# M8416C.net
KiCad netlist of a schematic drawn in EAGLE
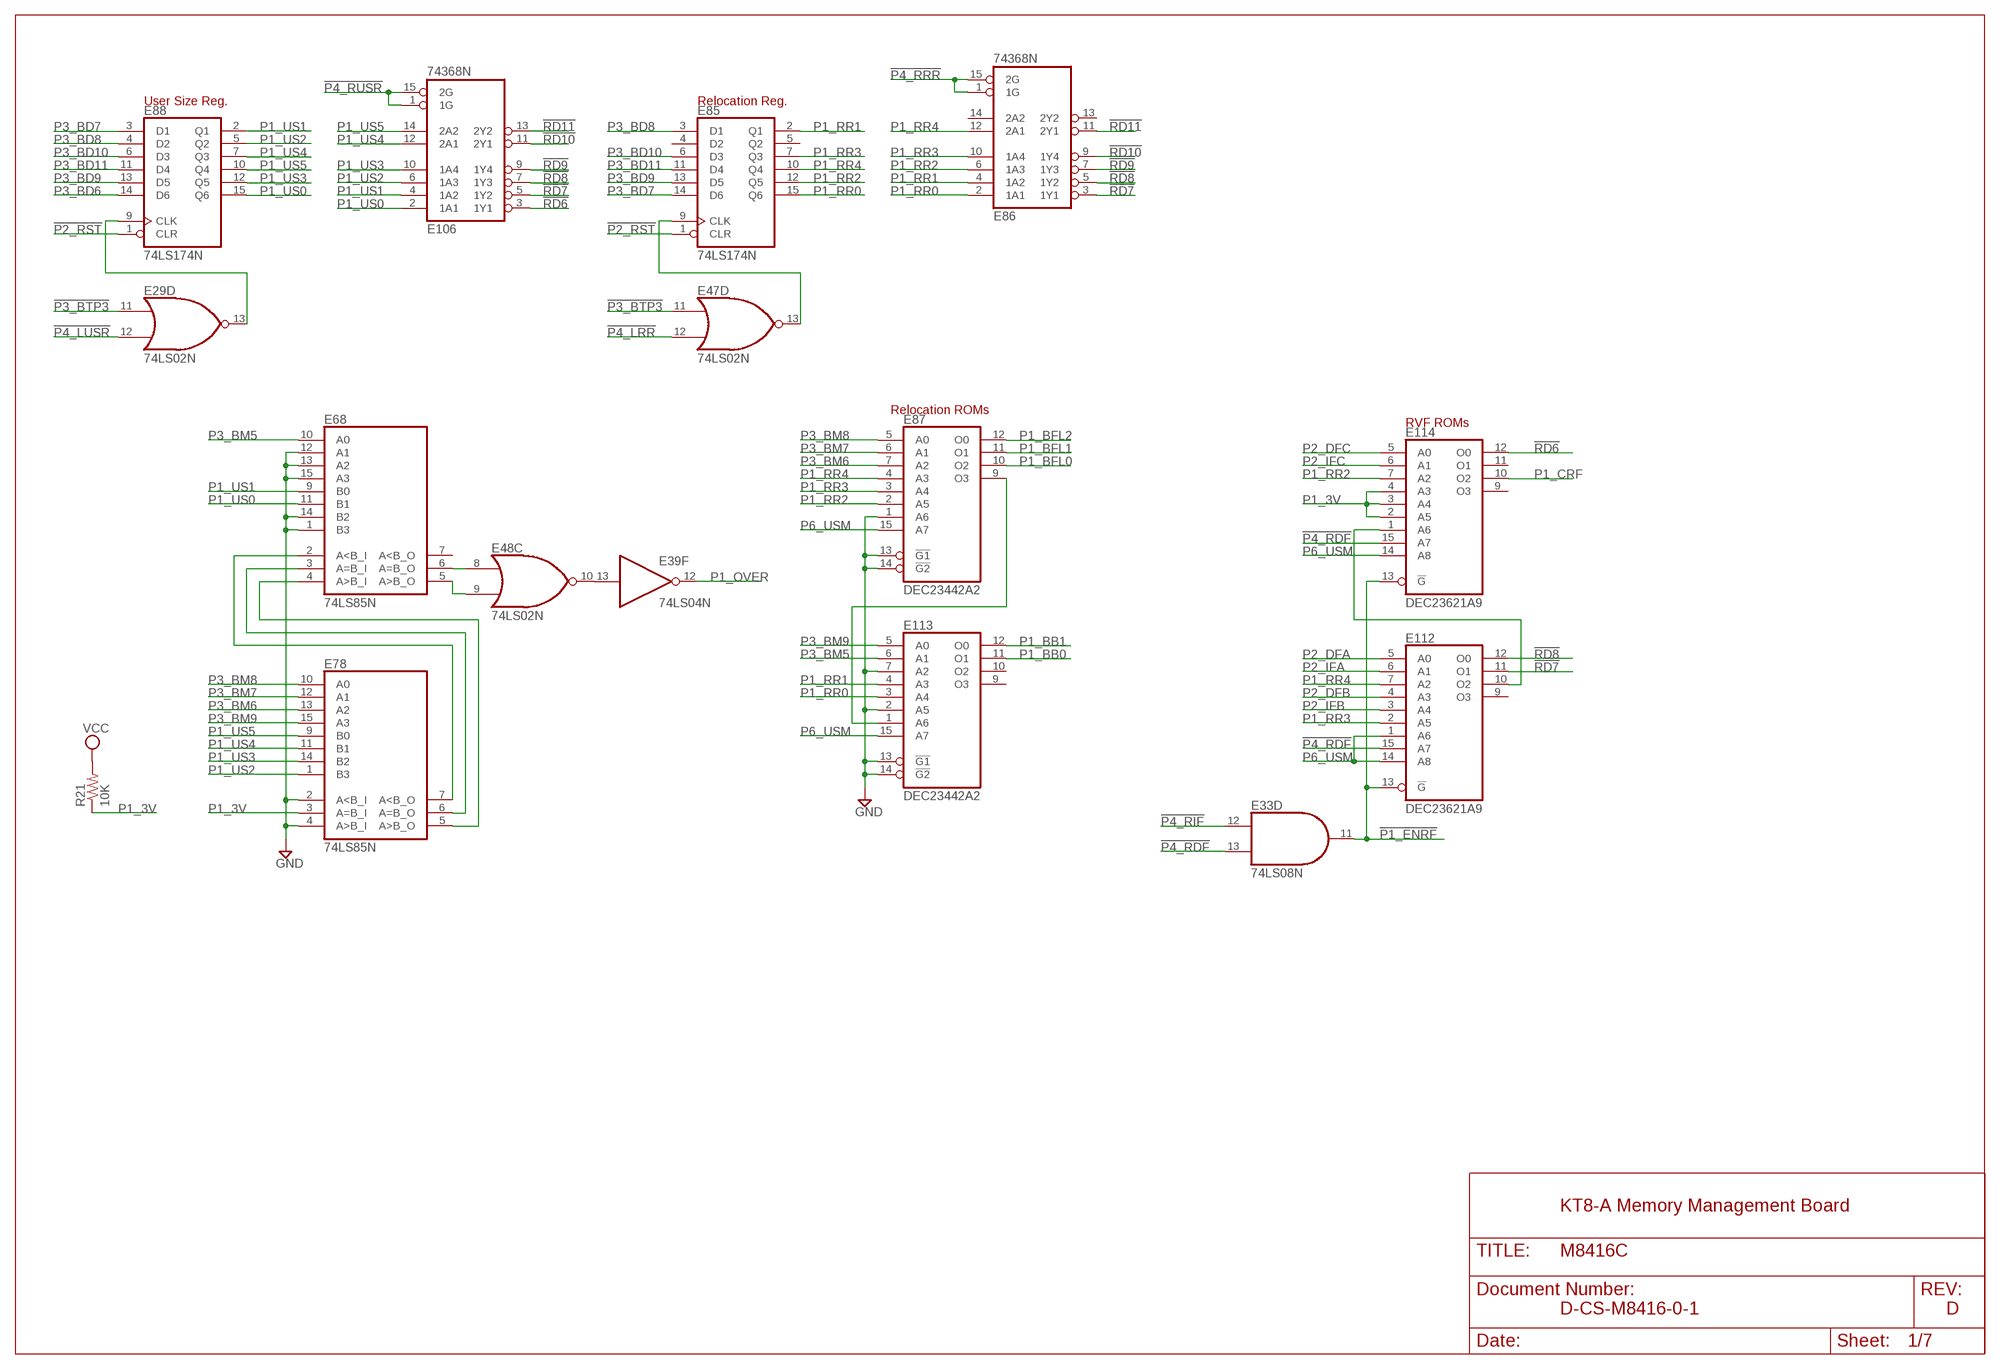
[diagram p0: schematic, sheet 1]
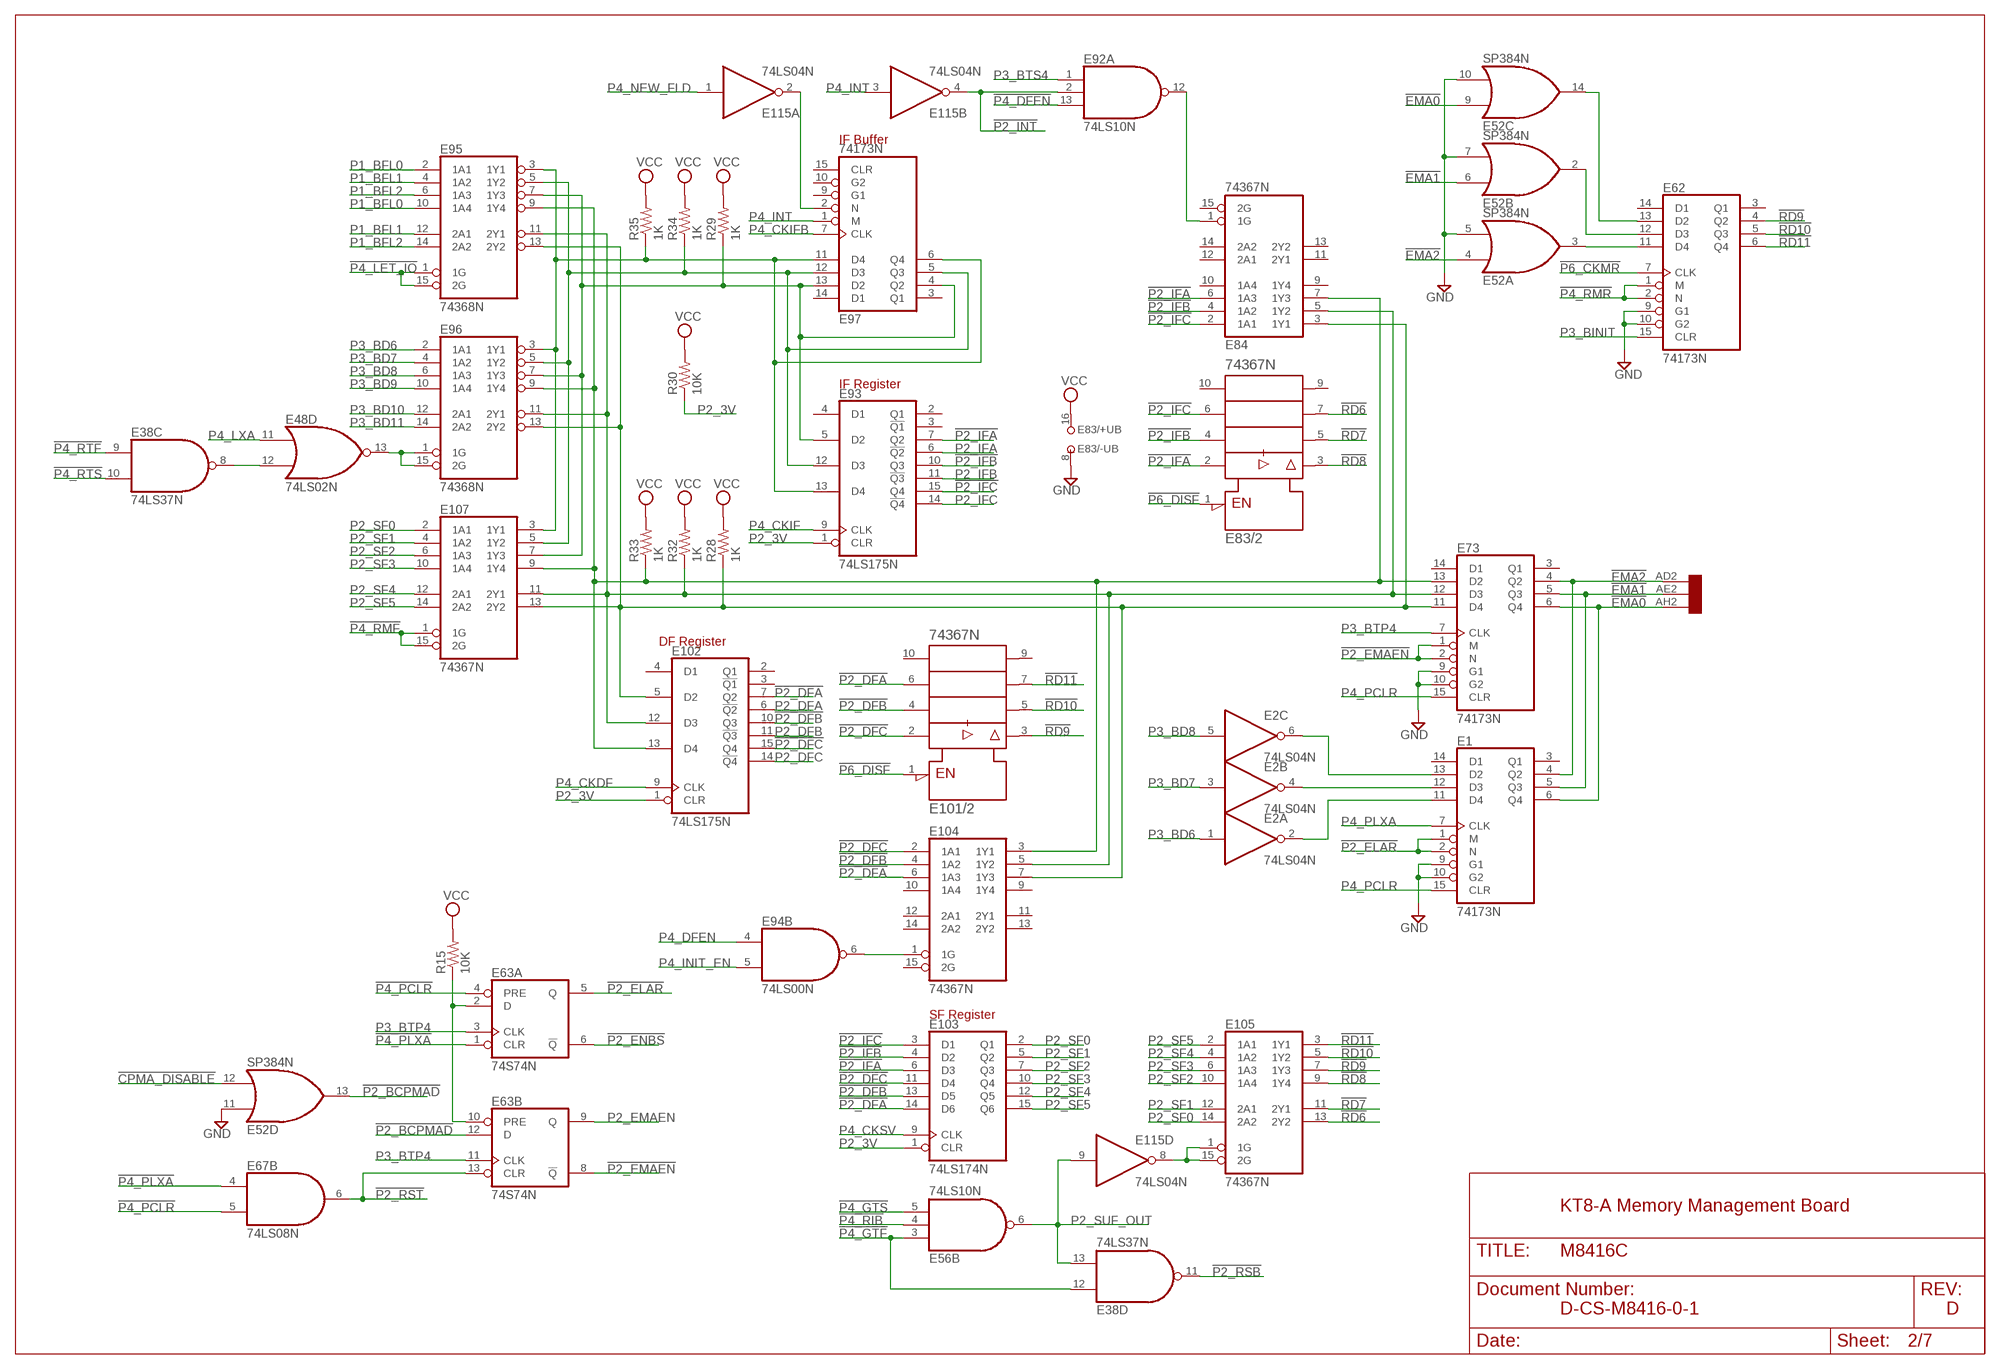
[diagram p1: schematic, sheet 2]
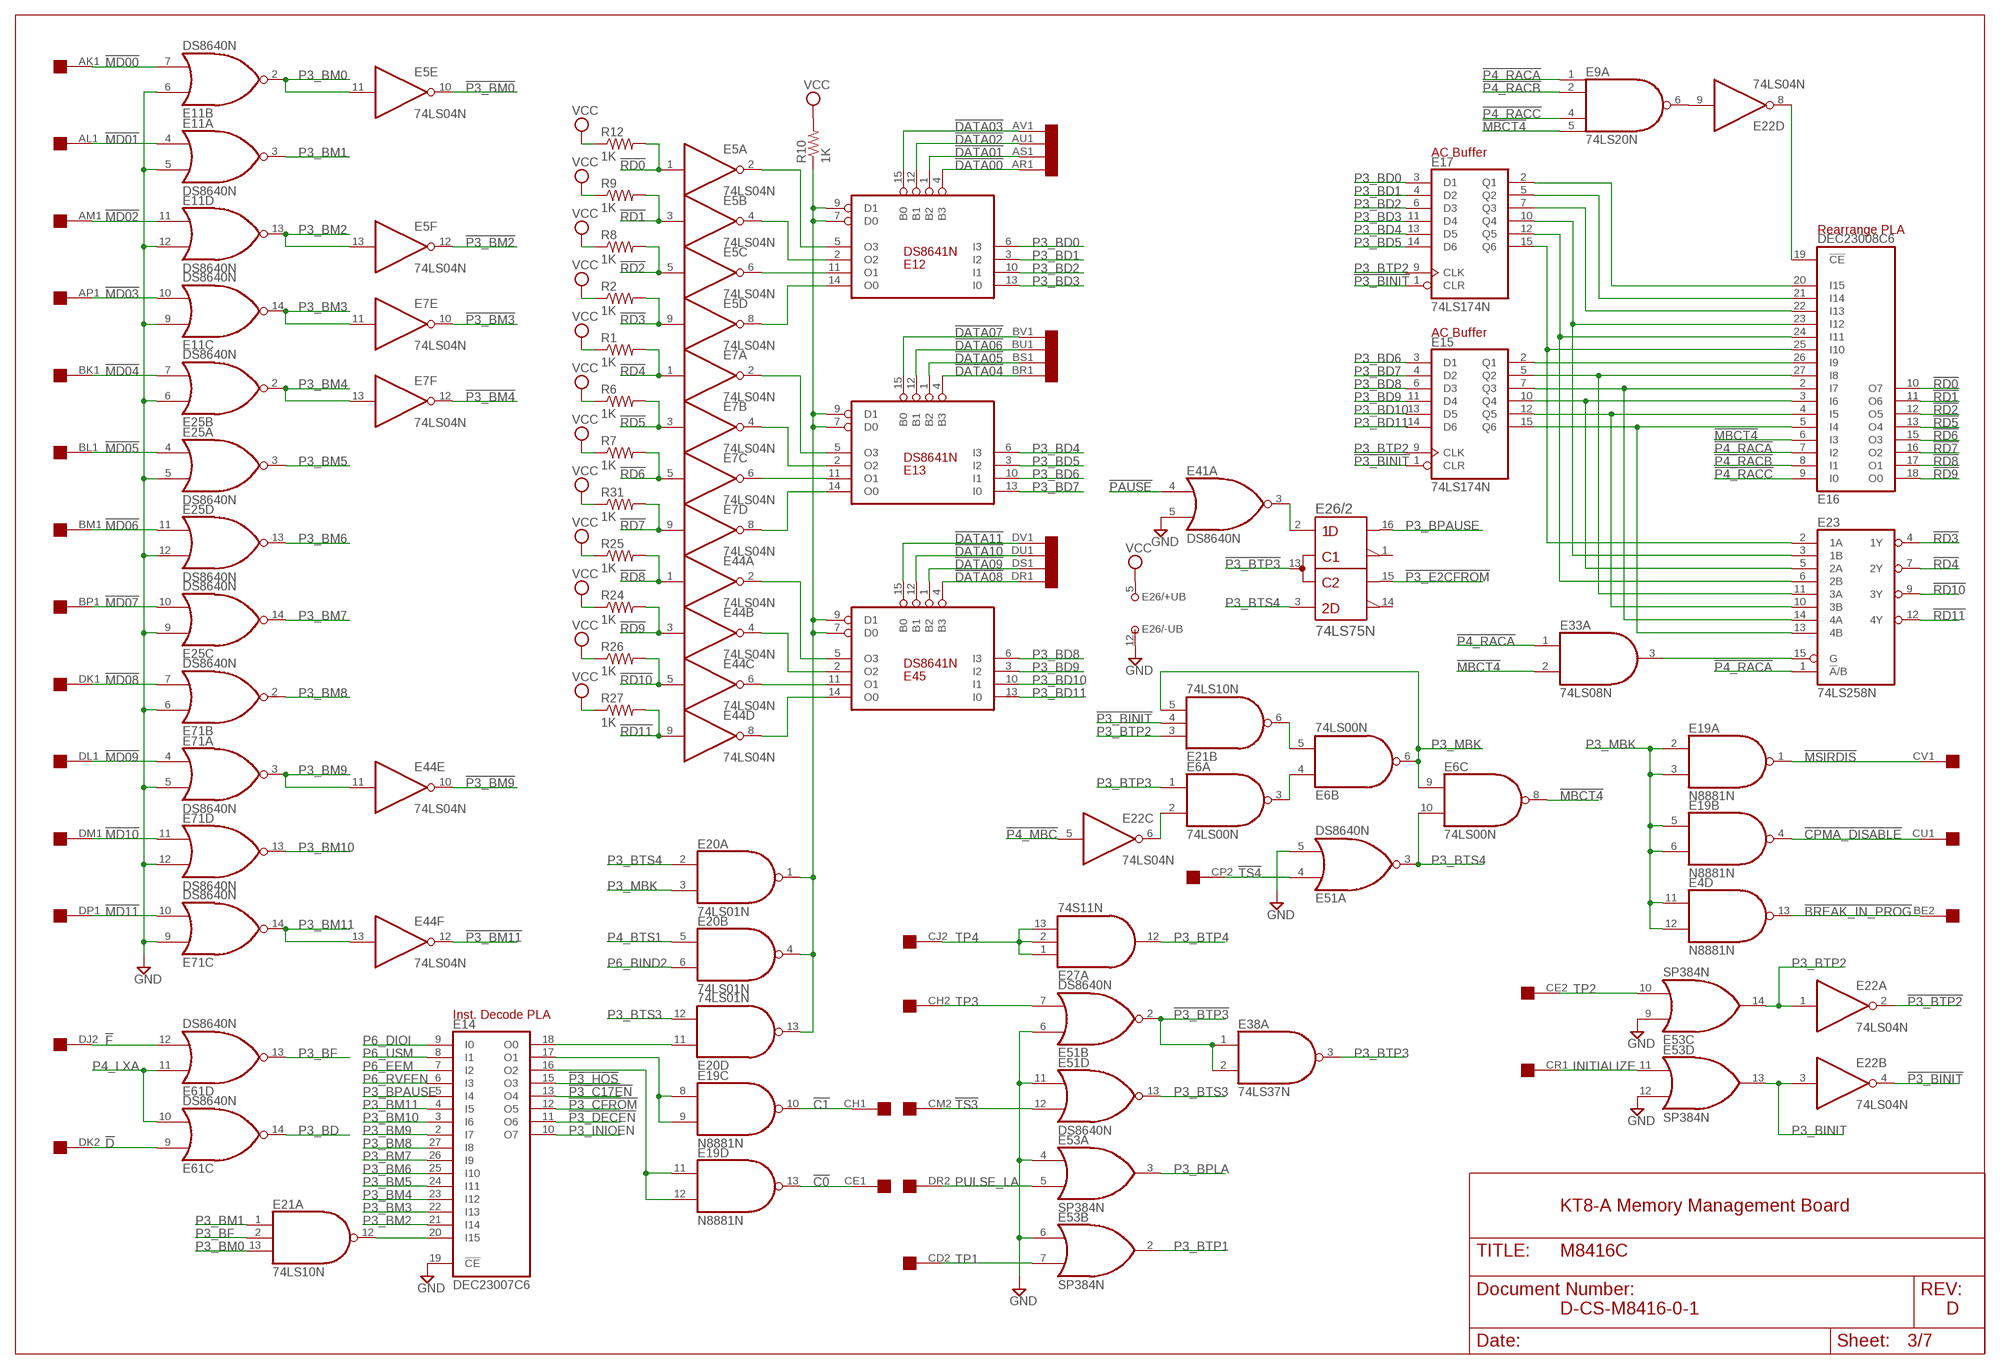
[diagram p2: schematic, sheet 3]
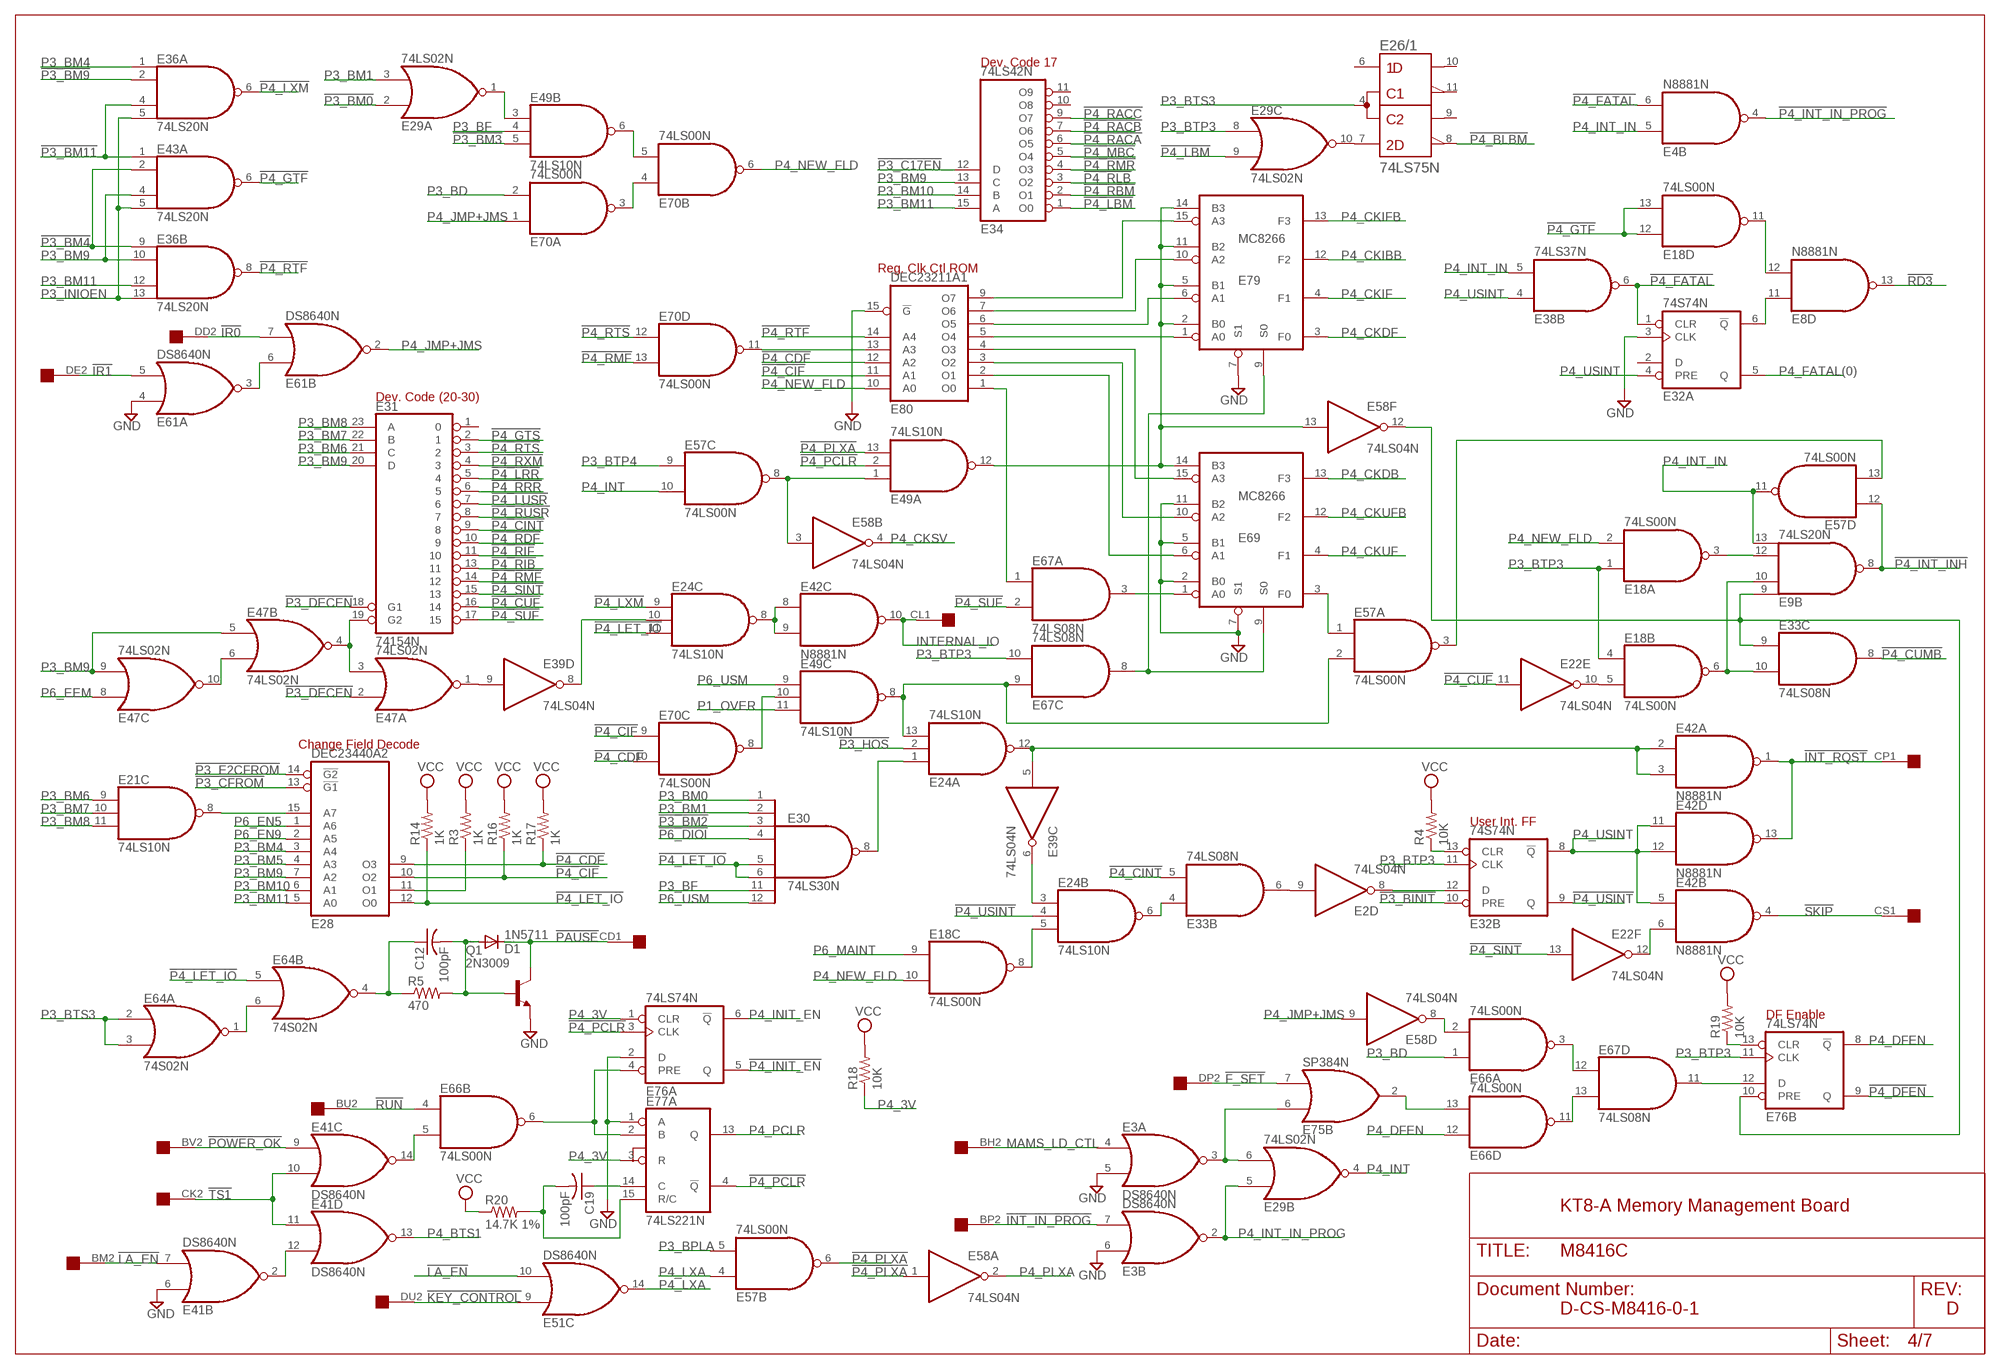
[diagram p3: schematic, sheet 4]
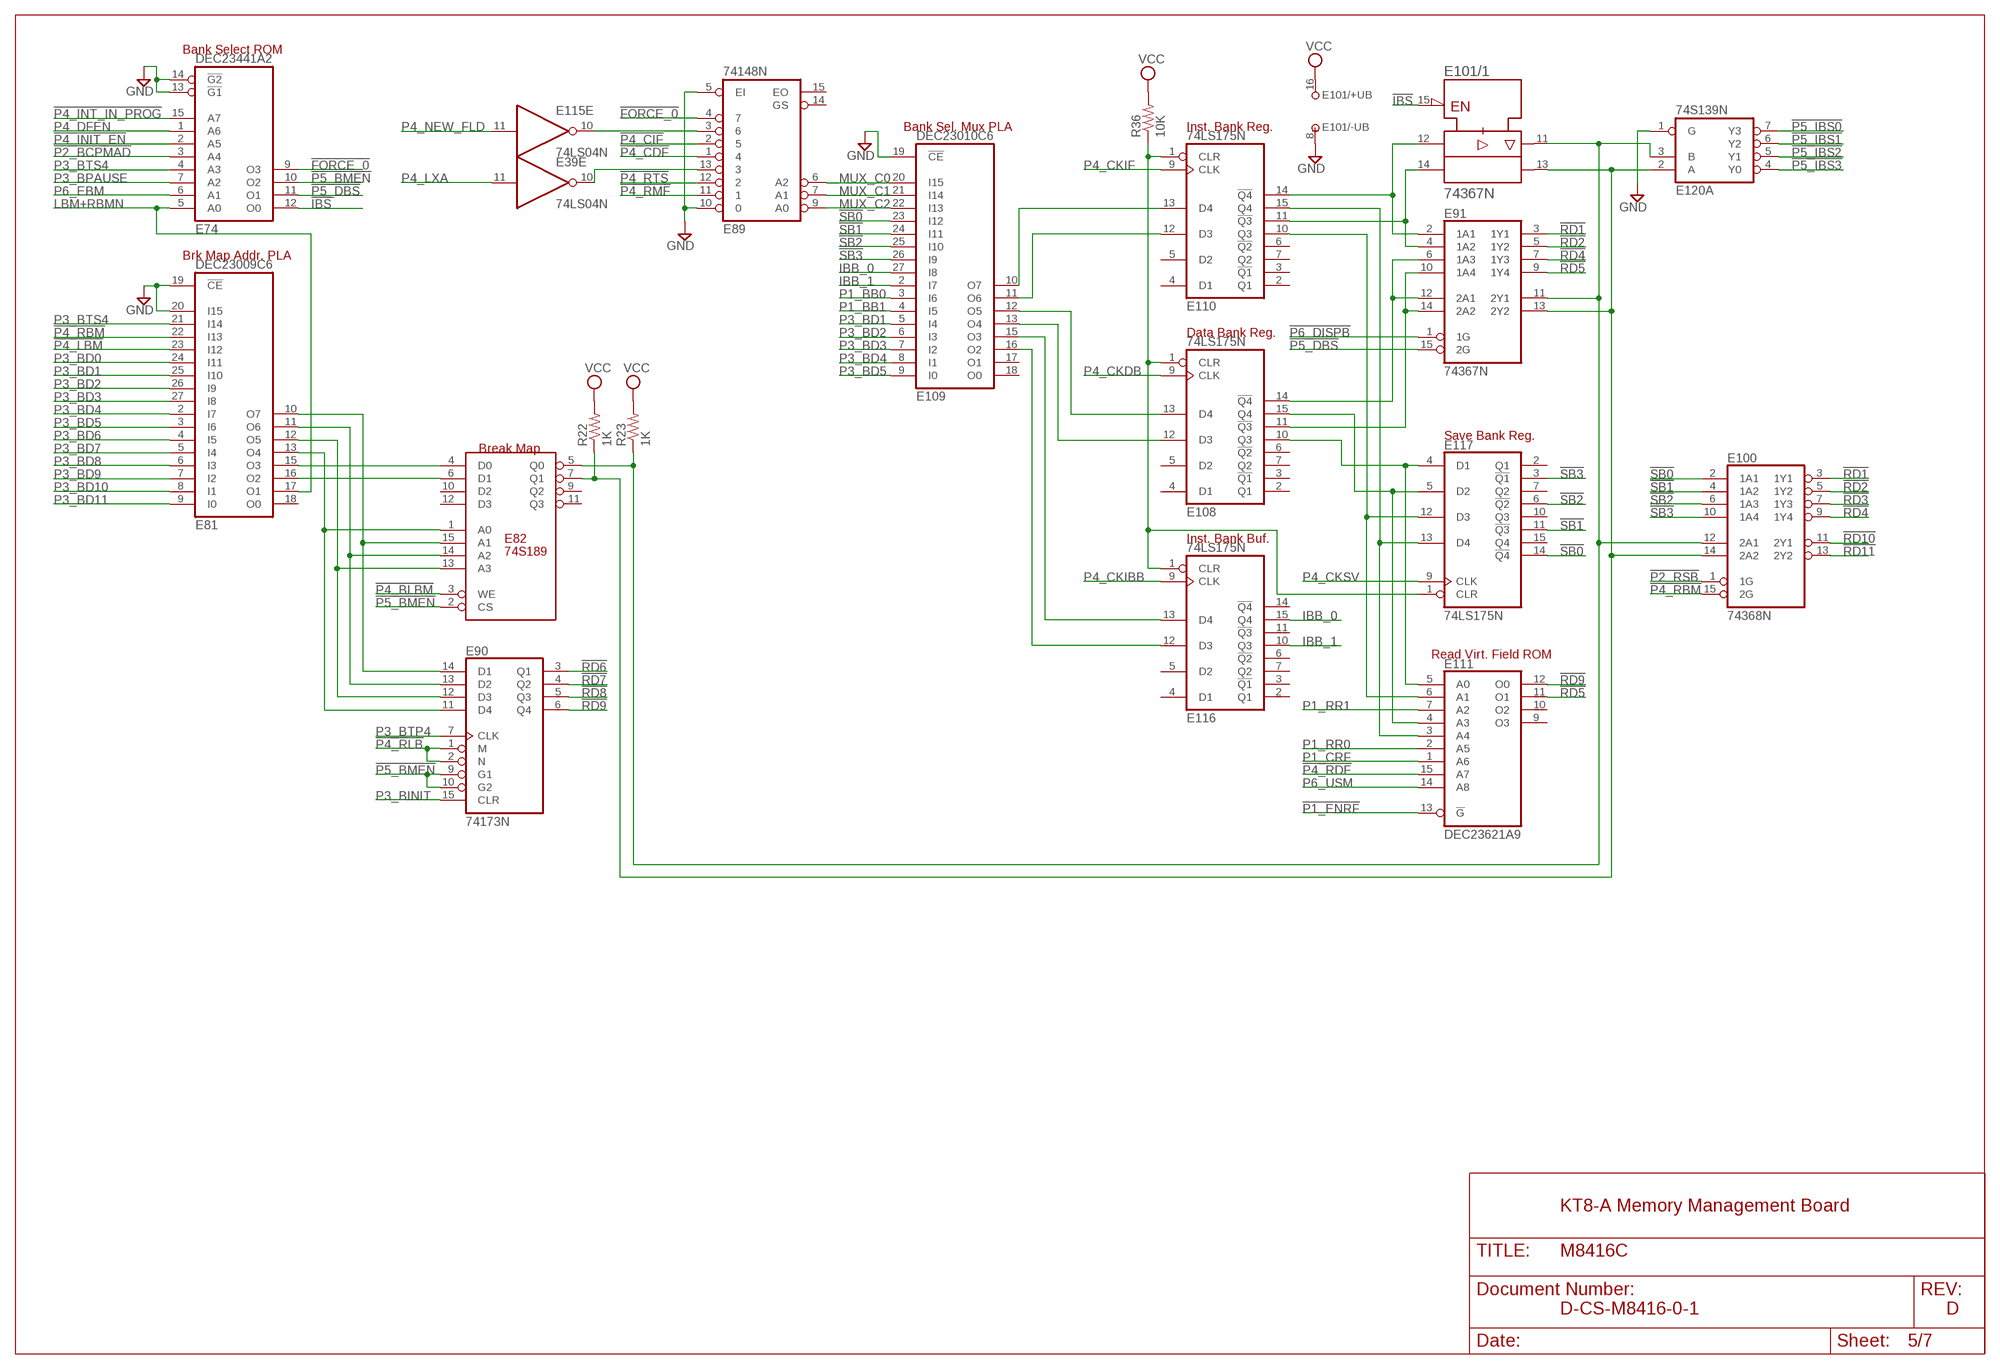
[diagram p4: schematic, sheet 5]
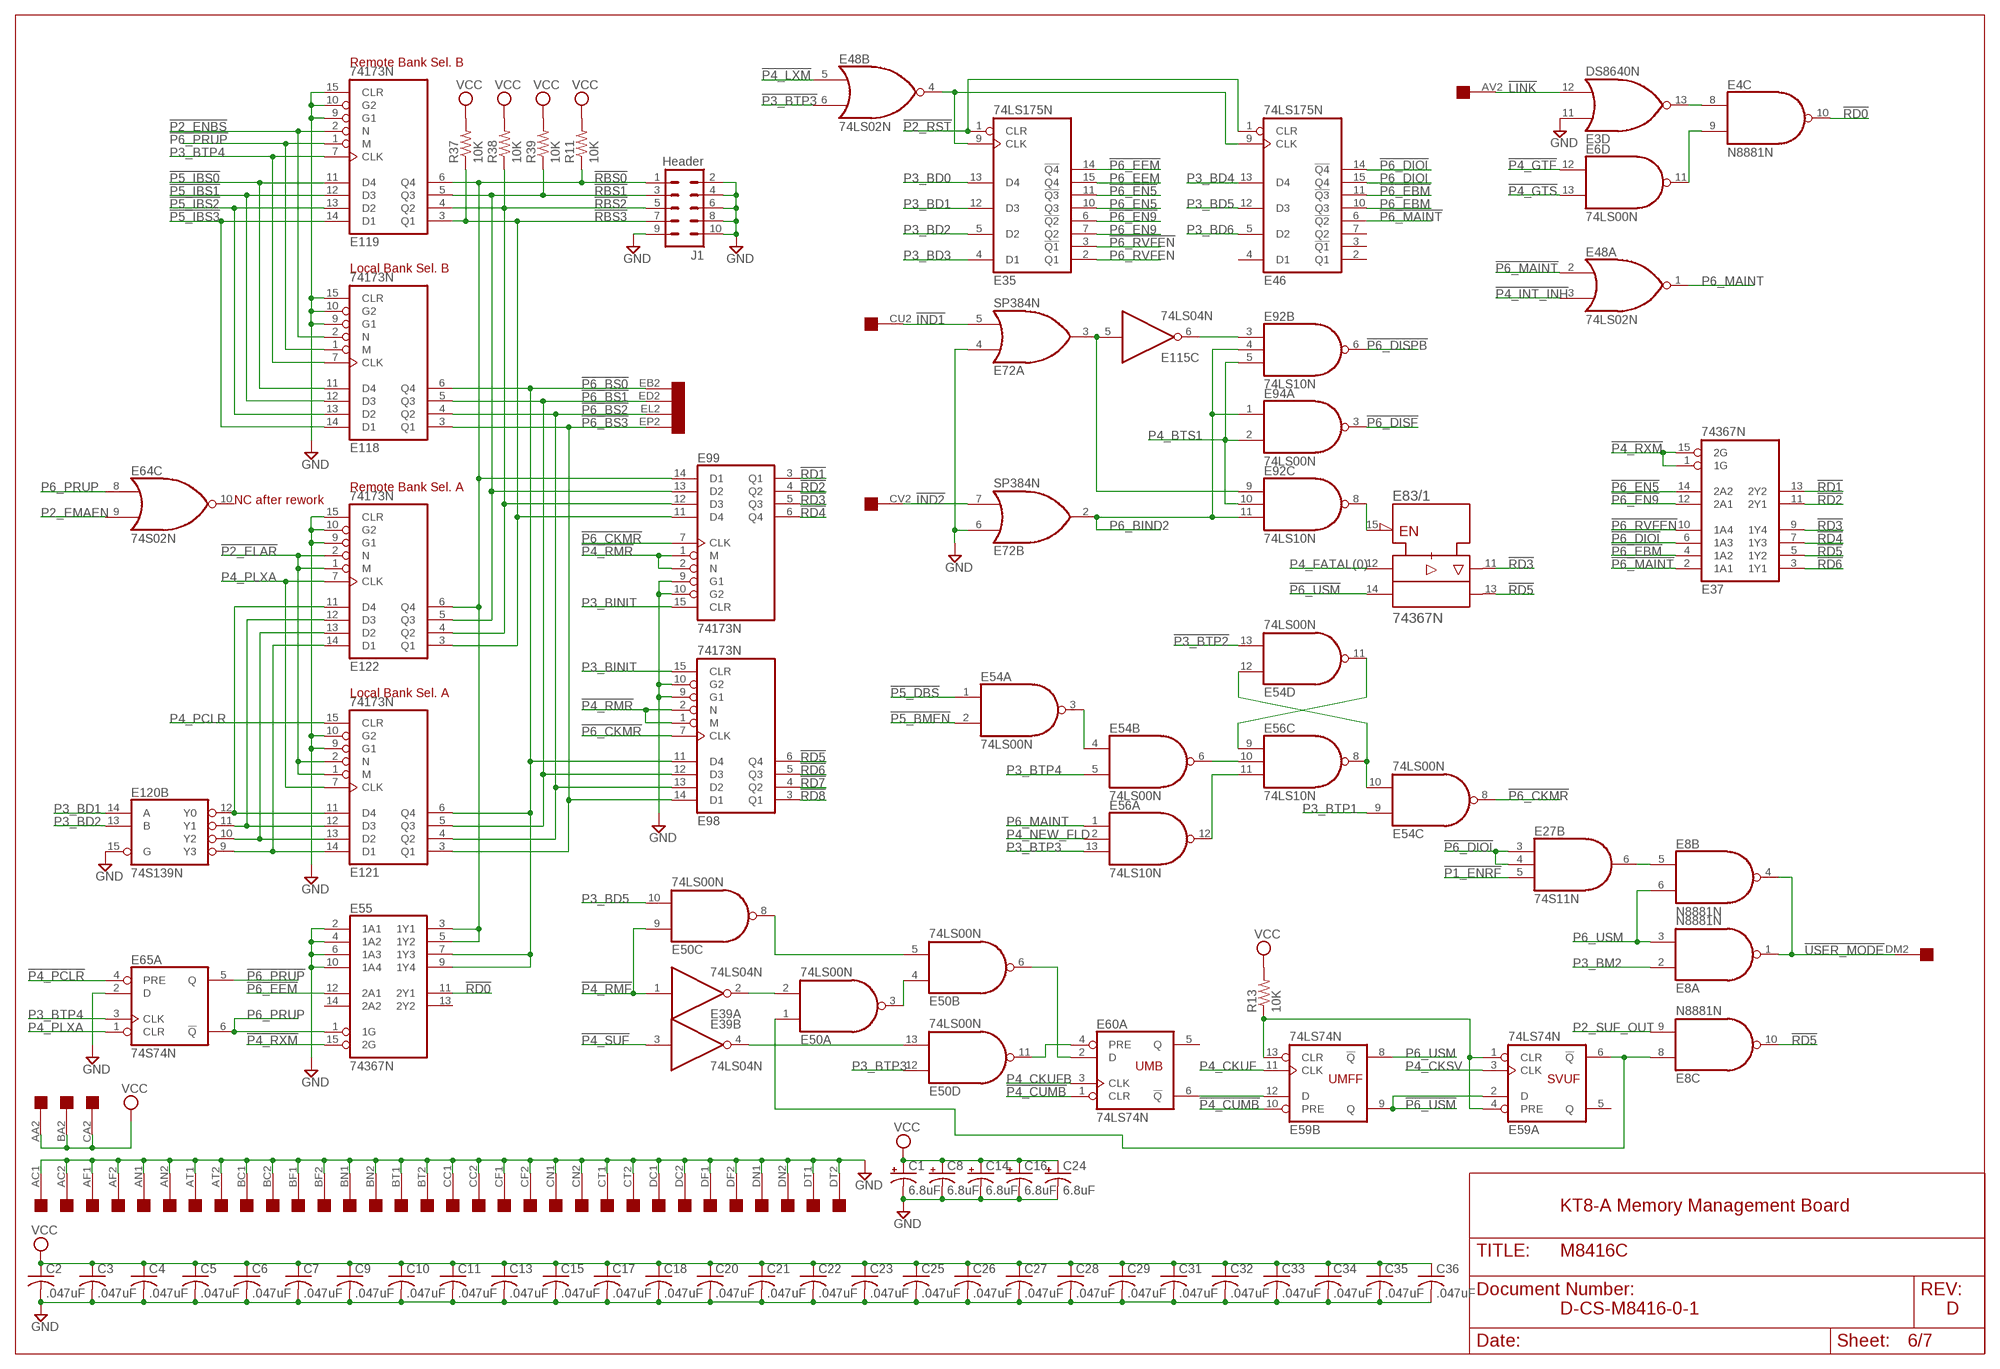
[diagram p5: schematic, sheet 6]
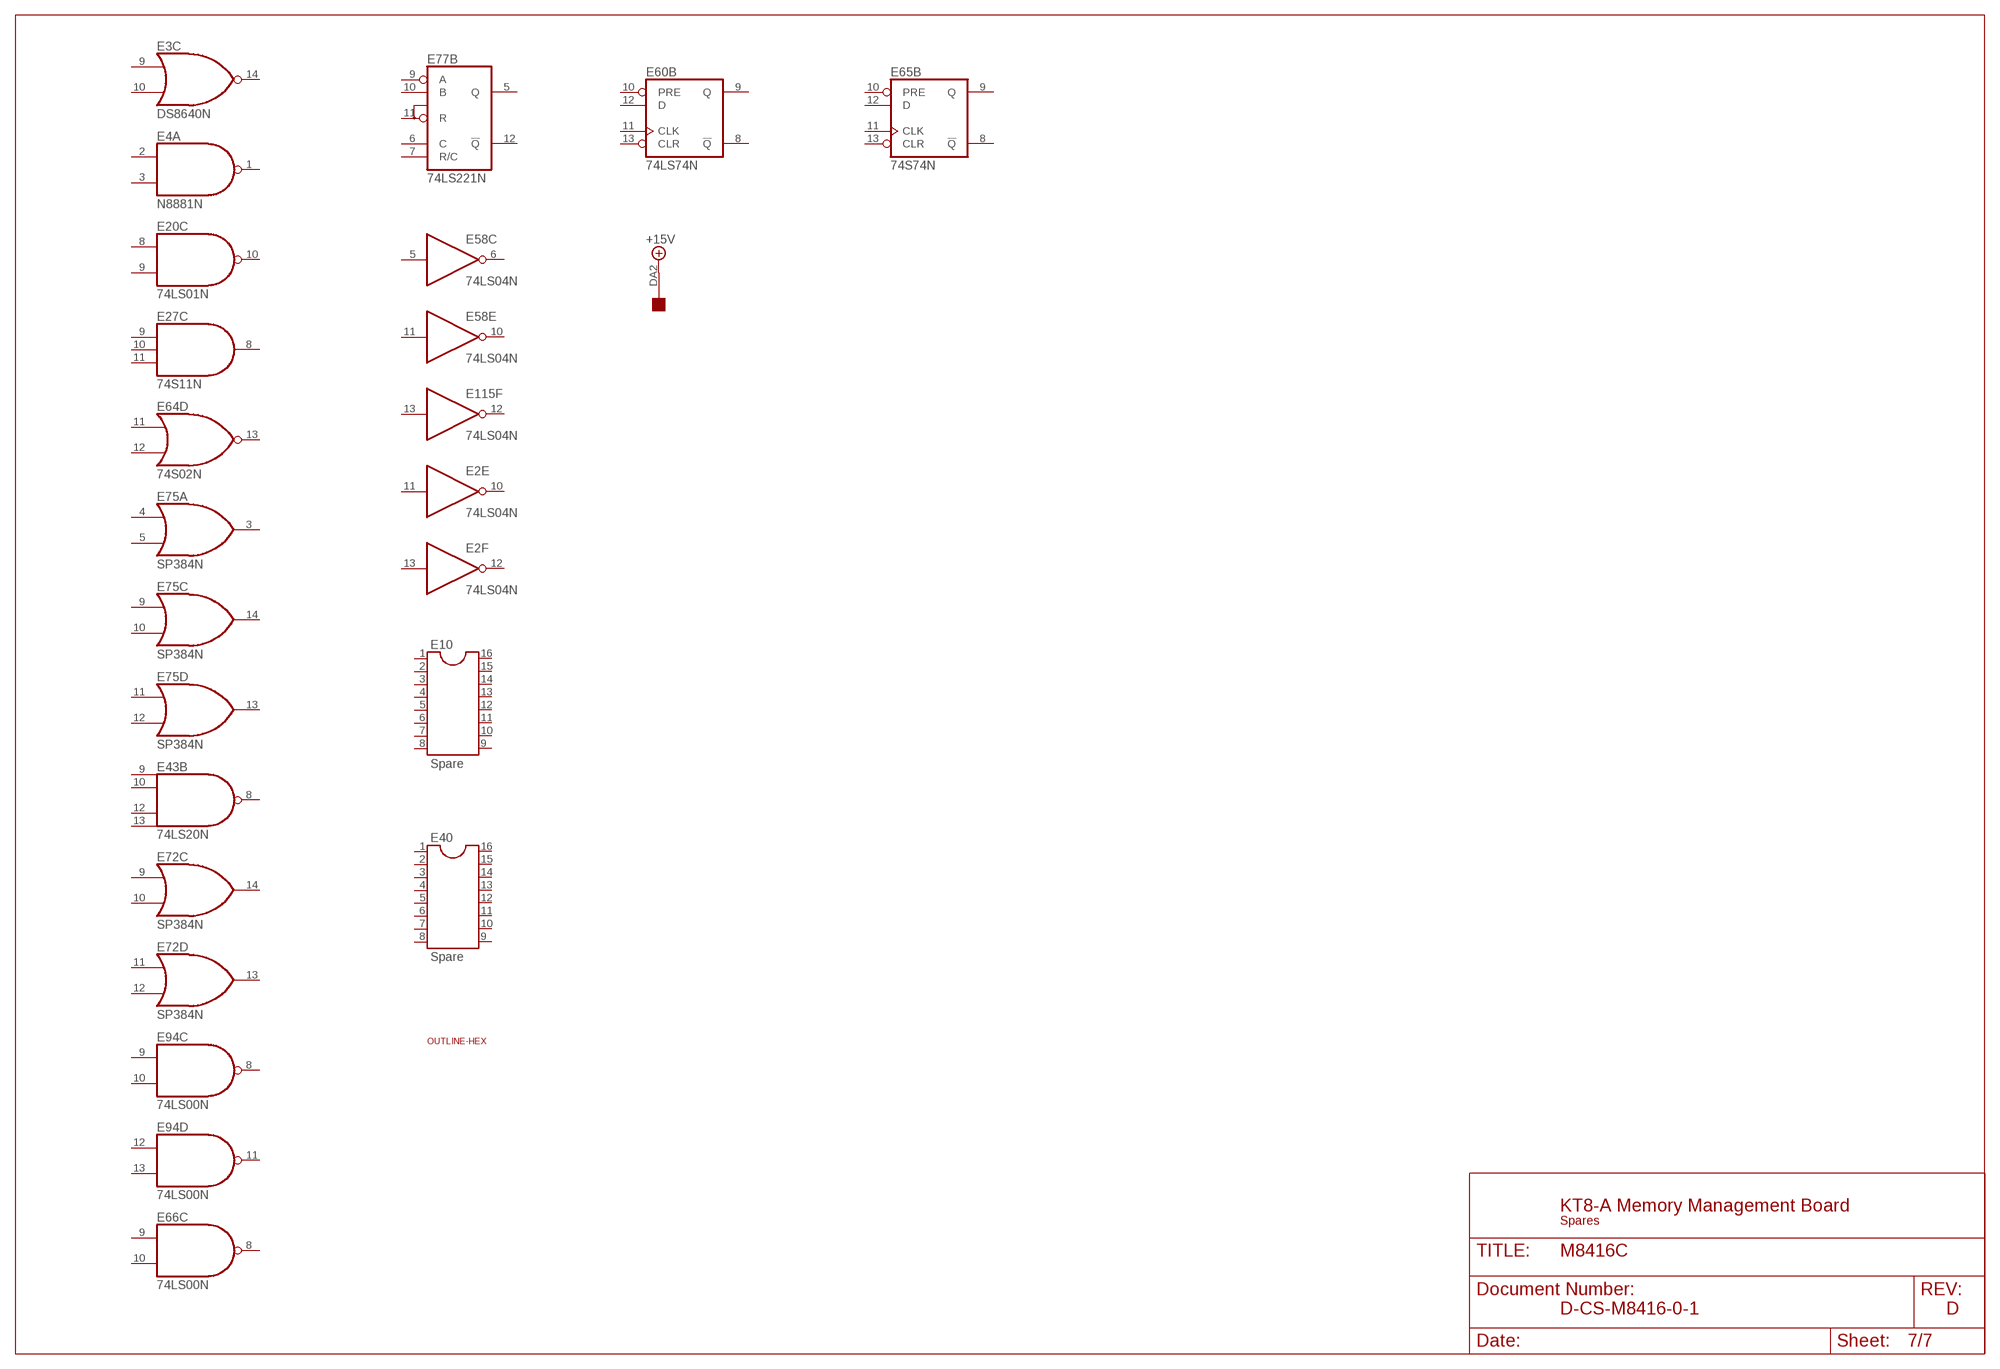
[diagram p6: schematic, sheet 7]

(export (version "E")
  (design (tool "Eeschema 10.0.6"))
  (components
    (comp (ref "E4")
      (value "N8881N")
      (footprint "eagle-import:DIL14")
      (libsource (lib "eagle-import") (part "N8881N"))
    )
    (comp (ref "E5")
      (value "74LS04N")
      (footprint "eagle-import:DIL14")
      (libsource (lib "eagle-import") (part "7404NLS"))
    )
    (comp (ref "E6")
      (value "74LS00N")
      (footprint "eagle-import:DIL14")
      (libsource (lib "eagle-import") (part "7400NLS"))
    )
    (comp (ref "E7")
      (value "74LS04N")
      (footprint "eagle-import:DIL14")
      (libsource (lib "eagle-import") (part "7404NLS"))
    )
    (comp (ref "E9")
      (value "74LS20N")
      (footprint "eagle-import:DIL14")
      (libsource (lib "eagle-import") (part "7420NLS"))
    )
    (comp (ref "E11")
      (value "DS8640N")
      (footprint "eagle-import:DIL14")
      (libsource (lib "eagle-import") (part "DS8640N"))
    )
    (comp (ref "E12")
      (value "DS8641N")
      (footprint "eagle-import:DIL16")
      (libsource (lib "eagle-import") (part "DS8641N"))
    )
    (comp (ref "E13")
      (value "DS8641N")
      (footprint "eagle-import:DIL16")
      (libsource (lib "eagle-import") (part "DS8641N"))
    )
    (comp (ref "E14")
      (value "DEC23007C6")
      (footprint "eagle-import:DIL28")
      (libsource (lib "eagle-import") (part "82S100"))
    )
    (comp (ref "E15")
      (value "74LS174N")
      (footprint "eagle-import:DIL16")
      (libsource (lib "eagle-import") (part "74174NLS"))
    )
    (comp (ref "E16")
      (value "DEC23008C6")
      (footprint "eagle-import:DIL28")
      (libsource (lib "eagle-import") (part "82S100"))
    )
    (comp (ref "E17")
      (value "74LS174N")
      (footprint "eagle-import:DIL16")
      (libsource (lib "eagle-import") (part "74174NLS"))
    )
    (comp (ref "E19")
      (value "N8881N")
      (footprint "eagle-import:DIL14")
      (libsource (lib "eagle-import") (part "N8881N"))
    )
    (comp (ref "E20")
      (value "74LS01N")
      (footprint "eagle-import:DIL14")
      (libsource (lib "eagle-import") (part "7401NLS"))
    )
    (comp (ref "E21")
      (value "74LS10N")
      (footprint "eagle-import:DIL14")
      (libsource (lib "eagle-import") (part "7410NLS"))
    )
    (comp (ref "E22")
      (value "74LS04N")
      (footprint "eagle-import:DIL14")
      (libsource (lib "eagle-import") (part "7404NLS"))
    )
    (comp (ref "E23")
      (value "74LS258N")
      (footprint "eagle-import:DIL16")
      (libsource (lib "eagle-import") (part "74258NLS"))
    )
    (comp (ref "E25")
      (value "DS8640N")
      (footprint "eagle-import:DIL14")
      (libsource (lib "eagle-import") (part "DS8640N"))
    )
    (comp (ref "E26")
      (value "74LS75N")
      (footprint "eagle-import:DIL16")
      (libsource (lib "eagle-import") (part "7475N"))
    )
    (comp (ref "E27")
      (value "74S11N")
      (footprint "eagle-import:DIL14")
      (libsource (lib "eagle-import") (part "7411NS"))
    )
    (comp (ref "E33")
      (value "74LS08N")
      (footprint "eagle-import:DIL14")
      (libsource (lib "eagle-import") (part "7408NLS"))
    )
    (comp (ref "E38")
      (value "74LS37N")
      (footprint "eagle-import:DIL14")
      (libsource (lib "eagle-import") (part "7437NLS"))
    )
    (comp (ref "E41")
      (value "DS8640N")
      (footprint "eagle-import:DIL14")
      (libsource (lib "eagle-import") (part "DS8640N"))
    )
    (comp (ref "E44")
      (value "74LS04N")
      (footprint "eagle-import:DIL14")
      (libsource (lib "eagle-import") (part "7404NLS"))
    )
    (comp (ref "E45")
      (value "DS8641N")
      (footprint "eagle-import:DIL16")
      (libsource (lib "eagle-import") (part "DS8641N"))
    )
    (comp (ref "E51")
      (value "DS8640N")
      (footprint "eagle-import:DIL14")
      (libsource (lib "eagle-import") (part "DS8640N"))
    )
    (comp (ref "E53")
      (value "SP384N")
      (footprint "eagle-import:DIL14")
      (libsource (lib "eagle-import") (part "SP384N"))
    )
    (comp (ref "E61")
      (value "DS8640N")
      (footprint "eagle-import:DIL14")
      (libsource (lib "eagle-import") (part "DS8640N"))
    )
    (comp (ref "E71")
      (value "DS8640N")
      (footprint "eagle-import:DIL14")
      (libsource (lib "eagle-import") (part "DS8640N"))
    )
    (comp (ref "R1")
      (value "1K")
      (footprint "eagle-import:0207_10")
      (libsource (lib "eagle-import") (part "R-US_0207/10"))
    )
    (comp (ref "R2")
      (value "1K")
      (footprint "eagle-import:0207_10")
      (libsource (lib "eagle-import") (part "R-US_0207/10"))
    )
    (comp (ref "R6")
      (value "1K")
      (footprint "eagle-import:0207_10")
      (libsource (lib "eagle-import") (part "R-US_0207/10"))
    )
    (comp (ref "R7")
      (value "1K")
      (footprint "eagle-import:0207_10")
      (libsource (lib "eagle-import") (part "R-US_0207/10"))
    )
    (comp (ref "R8")
      (value "1K")
      (footprint "eagle-import:0207_10")
      (libsource (lib "eagle-import") (part "R-US_0207/10"))
    )
    (comp (ref "R9")
      (value "1K")
      (footprint "eagle-import:0207_10")
      (libsource (lib "eagle-import") (part "R-US_0207/10"))
    )
    (comp (ref "R10")
      (value "1K")
      (footprint "eagle-import:0207_10")
      (libsource (lib "eagle-import") (part "R-US_0207/10"))
    )
    (comp (ref "R12")
      (value "1K")
      (footprint "eagle-import:0207_10")
      (libsource (lib "eagle-import") (part "R-US_0207/10"))
    )
    (comp (ref "R24")
      (value "1K")
      (footprint "eagle-import:0207_10")
      (libsource (lib "eagle-import") (part "R-US_0207/10"))
    )
    (comp (ref "R25")
      (value "1K")
      (footprint "eagle-import:0207_10")
      (libsource (lib "eagle-import") (part "R-US_0207/10"))
    )
    (comp (ref "R26")
      (value "1K")
      (footprint "eagle-import:0207_10")
      (libsource (lib "eagle-import") (part "R-US_0207/10"))
    )
    (comp (ref "R27")
      (value "1K")
      (footprint "eagle-import:0207_10")
      (libsource (lib "eagle-import") (part "R-US_0207/10"))
    )
    (comp (ref "R31")
      (value "1K")
      (footprint "eagle-import:0207_10")
      (libsource (lib "eagle-import") (part "R-US_0207/10"))
    )
    (comp (ref "U$1")
      (value "HEX")
      (footprint "eagle-import:EDGE-CON12")
      (libsource (lib "eagle-import") (part "HEX"))
    )
    (comp (ref "E29")
      (value "74LS02N")
      (footprint "eagle-import:DIL14")
      (libsource (lib "eagle-import") (part "7402NLS"))
    )
    (comp (ref "E39")
      (value "74LS04N")
      (footprint "eagle-import:DIL14")
      (libsource (lib "eagle-import") (part "7404NLS"))
    )
    (comp (ref "E47")
      (value "74LS02N")
      (footprint "eagle-import:DIL14")
      (libsource (lib "eagle-import") (part "7402NLS"))
    )
    (comp (ref "E48")
      (value "74LS02N")
      (footprint "eagle-import:DIL14")
      (libsource (lib "eagle-import") (part "7402NLS"))
    )
    (comp (ref "E68")
      (value "74LS85N")
      (footprint "eagle-import:DIL16")
      (libsource (lib "eagle-import") (part "7485NLS"))
    )
    (comp (ref "E78")
      (value "74LS85N")
      (footprint "eagle-import:DIL16")
      (libsource (lib "eagle-import") (part "7485NLS"))
    )
    (comp (ref "E85")
      (value "74LS174N")
      (footprint "eagle-import:DIL16")
      (libsource (lib "eagle-import") (part "74174NLS"))
    )
    (comp (ref "E86")
      (value "74368N")
      (footprint "eagle-import:DIL16")
      (libsource (lib "eagle-import") (part "74368N"))
    )
    (comp (ref "E87")
      (value "DEC23442A2")
      (footprint "eagle-import:DIL16")
      (libsource (lib "eagle-import") (part "74S287"))
    )
    (comp (ref "E88")
      (value "74LS174N")
      (footprint "eagle-import:DIL16")
      (libsource (lib "eagle-import") (part "74174NLS"))
    )
    (comp (ref "E106")
      (value "74368N")
      (footprint "eagle-import:DIL16")
      (libsource (lib "eagle-import") (part "74368N"))
    )
    (comp (ref "E112")
      (value "DEC23621A9")
      (footprint "eagle-import:DIL16")
      (libsource (lib "eagle-import") (part "74S571"))
    )
    (comp (ref "E113")
      (value "DEC23442A2")
      (footprint "eagle-import:DIL16")
      (libsource (lib "eagle-import") (part "74S287"))
    )
    (comp (ref "E114")
      (value "DEC23621A9")
      (footprint "eagle-import:DIL16")
      (libsource (lib "eagle-import") (part "74S571"))
    )
    (comp (ref "R21")
      (value "10K")
      (footprint "eagle-import:0207_10")
      (libsource (lib "eagle-import") (part "R-US_0207/10"))
    )
    (comp (ref "E74")
      (value "DEC23441A2")
      (footprint "eagle-import:DIL16")
      (libsource (lib "eagle-import") (part "74S287"))
    )
    (comp (ref "E81")
      (value "DEC23009C6")
      (footprint "eagle-import:DIL28")
      (libsource (lib "eagle-import") (part "82S100"))
    )
    (comp (ref "E82")
      (value "74S189")
      (footprint "eagle-import:DIL16")
      (libsource (lib "eagle-import") (part "7489"))
    )
    (comp (ref "E89")
      (value "74148N")
      (footprint "eagle-import:DIL16")
      (libsource (lib "eagle-import") (part "74148N"))
    )
    (comp (ref "E90")
      (value "74173N")
      (footprint "eagle-import:DIL16")
      (libsource (lib "eagle-import") (part "74173NLS"))
    )
    (comp (ref "E91")
      (value "74367N")
      (footprint "eagle-import:DIL16")
      (libsource (lib "eagle-import") (part "74xx-us_74367N"))
    )
    (comp (ref "E100")
      (value "74368N")
      (footprint "eagle-import:DIL16")
      (libsource (lib "eagle-import") (part "74368N"))
    )
    (comp (ref "E101")
      (value "74367N")
      (footprint "eagle-import:DIL16")
      (libsource (lib "eagle-import") (part "74367N"))
    )
    (comp (ref "E108")
      (value "74LS175N")
      (footprint "eagle-import:DIL16")
      (libsource (lib "eagle-import") (part "74175NLS"))
    )
    (comp (ref "E109")
      (value "DEC23010C6")
      (footprint "eagle-import:DIL28")
      (libsource (lib "eagle-import") (part "82S100"))
    )
    (comp (ref "E110")
      (value "74LS175N")
      (footprint "eagle-import:DIL16")
      (libsource (lib "eagle-import") (part "74175NLS"))
    )
    (comp (ref "E111")
      (value "DEC23621A9")
      (footprint "eagle-import:DIL16")
      (libsource (lib "eagle-import") (part "74S571"))
    )
    (comp (ref "E115")
      (value "74LS04N")
      (footprint "eagle-import:DIL14")
      (libsource (lib "eagle-import") (part "7404NLS"))
    )
    (comp (ref "E116")
      (value "74LS175N")
      (footprint "eagle-import:DIL16")
      (libsource (lib "eagle-import") (part "74175NLS"))
    )
    (comp (ref "E117")
      (value "74LS175N")
      (footprint "eagle-import:DIL16")
      (libsource (lib "eagle-import") (part "74175NLS"))
    )
    (comp (ref "E120")
      (value "74S139N")
      (footprint "eagle-import:DIL16")
      (libsource (lib "eagle-import") (part "74139NS"))
    )
    (comp (ref "R22")
      (value "1K")
      (footprint "eagle-import:0207_10")
      (libsource (lib "eagle-import") (part "R-US_0207/10"))
    )
    (comp (ref "R23")
      (value "1K")
      (footprint "eagle-import:0207_10")
      (libsource (lib "eagle-import") (part "R-US_0207/10"))
    )
    (comp (ref "R36")
      (value "10K")
      (footprint "eagle-import:0207_10")
      (libsource (lib "eagle-import") (part "R-US_0207/10"))
    )
    (comp (ref "E2")
      (value "74LS04N")
      (footprint "eagle-import:DIL14")
      (libsource (lib "eagle-import") (part "7404NLS"))
    )
    (comp (ref "E3")
      (value "DS8640N")
      (footprint "eagle-import:DIL14")
      (libsource (lib "eagle-import") (part "DS8640N"))
    )
    (comp (ref "E10")
      (value "Spare")
      (footprint "eagle-import:SOCKET-16")
      (libsource (lib "eagle-import") (part "DIL16S"))
    )
    (comp (ref "E40")
      (value "Spare")
      (footprint "eagle-import:SOCKET-16")
      (libsource (lib "eagle-import") (part "DIL16S"))
    )
    (comp (ref "E43")
      (value "74LS20N")
      (footprint "eagle-import:DIL14")
      (libsource (lib "eagle-import") (part "7420NLS"))
    )
    (comp (ref "E58")
      (value "74LS04N")
      (footprint "eagle-import:DIL14")
      (libsource (lib "eagle-import") (part "7404NLS"))
    )
    (comp (ref "E60")
      (value "74LS74N")
      (footprint "eagle-import:DIL14")
      (libsource (lib "eagle-import") (part "7474NLS"))
    )
    (comp (ref "E64")
      (value "74S02N")
      (footprint "eagle-import:DIL14")
      (libsource (lib "eagle-import") (part "7402NS"))
    )
    (comp (ref "E65")
      (value "74S74N")
      (footprint "eagle-import:DIL14")
      (libsource (lib "eagle-import") (part "7474NS"))
    )
    (comp (ref "E66")
      (value "74LS00N")
      (footprint "eagle-import:DIL14")
      (libsource (lib "eagle-import") (part "7400NLS"))
    )
    (comp (ref "E72")
      (value "SP384N")
      (footprint "eagle-import:DIL14")
      (libsource (lib "eagle-import") (part "SP384N"))
    )
    (comp (ref "E75")
      (value "SP384N")
      (footprint "eagle-import:DIL14")
      (libsource (lib "eagle-import") (part "SP384N"))
    )
    (comp (ref "E77")
      (value "74LS221N")
      (footprint "eagle-import:DIL16")
      (libsource (lib "eagle-import") (part "74221NLS"))
    )
    (comp (ref "E94")
      (value "74LS00N")
      (footprint "eagle-import:DIL14")
      (libsource (lib "eagle-import") (part "7400NLS"))
    )
    (comp (ref "U$2")
      (value "OUTLINE-HEX")
      (footprint "eagle-import:HEX-HEIGHT")
      (libsource (lib "eagle-import") (part "OUTLINE-HEX"))
    )
    (comp (ref "C1")
      (value "6.8uF")
      (footprint "eagle-import:E12-8")
      (libsource (lib "eagle-import") (part "CPOL-USE20-8AXIAL"))
    )
    (comp (ref "C2")
      (value ".047uF")
      (footprint "eagle-import:C102-043X133")
      (libsource (lib "eagle-import") (part "C-US102-043X133"))
    )
    (comp (ref "C3")
      (value ".047uF")
      (footprint "eagle-import:C102-043X133")
      (libsource (lib "eagle-import") (part "C-US102-043X133"))
    )
    (comp (ref "C4")
      (value ".047uF")
      (footprint "eagle-import:C102-043X133")
      (libsource (lib "eagle-import") (part "C-US102-043X133"))
    )
    (comp (ref "C5")
      (value ".047uF")
      (footprint "eagle-import:C102-043X133")
      (libsource (lib "eagle-import") (part "C-US102-043X133"))
    )
    (comp (ref "C6")
      (value ".047uF")
      (footprint "eagle-import:C102-043X133")
      (libsource (lib "eagle-import") (part "C-US102-043X133"))
    )
    (comp (ref "C7")
      (value ".047uF")
      (footprint "eagle-import:C102-043X133")
      (libsource (lib "eagle-import") (part "C-US102-043X133"))
    )
    (comp (ref "C8")
      (value "6.8uF")
      (footprint "eagle-import:E12-8")
      (libsource (lib "eagle-import") (part "CPOL-USE20-8AXIAL"))
    )
    (comp (ref "C9")
      (value ".047uF")
      (footprint "eagle-import:C102-043X133")
      (libsource (lib "eagle-import") (part "C-US102-043X133"))
    )
    (comp (ref "C10")
      (value ".047uF")
      (footprint "eagle-import:C102-043X133")
      (libsource (lib "eagle-import") (part "C-US102-043X133"))
    )
    (comp (ref "C11")
      (value ".047uF")
      (footprint "eagle-import:C102-043X133")
      (libsource (lib "eagle-import") (part "C-US102-043X133"))
    )
    (comp (ref "C13")
      (value ".047uF")
      (footprint "eagle-import:C102-043X133")
      (libsource (lib "eagle-import") (part "C-US102-043X133"))
    )
    (comp (ref "C14")
      (value "6.8uF")
      (footprint "eagle-import:E12-8")
      (libsource (lib "eagle-import") (part "CPOL-USE20-8AXIAL"))
    )
    (comp (ref "C15")
      (value ".047uF")
      (footprint "eagle-import:C102-043X133")
      (libsource (lib "eagle-import") (part "C-US102-043X133"))
    )
    (comp (ref "C16")
      (value "6.8uF")
      (footprint "eagle-import:E12-8")
      (libsource (lib "eagle-import") (part "CPOL-USE20-8AXIAL"))
    )
    (comp (ref "C17")
      (value ".047uF")
      (footprint "eagle-import:C102-043X133")
      (libsource (lib "eagle-import") (part "C-US102-043X133"))
    )
    (comp (ref "C18")
      (value ".047uF")
      (footprint "eagle-import:C102-043X133")
      (libsource (lib "eagle-import") (part "C-US102-043X133"))
    )
    (comp (ref "C20")
      (value ".047uF")
      (footprint "eagle-import:C102-043X133")
      (libsource (lib "eagle-import") (part "C-US102-043X133"))
    )
    (comp (ref "C21")
      (value ".047uF")
      (footprint "eagle-import:C102-043X133")
      (libsource (lib "eagle-import") (part "C-US102-043X133"))
    )
    (comp (ref "C22")
      (value ".047uF")
      (footprint "eagle-import:C102-043X133")
      (libsource (lib "eagle-import") (part "C-US102-043X133"))
    )
    (comp (ref "C23")
      (value ".047uF")
      (footprint "eagle-import:C102-043X133")
      (libsource (lib "eagle-import") (part "C-US102-043X133"))
    )
    (comp (ref "C24")
      (value "6.8uF")
      (footprint "eagle-import:E12-8")
      (libsource (lib "eagle-import") (part "CPOL-USE20-8AXIAL"))
    )
    (comp (ref "C25")
      (value ".047uF")
      (footprint "eagle-import:C102-043X133")
      (libsource (lib "eagle-import") (part "C-US102-043X133"))
    )
    (comp (ref "C26")
      (value ".047uF")
      (footprint "eagle-import:C102-043X133")
      (libsource (lib "eagle-import") (part "C-US102-043X133"))
    )
    (comp (ref "C27")
      (value ".047uF")
      (footprint "eagle-import:C102-043X133")
      (libsource (lib "eagle-import") (part "C-US102-043X133"))
    )
    (comp (ref "C28")
      (value ".047uF")
      (footprint "eagle-import:C102-043X133")
      (libsource (lib "eagle-import") (part "C-US102-043X133"))
    )
    (comp (ref "C29")
      (value ".047uF")
      (footprint "eagle-import:C102-043X133")
      (libsource (lib "eagle-import") (part "C-US102-043X133"))
    )
    (comp (ref "C31")
      (value ".047uF")
      (footprint "eagle-import:C102-043X133")
      (libsource (lib "eagle-import") (part "C-US102-043X133"))
    )
    (comp (ref "C32")
      (value ".047uF")
      (footprint "eagle-import:C102-043X133")
      (libsource (lib "eagle-import") (part "C-US102-043X133"))
    )
    (comp (ref "C33")
      (value ".047uF")
      (footprint "eagle-import:C102-043X133")
      (libsource (lib "eagle-import") (part "C-US102-043X133"))
    )
    (comp (ref "C34")
      (value ".047uF")
      (footprint "eagle-import:C102-043X133")
      (libsource (lib "eagle-import") (part "C-US102-043X133"))
    )
    (comp (ref "C35")
      (value ".047uF")
      (footprint "eagle-import:C102-043X133")
      (libsource (lib "eagle-import") (part "C-US102-043X133"))
    )
    (comp (ref "C36")
      (value ".047uF")
      (footprint "eagle-import:C102-043X133")
      (libsource (lib "eagle-import") (part "C-US102-043X133"))
    )
    (comp (ref "E8")
      (value "N8881N")
      (footprint "eagle-import:DIL14")
      (libsource (lib "eagle-import") (part "N8881N"))
    )
    (comp (ref "E35")
      (value "74LS175N")
      (footprint "eagle-import:DIL16")
      (libsource (lib "eagle-import") (part "74175NLS"))
    )
    (comp (ref "E37")
      (value "74367N")
      (footprint "eagle-import:DIL16")
      (libsource (lib "eagle-import") (part "74xx-us_74367N"))
    )
    (comp (ref "E46")
      (value "74LS175N")
      (footprint "eagle-import:DIL16")
      (libsource (lib "eagle-import") (part "74175NLS"))
    )
    (comp (ref "E50")
      (value "74LS00N")
      (footprint "eagle-import:DIL14")
      (libsource (lib "eagle-import") (part "7400NLS"))
    )
    (comp (ref "E54")
      (value "74LS00N")
      (footprint "eagle-import:DIL14")
      (libsource (lib "eagle-import") (part "7400NLS"))
    )
    (comp (ref "E55")
      (value "74367N")
      (footprint "eagle-import:DIL16")
      (libsource (lib "eagle-import") (part "74xx-us_74367N"))
    )
    (comp (ref "E56")
      (value "74LS10N")
      (footprint "eagle-import:DIL14")
      (libsource (lib "eagle-import") (part "7410NLS"))
    )
    (comp (ref "E59")
      (value "74LS74N")
      (footprint "eagle-import:DIL14")
      (libsource (lib "eagle-import") (part "7474NLS"))
    )
    (comp (ref "E83")
      (value "74367N")
      (footprint "eagle-import:DIL16")
      (libsource (lib "eagle-import") (part "74367N"))
    )
    (comp (ref "E92")
      (value "74LS10N")
      (footprint "eagle-import:DIL14")
      (libsource (lib "eagle-import") (part "7410NLS"))
    )
    (comp (ref "E98")
      (value "74173N")
      (footprint "eagle-import:DIL16")
      (libsource (lib "eagle-import") (part "74173NLS"))
    )
    (comp (ref "E99")
      (value "74173N")
      (footprint "eagle-import:DIL16")
      (libsource (lib "eagle-import") (part "74173NLS"))
    )
    (comp (ref "E118")
      (value "74173N")
      (footprint "eagle-import:DIL16")
      (libsource (lib "eagle-import") (part "74173NLS"))
    )
    (comp (ref "E119")
      (value "74173N")
      (footprint "eagle-import:DIL16")
      (libsource (lib "eagle-import") (part "74173NLS"))
    )
    (comp (ref "E121")
      (value "74173N")
      (footprint "eagle-import:DIL16")
      (libsource (lib "eagle-import") (part "74173NLS"))
    )
    (comp (ref "E122")
      (value "74173N")
      (footprint "eagle-import:DIL16")
      (libsource (lib "eagle-import") (part "74173NLS"))
    )
    (comp (ref "J1")
      (value "Header")
      (footprint "eagle-import:10H")
      (libsource (lib "eagle-import") (part "10H"))
    )
    (comp (ref "R11")
      (value "10K")
      (footprint "eagle-import:0207_10")
      (libsource (lib "eagle-import") (part "R-US_0207/10"))
    )
    (comp (ref "R13")
      (value "10K")
      (footprint "eagle-import:0207_10")
      (libsource (lib "eagle-import") (part "R-US_0207/10"))
    )
    (comp (ref "R37")
      (value "10K")
      (footprint "eagle-import:0207_10")
      (libsource (lib "eagle-import") (part "R-US_0207/10"))
    )
    (comp (ref "R38")
      (value "10K")
      (footprint "eagle-import:0207_10")
      (libsource (lib "eagle-import") (part "R-US_0207/10"))
    )
    (comp (ref "R39")
      (value "10K")
      (footprint "eagle-import:0207_10")
      (libsource (lib "eagle-import") (part "R-US_0207/10"))
    )
    (comp (ref "C12")
      (value "100pF")
      (footprint "eagle-import:C063-025X075")
      (libsource (lib "eagle-import") (part "C-US"))
    )
    (comp (ref "C19")
      (value "100pF")
      (footprint "eagle-import:C063-025X075")
      (libsource (lib "eagle-import") (part "C-US"))
    )
    (comp (ref "D1")
      (value "1N5711")
      (footprint "eagle-import:DO35-10")
      (libsource (lib "eagle-import") (part "DIODE-DO35-10"))
    )
    (comp (ref "E18")
      (value "74LS00N")
      (footprint "eagle-import:DIL14")
      (libsource (lib "eagle-import") (part "7400NLS"))
    )
    (comp (ref "E24")
      (value "74LS10N")
      (footprint "eagle-import:DIL14")
      (libsource (lib "eagle-import") (part "7410NLS"))
    )
    (comp (ref "E28")
      (value "DEC23440A2")
      (footprint "eagle-import:DIL16")
      (libsource (lib "eagle-import") (part "74S287"))
    )
    (comp (ref "E30")
      (value "74LS30N")
      (footprint "eagle-import:DIL14")
      (libsource (lib "eagle-import") (part "7430NLS"))
    )
    (comp (ref "E31")
      (value "74154N")
      (footprint "eagle-import:DIL24-6")
      (libsource (lib "eagle-import") (part "74154N"))
    )
    (comp (ref "E32")
      (value "74S74N")
      (footprint "eagle-import:DIL14")
      (libsource (lib "eagle-import") (part "7474NS"))
    )
    (comp (ref "E34")
      (value "74LS42N")
      (footprint "eagle-import:DIL16")
      (libsource (lib "eagle-import") (part "7442NLS"))
    )
    (comp (ref "E36")
      (value "74LS20N")
      (footprint "eagle-import:DIL14")
      (libsource (lib "eagle-import") (part "7420NLS"))
    )
    (comp (ref "E42")
      (value "N8881N")
      (footprint "eagle-import:DIL14")
      (libsource (lib "eagle-import") (part "N8881N"))
    )
    (comp (ref "E49")
      (value "74LS10N")
      (footprint "eagle-import:DIL14")
      (libsource (lib "eagle-import") (part "7410NLS"))
    )
    (comp (ref "E57")
      (value "74LS00N")
      (footprint "eagle-import:DIL14")
      (libsource (lib "eagle-import") (part "7400NLS"))
    )
    (comp (ref "E67")
      (value "74LS08N")
      (footprint "eagle-import:DIL14")
      (libsource (lib "eagle-import") (part "7408NLS"))
    )
    (comp (ref "E69")
      (value "MC8266")
      (footprint "eagle-import:DIL16")
      (libsource (lib "eagle-import") (part "MC8266"))
    )
    (comp (ref "E70")
      (value "74LS00N")
      (footprint "eagle-import:DIL14")
      (libsource (lib "eagle-import") (part "7400NLS"))
    )
    (comp (ref "E76")
      (value "74LS74N")
      (footprint "eagle-import:DIL14")
      (libsource (lib "eagle-import") (part "7474NLS"))
    )
    (comp (ref "E79")
      (value "MC8266")
      (footprint "eagle-import:DIL16")
      (libsource (lib "eagle-import") (part "MC8266"))
    )
    (comp (ref "E80")
      (value "DEC23211A1")
      (footprint "eagle-import:DIL16")
      (libsource (lib "eagle-import") (part "74S288"))
    )
    (comp (ref "Q1")
      (value "2N3009")
      (footprint "eagle-import:TO5")
      (libsource (lib "eagle-import") (part "-NPN-TO5"))
    )
    (comp (ref "R3")
      (value "1K")
      (footprint "eagle-import:0207_10")
      (libsource (lib "eagle-import") (part "R-US_0207/10"))
    )
    (comp (ref "R4")
      (value "10K")
      (footprint "eagle-import:0207_10")
      (libsource (lib "eagle-import") (part "R-US_0207/10"))
    )
    (comp (ref "R5")
      (value "470")
      (footprint "eagle-import:0207_10")
      (libsource (lib "eagle-import") (part "R-US_0207/10"))
    )
    (comp (ref "R14")
      (value "1K")
      (footprint "eagle-import:0207_10")
      (libsource (lib "eagle-import") (part "R-US_0207/10"))
    )
    (comp (ref "R16")
      (value "1K")
      (footprint "eagle-import:0207_10")
      (libsource (lib "eagle-import") (part "R-US_0207/10"))
    )
    (comp (ref "R17")
      (value "1K")
      (footprint "eagle-import:0207_10")
      (libsource (lib "eagle-import") (part "R-US_0207/10"))
    )
    (comp (ref "R18")
      (value "10K")
      (footprint "eagle-import:0207_10")
      (libsource (lib "eagle-import") (part "R-US_0207/10"))
    )
    (comp (ref "R19")
      (value "10K")
      (footprint "eagle-import:0207_10")
      (libsource (lib "eagle-import") (part "R-US_0207/10"))
    )
    (comp (ref "R20")
      (value "14.7K 1%")
      (footprint "eagle-import:0207_15")
      (libsource (lib "eagle-import") (part "R-US_0207/15"))
    )
    (comp (ref "E1")
      (value "74173N")
      (footprint "eagle-import:DIL16")
      (libsource (lib "eagle-import") (part "74173NLS"))
    )
    (comp (ref "E52")
      (value "SP384N")
      (footprint "eagle-import:DIL14")
      (libsource (lib "eagle-import") (part "SP384N"))
    )
    (comp (ref "E62")
      (value "74173N")
      (footprint "eagle-import:DIL16")
      (libsource (lib "eagle-import") (part "74173NLS"))
    )
    (comp (ref "E63")
      (value "74S74N")
      (footprint "eagle-import:DIL14")
      (libsource (lib "eagle-import") (part "7474NS"))
    )
    (comp (ref "E73")
      (value "74173N")
      (footprint "eagle-import:DIL16")
      (libsource (lib "eagle-import") (part "74173NLS"))
    )
    (comp (ref "E84")
      (value "74367N")
      (footprint "eagle-import:DIL16")
      (libsource (lib "eagle-import") (part "74xx-us_74367N"))
    )
    (comp (ref "E93")
      (value "74LS175N")
      (footprint "eagle-import:DIL16")
      (libsource (lib "eagle-import") (part "74175NLS"))
    )
    (comp (ref "E95")
      (value "74368N")
      (footprint "eagle-import:DIL16")
      (libsource (lib "eagle-import") (part "74368N"))
    )
    (comp (ref "E96")
      (value "74368N")
      (footprint "eagle-import:DIL16")
      (libsource (lib "eagle-import") (part "74368N"))
    )
    (comp (ref "E97")
      (value "74173N")
      (footprint "eagle-import:DIL16")
      (libsource (lib "eagle-import") (part "74173NLS"))
    )
    (comp (ref "E102")
      (value "74LS175N")
      (footprint "eagle-import:DIL16")
      (libsource (lib "eagle-import") (part "74175NLS"))
    )
    (comp (ref "E103")
      (value "74LS174N")
      (footprint "eagle-import:DIL16")
      (libsource (lib "eagle-import") (part "74174NLS"))
    )
    (comp (ref "E104")
      (value "74367N")
      (footprint "eagle-import:DIL16")
      (libsource (lib "eagle-import") (part "74xx-us_74367N"))
    )
    (comp (ref "E105")
      (value "74367N")
      (footprint "eagle-import:DIL16")
      (libsource (lib "eagle-import") (part "74xx-us_74367N"))
    )
    (comp (ref "E107")
      (value "74367N")
      (footprint "eagle-import:DIL16")
      (libsource (lib "eagle-import") (part "74xx-us_74367N"))
    )
    (comp (ref "R15")
      (value "10K")
      (footprint "eagle-import:0207_10")
      (libsource (lib "eagle-import") (part "R-US_0207/10"))
    )
    (comp (ref "R28")
      (value "1K")
      (footprint "eagle-import:0207_10")
      (libsource (lib "eagle-import") (part "R-US_0207/10"))
    )
    (comp (ref "R29")
      (value "1K")
      (footprint "eagle-import:0207_10")
      (libsource (lib "eagle-import") (part "R-US_0207/10"))
    )
    (comp (ref "R30")
      (value "10K")
      (footprint "eagle-import:0207_10")
      (libsource (lib "eagle-import") (part "R-US_0207/10"))
    )
    (comp (ref "R32")
      (value "1K")
      (footprint "eagle-import:0207_10")
      (libsource (lib "eagle-import") (part "R-US_0207/10"))
    )
    (comp (ref "R33")
      (value "1K")
      (footprint "eagle-import:0207_10")
      (libsource (lib "eagle-import") (part "R-US_0207/10"))
    )
    (comp (ref "R34")
      (value "1K")
      (footprint "eagle-import:0207_10")
      (libsource (lib "eagle-import") (part "R-US_0207/10"))
    )
    (comp (ref "R35")
      (value "1K")
      (footprint "eagle-import:0207_10")
      (libsource (lib "eagle-import") (part "R-US_0207/10"))
    )
  )
  (nets
    (net (code "1") (name "+15V") (class "Default")
      (node (ref "U$1") (pin "DA2") (pinfunction "1_DA2") (pintype "bidirectional"))
    )
    (net (code "2") (name "GND") (class "Default")
      (node (ref "C1") (pin "-") (pinfunction "-_-") (pintype "passive"))
      (node (ref "C10") (pin "2") (pinfunction "2_2") (pintype "passive"))
      (node (ref "C11") (pin "2") (pinfunction "2_2") (pintype "passive"))
      (node (ref "C13") (pin "2") (pinfunction "2_2") (pintype "passive"))
      (node (ref "C14") (pin "-") (pinfunction "-_-") (pintype "passive"))
      (node (ref "C15") (pin "2") (pinfunction "2_2") (pintype "passive"))
      (node (ref "C16") (pin "-") (pinfunction "-_-") (pintype "passive"))
      (node (ref "C17") (pin "2") (pinfunction "2_2") (pintype "passive"))
      (node (ref "C18") (pin "2") (pinfunction "2_2") (pintype "passive"))
      (node (ref "C2") (pin "2") (pinfunction "2_2") (pintype "passive"))
      (node (ref "C20") (pin "2") (pinfunction "2_2") (pintype "passive"))
      (node (ref "C21") (pin "2") (pinfunction "2_2") (pintype "passive"))
      (node (ref "C22") (pin "2") (pinfunction "2_2") (pintype "passive"))
      (node (ref "C23") (pin "2") (pinfunction "2_2") (pintype "passive"))
      (node (ref "C24") (pin "-") (pinfunction "-_-") (pintype "passive"))
      (node (ref "C25") (pin "2") (pinfunction "2_2") (pintype "passive"))
      (node (ref "C26") (pin "2") (pinfunction "2_2") (pintype "passive"))
      (node (ref "C27") (pin "2") (pinfunction "2_2") (pintype "passive"))
      (node (ref "C28") (pin "2") (pinfunction "2_2") (pintype "passive"))
      (node (ref "C29") (pin "2") (pinfunction "2_2") (pintype "passive"))
      (node (ref "C3") (pin "2") (pinfunction "2_2") (pintype "passive"))
      (node (ref "C31") (pin "2") (pinfunction "2_2") (pintype "passive"))
      (node (ref "C32") (pin "2") (pinfunction "2_2") (pintype "passive"))
      (node (ref "C33") (pin "2") (pinfunction "2_2") (pintype "passive"))
      (node (ref "C34") (pin "2") (pinfunction "2_2") (pintype "passive"))
      (node (ref "C35") (pin "2") (pinfunction "2_2") (pintype "passive"))
      (node (ref "C36") (pin "2") (pinfunction "2_2") (pintype "passive"))
      (node (ref "C4") (pin "2") (pinfunction "2_2") (pintype "passive"))
      (node (ref "C5") (pin "2") (pinfunction "2_2") (pintype "passive"))
      (node (ref "C6") (pin "2") (pinfunction "2_2") (pintype "passive"))
      (node (ref "C7") (pin "2") (pinfunction "2_2") (pintype "passive"))
      (node (ref "C8") (pin "-") (pinfunction "-_-") (pintype "passive"))
      (node (ref "C9") (pin "2") (pinfunction "2_2") (pintype "passive"))
      (node (ref "E1") (pin "10") (pinfunction "G2_10") (pintype "input"))
      (node (ref "E1") (pin "9") (pinfunction "G1_9") (pintype "input"))
      (node (ref "E101") (pin "8") (pinfunction "-UB_8") (pintype "power_in"))
      (node (ref "E109") (pin "19") (pinfunction "~{CE}_19") (pintype "input"))
      (node (ref "E11") (pin "12") (pinfunction "I1_12") (pintype "input"))
      (node (ref "E11") (pin "5") (pinfunction "I1_5") (pintype "input"))
      (node (ref "E11") (pin "6") (pinfunction "I0_6") (pintype "input"))
      (node (ref "E11") (pin "9") (pinfunction "I0_9") (pintype "input"))
      (node (ref "E113") (pin "13") (pinfunction "~{G1}_13") (pintype "input"))
      (node (ref "E113") (pin "14") (pinfunction "~{G2}_14") (pintype "input"))
      (node (ref "E113") (pin "2") (pinfunction "A5_2") (pintype "input"))
      (node (ref "E113") (pin "7") (pinfunction "A2_7") (pintype "input"))
      (node (ref "E118") (pin "10") (pinfunction "G2_10") (pintype "input"))
      (node (ref "E118") (pin "15") (pinfunction "CLR_15") (pintype "input"))
      (node (ref "E118") (pin "9") (pinfunction "G1_9") (pintype "input"))
      (node (ref "E119") (pin "10") (pinfunction "G2_10") (pintype "input"))
      (node (ref "E119") (pin "15") (pinfunction "CLR_15") (pintype "input"))
      (node (ref "E119") (pin "9") (pinfunction "G1_9") (pintype "input"))
      (node (ref "E120") (pin "1") (pinfunction "G_1") (pintype "input"))
      (node (ref "E120") (pin "15") (pinfunction "G_15") (pintype "input"))
      (node (ref "E121") (pin "10") (pinfunction "G2_10") (pintype "input"))
      (node (ref "E121") (pin "9") (pinfunction "G1_9") (pintype "input"))
      (node (ref "E122") (pin "10") (pinfunction "G2_10") (pintype "input"))
      (node (ref "E122") (pin "15") (pinfunction "CLR_15") (pintype "input"))
      (node (ref "E122") (pin "9") (pinfunction "G1_9") (pintype "input"))
      (node (ref "E14") (pin "19") (pinfunction "~{CE}_19") (pintype "input"))
      (node (ref "E25") (pin "12") (pinfunction "I1_12") (pintype "input"))
      (node (ref "E25") (pin "5") (pinfunction "I1_5") (pintype "input"))
      (node (ref "E25") (pin "6") (pinfunction "I0_6") (pintype "input"))
      (node (ref "E25") (pin "9") (pinfunction "I0_9") (pintype "input"))
      (node (ref "E26") (pin "12") (pinfunction "-UB_12") (pintype "power_in"))
      (node (ref "E3") (pin "11") (pinfunction "I0_11") (pintype "input"))
      (node (ref "E3") (pin "5") (pinfunction "I1_5") (pintype "input"))
      (node (ref "E3") (pin "6") (pinfunction "I0_6") (pintype "input"))
      (node (ref "E32") (pin "3") (pinfunction "CLK_3") (pintype "input"))
      (node (ref "E41") (pin "5") (pinfunction "I1_5") (pintype "input"))
      (node (ref "E41") (pin "6") (pinfunction "I0_6") (pintype "input"))
      (node (ref "E51") (pin "11") (pinfunction "I0_11") (pintype "input"))
      (node (ref "E51") (pin "5") (pinfunction "I1_5") (pintype "input"))
      (node (ref "E51") (pin "6") (pinfunction "I0_6") (pintype "input"))
      (node (ref "E52") (pin "10") (pinfunction "I1_10") (pintype "input"))
      (node (ref "E52") (pin "11") (pinfunction "I0_11") (pintype "input"))
      (node (ref "E52") (pin "5") (pinfunction "I1_5") (pintype "input"))
      (node (ref "E52") (pin "7") (pinfunction "I1_7") (pintype "input"))
      (node (ref "E53") (pin "12") (pinfunction "I1_12") (pintype "input"))
      (node (ref "E53") (pin "4") (pinfunction "I0_4") (pintype "input"))
      (node (ref "E53") (pin "6") (pinfunction "I0_6") (pintype "input"))
      (node (ref "E53") (pin "9") (pinfunction "I0_9") (pintype "input"))
      (node (ref "E55") (pin "10") (pinfunction "1A4_10") (pintype "input"))
      (node (ref "E55") (pin "2") (pinfunction "1A1_2") (pintype "input"))
      (node (ref "E55") (pin "4") (pinfunction "1A2_4") (pintype "input"))
      (node (ref "E55") (pin "6") (pinfunction "1A3_6") (pintype "input"))
      (node (ref "E61") (pin "4") (pinfunction "I0_4") (pintype "input"))
      (node (ref "E62") (pin "10") (pinfunction "G2_10") (pintype "input"))
      (node (ref "E62") (pin "9") (pinfunction "G1_9") (pintype "input"))
      (node (ref "E65") (pin "2") (pinfunction "D_2") (pintype "input"))
      (node (ref "E68") (pin "1") (pinfunction "B3_1") (pintype "input"))
      (node (ref "E68") (pin "12") (pinfunction "A1_12") (pintype "input"))
      (node (ref "E68") (pin "13") (pinfunction "A2_13") (pintype "input"))
      (node (ref "E68") (pin "14") (pinfunction "B2_14") (pintype "input"))
      (node (ref "E68") (pin "15") (pinfunction "A3_15") (pintype "input"))
      (node (ref "E69") (pin "11") (pinfunction "B2_11") (pintype "input"))
      (node (ref "E69") (pin "2") (pinfunction "B0_2") (pintype "input"))
      (node (ref "E69") (pin "5") (pinfunction "B1_5") (pintype "input"))
      (node (ref "E69") (pin "7") (pinfunction "S1_7") (pintype "input"))
      (node (ref "E71") (pin "12") (pinfunction "I1_12") (pintype "input"))
      (node (ref "E71") (pin "5") (pinfunction "I1_5") (pintype "input"))
      (node (ref "E71") (pin "6") (pinfunction "I0_6") (pintype "input"))
      (node (ref "E71") (pin "9") (pinfunction "I0_9") (pintype "input"))
      (node (ref "E72") (pin "4") (pinfunction "I0_4") (pintype "input"))
      (node (ref "E72") (pin "6") (pinfunction "I0_6") (pintype "input"))
      (node (ref "E73") (pin "10") (pinfunction "G2_10") (pintype "input"))
      (node (ref "E73") (pin "9") (pinfunction "G1_9") (pintype "input"))
      (node (ref "E74") (pin "13") (pinfunction "~{G1}_13") (pintype "input"))
      (node (ref "E74") (pin "14") (pinfunction "~{G2}_14") (pintype "input"))
      (node (ref "E76") (pin "2") (pinfunction "D_2") (pintype "input"))
      (node (ref "E77") (pin "1") (pinfunction "A_1") (pintype "input"))
      (node (ref "E78") (pin "2") (pinfunction "A<B_I_2") (pintype "input"))
      (node (ref "E78") (pin "4") (pinfunction "A>B_I_4") (pintype "input"))
      (node (ref "E79") (pin "7") (pinfunction "S1_7") (pintype "input"))
      (node (ref "E80") (pin "15") (pinfunction "~{G}_15") (pintype "input"))
      (node (ref "E81") (pin "19") (pinfunction "~{CE}_19") (pintype "input"))
      (node (ref "E81") (pin "20") (pinfunction "I15_20") (pintype "input"))
      (node (ref "E83") (pin "8") (pinfunction "-UB_8") (pintype "power_in"))
      (node (ref "E87") (pin "1") (pinfunction "A6_1") (pintype "input"))
      (node (ref "E87") (pin "13") (pinfunction "~{G1}_13") (pintype "input"))
      (node (ref "E87") (pin "14") (pinfunction "~{G2}_14") (pintype "input"))
      (node (ref "E89") (pin "10") (pinfunction "0_10") (pintype "input"))
      (node (ref "E89") (pin "5") (pinfunction "EI_5") (pintype "input"))
      (node (ref "E98") (pin "10") (pinfunction "G2_10") (pintype "input"))
      (node (ref "E98") (pin "9") (pinfunction "G1_9") (pintype "input"))
      (node (ref "E99") (pin "10") (pinfunction "G2_10") (pintype "input"))
      (node (ref "E99") (pin "9") (pinfunction "G1_9") (pintype "input"))
      (node (ref "J1") (pin "10") (pinfunction "10_10") (pintype "passive"))
      (node (ref "J1") (pin "2") (pinfunction "2_2") (pintype "passive"))
      (node (ref "J1") (pin "4") (pinfunction "4_4") (pintype "passive"))
      (node (ref "J1") (pin "6") (pinfunction "6_6") (pintype "passive"))
      (node (ref "J1") (pin "8") (pinfunction "8_8") (pintype "passive"))
      (node (ref "J1") (pin "9") (pinfunction "9_9") (pintype "passive"))
      (node (ref "Q1") (pin "1") (pinfunction "E_1") (pintype "passive"))
      (node (ref "U$1") (pin "AC1") (pinfunction "1_AC1") (pintype "bidirectional"))
      (node (ref "U$1") (pin "AC2") (pinfunction "1_AC2") (pintype "bidirectional"))
      (node (ref "U$1") (pin "AF1") (pinfunction "1_AF1") (pintype "bidirectional"))
      (node (ref "U$1") (pin "AF2") (pinfunction "1_AF2") (pintype "bidirectional"))
      (node (ref "U$1") (pin "AN1") (pinfunction "1_AN1") (pintype "bidirectional"))
      (node (ref "U$1") (pin "AN2") (pinfunction "1_AN2") (pintype "bidirectional"))
      (node (ref "U$1") (pin "AT1") (pinfunction "1_AT1") (pintype "bidirectional"))
      (node (ref "U$1") (pin "AT2") (pinfunction "1_AT2") (pintype "bidirectional"))
      (node (ref "U$1") (pin "BC1") (pinfunction "1_BC1") (pintype "bidirectional"))
      (node (ref "U$1") (pin "BC2") (pinfunction "1_BC2") (pintype "bidirectional"))
      (node (ref "U$1") (pin "BF1") (pinfunction "1_BF1") (pintype "bidirectional"))
      (node (ref "U$1") (pin "BF2") (pinfunction "1_BF2") (pintype "bidirectional"))
      (node (ref "U$1") (pin "BN1") (pinfunction "1_BN1") (pintype "bidirectional"))
      (node (ref "U$1") (pin "BN2") (pinfunction "1_BN2") (pintype "bidirectional"))
      (node (ref "U$1") (pin "BT1") (pinfunction "1_BT1") (pintype "bidirectional"))
      (node (ref "U$1") (pin "BT2") (pinfunction "1_BT2") (pintype "bidirectional"))
      (node (ref "U$1") (pin "CC1") (pinfunction "1_CC1") (pintype "bidirectional"))
      (node (ref "U$1") (pin "CC2") (pinfunction "1_CC2") (pintype "bidirectional"))
      (node (ref "U$1") (pin "CF1") (pinfunction "1_CF1") (pintype "bidirectional"))
      (node (ref "U$1") (pin "CF2") (pinfunction "1_CF2") (pintype "bidirectional"))
      (node (ref "U$1") (pin "CN1") (pinfunction "1_CN1") (pintype "bidirectional"))
      (node (ref "U$1") (pin "CN2") (pinfunction "1_CN2") (pintype "bidirectional"))
      (node (ref "U$1") (pin "CT1") (pinfunction "1_CT1") (pintype "bidirectional"))
      (node (ref "U$1") (pin "CT2") (pinfunction "1_CT2") (pintype "bidirectional"))
      (node (ref "U$1") (pin "DC1") (pinfunction "1_DC1") (pintype "bidirectional"))
      (node (ref "U$1") (pin "DC2") (pinfunction "1_DC2") (pintype "bidirectional"))
      (node (ref "U$1") (pin "DF1") (pinfunction "1_DF1") (pintype "bidirectional"))
      (node (ref "U$1") (pin "DF2") (pinfunction "1_DF2") (pintype "bidirectional"))
      (node (ref "U$1") (pin "DN1") (pinfunction "1_DN1") (pintype "bidirectional"))
      (node (ref "U$1") (pin "DN2") (pinfunction "1_DN2") (pintype "bidirectional"))
      (node (ref "U$1") (pin "DT1") (pinfunction "1_DT1") (pintype "bidirectional"))
      (node (ref "U$1") (pin "DT2") (pinfunction "1_DT2") (pintype "bidirectional"))
    )
    (net (code "3") (name "IBB_0") (class "Default")
      (node (ref "E109") (pin "27") (pinfunction "I8_27") (pintype "input"))
      (node (ref "E116") (pin "15") (pinfunction "Q4_15") (pintype "output"))
    )
    (net (code "4") (name "IBB_1") (class "Default")
      (node (ref "E109") (pin "2") (pinfunction "I7_2") (pintype "input"))
      (node (ref "E116") (pin "10") (pinfunction "Q3_10") (pintype "output"))
    )
    (net (code "5") (name "INITIALIZE") (class "Default")
      (node (ref "E53") (pin "11") (pinfunction "I0_11") (pintype "input"))
      (node (ref "U$1") (pin "CR1") (pinfunction "1_CR1") (pintype "bidirectional"))
    )
    (net (code "6") (name "INTERNAL_IO") (class "Default")
      (node (ref "E42") (pin "10") (pinfunction "O_10") (pintype "open_collector"))
      (node (ref "U$1") (pin "CL1") (pinfunction "1_CL1") (pintype "bidirectional"))
    )
    (net (code "7") (name "LBM+RBMN") (class "Default")
      (node (ref "E74") (pin "5") (pinfunction "A0_5") (pintype "input"))
      (node (ref "E81") (pin "17") (pinfunction "O1_17") (pintype "tri_state"))
    )
    (net (code "8") (name "MAMS_LD_CTL") (class "Default")
      (node (ref "E3") (pin "4") (pinfunction "I0_4") (pintype "input"))
      (node (ref "U$1") (pin "BH2") (pinfunction "1_BH2") (pintype "bidirectional"))
    )
    (net (code "9") (name "MUX_C0") (class "Default")
      (node (ref "E109") (pin "20") (pinfunction "I15_20") (pintype "input"))
      (node (ref "E89") (pin "6") (pinfunction "A2_6") (pintype "output"))
    )
    (net (code "10") (name "MUX_C1") (class "Default")
      (node (ref "E109") (pin "21") (pinfunction "I14_21") (pintype "input"))
      (node (ref "E89") (pin "7") (pinfunction "A1_7") (pintype "output"))
    )
    (net (code "11") (name "MUX_C2") (class "Default")
      (node (ref "E109") (pin "22") (pinfunction "I13_22") (pintype "input"))
      (node (ref "E89") (pin "9") (pinfunction "A0_9") (pintype "output"))
    )
    (net (code "12") (name "Net-(E1A-D2)") (class "Default")
      (node (ref "E1") (pin "13") (pinfunction "D2_13") (pintype "input"))
      (node (ref "E2") (pin "6") (pinfunction "O_6") (pintype "output"))
    )
    (net (code "13") (name "Net-(E1A-D3)") (class "Default")
      (node (ref "E1") (pin "12") (pinfunction "D3_12") (pintype "input"))
      (node (ref "E2") (pin "4") (pinfunction "O_4") (pintype "output"))
    )
    (net (code "14") (name "Net-(E1A-D4)") (class "Default")
      (node (ref "E1") (pin "11") (pinfunction "D4_11") (pintype "input"))
      (node (ref "E2") (pin "2") (pinfunction "O_2") (pintype "output"))
    )
    (net (code "15") (name "Net-(E2D-I)") (class "Default")
      (node (ref "E2") (pin "9") (pinfunction "I_9") (pintype "input"))
      (node (ref "E33") (pin "6") (pinfunction "O_6") (pintype "output"))
    )
    (net (code "16") (name "Net-(E2D-O)") (class "Default")
      (node (ref "E2") (pin "8") (pinfunction "O_8") (pintype "output"))
      (node (ref "E32") (pin "12") (pinfunction "D_12") (pintype "input"))
    )
    (net (code "17") (name "Net-(E3D-O)") (class "Default")
      (node (ref "E3") (pin "13") (pinfunction "O_13") (pintype "output"))
      (node (ref "E4") (pin "8") (pinfunction "I0_8") (pintype "input"))
    )
    (net (code "18") (name "Net-(E4C-I1)") (class "Default")
      (node (ref "E4") (pin "9") (pinfunction "I1_9") (pintype "input"))
      (node (ref "E6") (pin "11") (pinfunction "O_11") (pintype "output"))
    )
    (net (code "19") (name "Net-(E6A-O)") (class "Default")
      (node (ref "E6") (pin "3") (pinfunction "O_3") (pintype "output"))
      (node (ref "E6") (pin "4") (pinfunction "I0_4") (pintype "input"))
    )
    (net (code "20") (name "Net-(E12A-D0)") (class "Default")
      (node (ref "E12") (pin "7") (pinfunction "D0_7") (pintype "input"))
      (node (ref "E12") (pin "9") (pinfunction "D1_9") (pintype "input"))
      (node (ref "E13") (pin "7") (pinfunction "D0_7") (pintype "input"))
      (node (ref "E13") (pin "9") (pinfunction "D1_9") (pintype "input"))
      (node (ref "E20") (pin "1") (pinfunction "O_1") (pintype "open_collector"))
      (node (ref "E20") (pin "13") (pinfunction "O_13") (pintype "open_collector"))
      (node (ref "E20") (pin "4") (pinfunction "O_4") (pintype "open_collector"))
      (node (ref "E45") (pin "7") (pinfunction "D0_7") (pintype "input"))
      (node (ref "E45") (pin "9") (pinfunction "D1_9") (pintype "input"))
      (node (ref "R10") (pin "1") (pinfunction "1_1") (pintype "passive"))
    )
    (net (code "21") (name "Net-(E12A-O0)") (class "Default")
      (node (ref "E12") (pin "14") (pinfunction "O0_14") (pintype "input"))
      (node (ref "E5") (pin "8") (pinfunction "O_8") (pintype "output"))
    )
    (net (code "22") (name "Net-(E12A-O1)") (class "Default")
      (node (ref "E12") (pin "11") (pinfunction "O1_11") (pintype "input"))
      (node (ref "E5") (pin "6") (pinfunction "O_6") (pintype "output"))
    )
    (net (code "23") (name "Net-(E12A-O2)") (class "Default")
      (node (ref "E12") (pin "2") (pinfunction "O2_2") (pintype "input"))
      (node (ref "E5") (pin "4") (pinfunction "O_4") (pintype "output"))
    )
    (net (code "24") (name "Net-(E12A-O3)") (class "Default")
      (node (ref "E12") (pin "5") (pinfunction "O3_5") (pintype "input"))
      (node (ref "E5") (pin "2") (pinfunction "O_2") (pintype "output"))
    )
    (net (code "25") (name "Net-(E13A-O0)") (class "Default")
      (node (ref "E13") (pin "14") (pinfunction "O0_14") (pintype "input"))
      (node (ref "E7") (pin "8") (pinfunction "O_8") (pintype "output"))
    )
    (net (code "26") (name "Net-(E13A-O1)") (class "Default")
      (node (ref "E13") (pin "11") (pinfunction "O1_11") (pintype "input"))
      (node (ref "E7") (pin "6") (pinfunction "O_6") (pintype "output"))
    )
    (net (code "27") (name "Net-(E13A-O2)") (class "Default")
      (node (ref "E13") (pin "2") (pinfunction "O2_2") (pintype "input"))
      (node (ref "E7") (pin "4") (pinfunction "O_4") (pintype "output"))
    )
    (net (code "28") (name "Net-(E13A-O3)") (class "Default")
      (node (ref "E13") (pin "5") (pinfunction "O3_5") (pintype "input"))
      (node (ref "E7") (pin "2") (pinfunction "O_2") (pintype "output"))
    )
    (net (code "29") (name "Net-(E14A-I15)") (class "Default")
      (node (ref "E14") (pin "20") (pinfunction "I15_20") (pintype "input"))
      (node (ref "E21") (pin "12") (pinfunction "O_12") (pintype "output"))
    )
    (net (code "30") (name "Net-(E14A-O0)") (class "Default")
      (node (ref "E14") (pin "18") (pinfunction "O0_18") (pintype "tri_state"))
      (node (ref "E20") (pin "11") (pinfunction "I0_11") (pintype "input"))
    )
    (net (code "31") (name "Net-(E14A-O1)") (class "Default")
      (node (ref "E14") (pin "17") (pinfunction "O1_17") (pintype "tri_state"))
      (node (ref "E19") (pin "8") (pinfunction "I0_8") (pintype "input"))
      (node (ref "E19") (pin "9") (pinfunction "I1_9") (pintype "input"))
    )
    (net (code "32") (name "Net-(E14A-O2)") (class "Default")
      (node (ref "E14") (pin "16") (pinfunction "O2_16") (pintype "tri_state"))
      (node (ref "E19") (pin "11") (pinfunction "I0_11") (pintype "input"))
      (node (ref "E19") (pin "12") (pinfunction "I1_12") (pintype "input"))
    )
    (net (code "33") (name "Net-(E15A-Q1)") (class "Default")
      (node (ref "E15") (pin "2") (pinfunction "Q1_2") (pintype "output"))
      (node (ref "E16") (pin "26") (pinfunction "I9_26") (pintype "input"))
    )
    (net (code "34") (name "Net-(E15A-Q2)") (class "Default")
      (node (ref "E15") (pin "5") (pinfunction "Q2_5") (pintype "output"))
      (node (ref "E16") (pin "27") (pinfunction "I8_27") (pintype "input"))
      (node (ref "E23") (pin "11") (pinfunction "3A_11") (pintype "input"))
    )
    (net (code "35") (name "Net-(E15A-Q3)") (class "Default")
      (node (ref "E15") (pin "7") (pinfunction "Q3_7") (pintype "output"))
      (node (ref "E16") (pin "2") (pinfunction "I7_2") (pintype "input"))
      (node (ref "E23") (pin "14") (pinfunction "4A_14") (pintype "input"))
    )
    (net (code "36") (name "Net-(E15A-Q4)") (class "Default")
      (node (ref "E15") (pin "10") (pinfunction "Q4_10") (pintype "output"))
      (node (ref "E16") (pin "3") (pinfunction "I6_3") (pintype "input"))
      (node (ref "E23") (pin "5") (pinfunction "2A_5") (pintype "input"))
    )
    (net (code "37") (name "Net-(E15A-Q5)") (class "Default")
      (node (ref "E15") (pin "12") (pinfunction "Q5_12") (pintype "output"))
      (node (ref "E16") (pin "4") (pinfunction "I5_4") (pintype "input"))
      (node (ref "E23") (pin "10") (pinfunction "3B_10") (pintype "input"))
    )
    (net (code "38") (name "Net-(E15A-Q6)") (class "Default")
      (node (ref "E15") (pin "15") (pinfunction "Q6_15") (pintype "output"))
      (node (ref "E16") (pin "5") (pinfunction "I4_5") (pintype "input"))
      (node (ref "E23") (pin "13") (pinfunction "4B_13") (pintype "input"))
    )
    (net (code "39") (name "Net-(E16A-I10)") (class "Default")
      (node (ref "E16") (pin "25") (pinfunction "I10_25") (pintype "input"))
      (node (ref "E17") (pin "15") (pinfunction "Q6_15") (pintype "output"))
      (node (ref "E23") (pin "2") (pinfunction "1A_2") (pintype "input"))
    )
    (net (code "40") (name "Net-(E16A-I11)") (class "Default")
      (node (ref "E16") (pin "24") (pinfunction "I11_24") (pintype "input"))
      (node (ref "E17") (pin "12") (pinfunction "Q5_12") (pintype "output"))
      (node (ref "E23") (pin "6") (pinfunction "2B_6") (pintype "input"))
    )
    (net (code "41") (name "Net-(E16A-I12)") (class "Default")
      (node (ref "E16") (pin "23") (pinfunction "I12_23") (pintype "input"))
      (node (ref "E17") (pin "10") (pinfunction "Q4_10") (pintype "output"))
      (node (ref "E23") (pin "3") (pinfunction "1B_3") (pintype "input"))
    )
    (net (code "42") (name "Net-(E16A-I13)") (class "Default")
      (node (ref "E16") (pin "22") (pinfunction "I13_22") (pintype "input"))
      (node (ref "E17") (pin "7") (pinfunction "Q3_7") (pintype "output"))
    )
    (net (code "43") (name "Net-(E16A-I14)") (class "Default")
      (node (ref "E16") (pin "21") (pinfunction "I14_21") (pintype "input"))
      (node (ref "E17") (pin "5") (pinfunction "Q2_5") (pintype "output"))
    )
    (net (code "44") (name "Net-(E16A-I15)") (class "Default")
      (node (ref "E16") (pin "20") (pinfunction "I15_20") (pintype "input"))
      (node (ref "E17") (pin "2") (pinfunction "Q1_2") (pintype "output"))
    )
    (net (code "45") (name "Net-(E16A-~{CE})") (class "Default")
      (node (ref "E16") (pin "19") (pinfunction "~{CE}_19") (pintype "input"))
      (node (ref "E22") (pin "8") (pinfunction "O_8") (pintype "output"))
    )
    (net (code "46") (name "Net-(E18A-O)") (class "Default")
      (node (ref "E18") (pin "3") (pinfunction "O_3") (pintype "output"))
      (node (ref "E9") (pin "12") (pinfunction "I2_12") (pintype "input"))
    )
    (net (code "47") (name "Net-(E18B-I1)") (class "Default")
      (node (ref "E18") (pin "5") (pinfunction "I1_5") (pintype "input"))
      (node (ref "E22") (pin "10") (pinfunction "O_10") (pintype "output"))
    )
    (net (code "48") (name "Net-(E18B-O)") (class "Default")
      (node (ref "E18") (pin "6") (pinfunction "O_6") (pintype "output"))
      (node (ref "E33") (pin "10") (pinfunction "I1_10") (pintype "input"))
      (node (ref "E9") (pin "10") (pinfunction "I1_10") (pintype "input"))
    )
    (net (code "49") (name "Net-(E18C-O)") (class "Default")
      (node (ref "E18") (pin "8") (pinfunction "O_8") (pintype "output"))
      (node (ref "E24") (pin "5") (pinfunction "I2_5") (pintype "input"))
    )
    (net (code "50") (name "Net-(E18D-O)") (class "Default")
      (node (ref "E18") (pin "11") (pinfunction "O_11") (pintype "output"))
      (node (ref "E8") (pin "12") (pinfunction "I1_12") (pintype "input"))
    )
    (net (code "51") (name "Net-(E21B-O)") (class "Default")
      (node (ref "E21") (pin "6") (pinfunction "O_6") (pintype "output"))
      (node (ref "E6") (pin "5") (pinfunction "I1_5") (pintype "input"))
    )
    (net (code "52") (name "Net-(E21C-O)") (class "Default")
      (node (ref "E21") (pin "8") (pinfunction "O_8") (pintype "output"))
      (node (ref "E28") (pin "15") (pinfunction "A7_15") (pintype "input"))
    )
    (net (code "53") (name "Net-(E22C-O)") (class "Default")
      (node (ref "E22") (pin "6") (pinfunction "O_6") (pintype "output"))
      (node (ref "E6") (pin "2") (pinfunction "I1_2") (pintype "input"))
    )
    (net (code "54") (name "Net-(E22D-I)") (class "Default")
      (node (ref "E22") (pin "9") (pinfunction "I_9") (pintype "input"))
      (node (ref "E9") (pin "6") (pinfunction "O_6") (pintype "output"))
    )
    (net (code "55") (name "Net-(E22F-O)") (class "Default")
      (node (ref "E22") (pin "12") (pinfunction "O_12") (pintype "output"))
      (node (ref "E42") (pin "6") (pinfunction "I1_6") (pintype "input"))
    )
    (net (code "56") (name "Net-(E23A-G)") (class "Default")
      (node (ref "E23") (pin "15") (pinfunction "G_15") (pintype "input"))
      (node (ref "E33") (pin "3") (pinfunction "O_3") (pintype "output"))
    )
    (net (code "57") (name "Net-(E24A-I0)") (class "Default")
      (node (ref "E24") (pin "1") (pinfunction "I0_1") (pintype "input"))
      (node (ref "E30") (pin "8") (pinfunction "O_8") (pintype "output"))
    )
    (net (code "58") (name "Net-(E24A-I2)") (class "Default")
      (node (ref "E24") (pin "13") (pinfunction "I2_13") (pintype "input"))
      (node (ref "E49") (pin "8") (pinfunction "O_8") (pintype "output"))
      (node (ref "E57") (pin "2") (pinfunction "I1_2") (pintype "input"))
      (node (ref "E67") (pin "9") (pinfunction "I0_9") (pintype "input"))
    )
    (net (code "59") (name "Net-(E24A-O)") (class "Default")
      (node (ref "E24") (pin "12") (pinfunction "O_12") (pintype "output"))
      (node (ref "E39") (pin "5") (pinfunction "I_5") (pintype "input"))
      (node (ref "E42") (pin "2") (pinfunction "I0_2") (pintype "input"))
      (node (ref "E42") (pin "3") (pinfunction "I1_3") (pintype "input"))
    )
    (net (code "60") (name "Net-(E24B-I0)") (class "Default")
      (node (ref "E24") (pin "3") (pinfunction "I0_3") (pintype "input"))
      (node (ref "E39") (pin "6") (pinfunction "O_6") (pintype "output"))
    )
    (net (code "61") (name "Net-(E24B-O)") (class "Default")
      (node (ref "E24") (pin "6") (pinfunction "O_6") (pintype "output"))
      (node (ref "E33") (pin "4") (pinfunction "I0_4") (pintype "input"))
    )
    (net (code "62") (name "Net-(E24C-I1)") (class "Default")
      (node (ref "E24") (pin "10") (pinfunction "I1_10") (pintype "input"))
      (node (ref "E39") (pin "8") (pinfunction "O_8") (pintype "output"))
    )
    (net (code "63") (name "Net-(E24C-O)") (class "Default")
      (node (ref "E24") (pin "8") (pinfunction "O_8") (pintype "output"))
      (node (ref "E42") (pin "8") (pinfunction "I0_8") (pintype "input"))
      (node (ref "E42") (pin "9") (pinfunction "I1_9") (pintype "input"))
    )
    (net (code "64") (name "Net-(E26C-2D)") (class "Default")
      (node (ref "E26") (pin "7") (pinfunction "2D_7") (pintype "input"))
      (node (ref "E29") (pin "10") (pinfunction "O_10") (pintype "output"))
    )
    (net (code "65") (name "Net-(E26D-1D)") (class "Default")
      (node (ref "E26") (pin "2") (pinfunction "1D_2") (pintype "input"))
      (node (ref "E41") (pin "3") (pinfunction "O_3") (pintype "output"))
    )
    (net (code "66") (name "Net-(E27B-O)") (class "Default")
      (node (ref "E27") (pin "6") (pinfunction "O_6") (pintype "output"))
      (node (ref "E8") (pin "5") (pinfunction "I0_5") (pintype "input"))
    )
    (net (code "67") (name "Net-(E28A-O1)") (class "Default")
      (node (ref "E28") (pin "11") (pinfunction "O1_11") (pintype "tri_state"))
      (node (ref "R3") (pin "1") (pinfunction "1_1") (pintype "passive"))
    )
    (net (code "68") (name "Net-(E29A-O)") (class "Default")
      (node (ref "E29") (pin "1") (pinfunction "O_1") (pintype "output"))
      (node (ref "E49") (pin "3") (pinfunction "I0_3") (pintype "input"))
    )
    (net (code "69") (name "Net-(E29B-I1)") (class "Default")
      (node (ref "E29") (pin "6") (pinfunction "I1_6") (pintype "input"))
      (node (ref "E3") (pin "3") (pinfunction "O_3") (pintype "output"))
      (node (ref "E75") (pin "6") (pinfunction "I0_6") (pintype "input"))
    )
    (net (code "70") (name "Net-(E29D-O)") (class "Default")
      (node (ref "E29") (pin "13") (pinfunction "O_13") (pintype "output"))
      (node (ref "E88") (pin "9") (pinfunction "CLK_9") (pintype "input"))
    )
    (net (code "71") (name "Net-(E31A-G2)") (class "Default")
      (node (ref "E31") (pin "19") (pinfunction "G2_19") (pintype "input"))
      (node (ref "E47") (pin "3") (pinfunction "I1_3") (pintype "input"))
      (node (ref "E47") (pin "4") (pinfunction "O_4") (pintype "output"))
    )
    (net (code "72") (name "Net-(E32A-~{Q})") (class "Default")
      (node (ref "E32") (pin "6") (pinfunction "~{Q}_6") (pintype "output"))
      (node (ref "E8") (pin "11") (pinfunction "I0_11") (pintype "input"))
    )
    (net (code "73") (name "Net-(E32B-CLR)") (class "Default")
      (node (ref "E32") (pin "13") (pinfunction "CLR_13") (pintype "input"))
      (node (ref "R4") (pin "1") (pinfunction "1_1") (pintype "passive"))
    )
    (net (code "74") (name "Net-(E33C-I0)") (class "Default")
      (node (ref "E33") (pin "9") (pinfunction "I0_9") (pintype "input"))
      (node (ref "E58") (pin "12") (pinfunction "O_12") (pintype "output"))
      (node (ref "E76") (pin "10") (pinfunction "PRE_10") (pintype "input"))
      (node (ref "E9") (pin "9") (pinfunction "I0_9") (pintype "input"))
    )
    (net (code "75") (name "Net-(E35A-CLK)") (class "Default")
      (node (ref "E35") (pin "9") (pinfunction "CLK_9") (pintype "input"))
      (node (ref "E46") (pin "9") (pinfunction "CLK_9") (pintype "input"))
      (node (ref "E48") (pin "4") (pinfunction "O_4") (pintype "output"))
    )
    (net (code "76") (name "Net-(E38C-O)") (class "Default")
      (node (ref "E38") (pin "8") (pinfunction "O_8") (pintype "output"))
      (node (ref "E48") (pin "12") (pinfunction "I1_12") (pintype "input"))
    )
    (net (code "77") (name "Net-(E39A-O)") (class "Default")
      (node (ref "E39") (pin "2") (pinfunction "O_2") (pintype "output"))
      (node (ref "E50") (pin "2") (pinfunction "I1_2") (pintype "input"))
    )
    (net (code "78") (name "Net-(E39B-O)") (class "Default")
      (node (ref "E39") (pin "4") (pinfunction "O_4") (pintype "output"))
      (node (ref "E50") (pin "13") (pinfunction "I1_13") (pintype "input"))
    )
    (net (code "79") (name "Net-(E39D-I)") (class "Default")
      (node (ref "E39") (pin "9") (pinfunction "I_9") (pintype "input"))
      (node (ref "E47") (pin "1") (pinfunction "O_1") (pintype "output"))
    )
    (net (code "80") (name "Net-(E39E-O)") (class "Default")
      (node (ref "E39") (pin "10") (pinfunction "O_10") (pintype "output"))
      (node (ref "E89") (pin "13") (pinfunction "3_13") (pintype "input"))
    )
    (net (code "81") (name "Net-(E39F-I)") (class "Default")
      (node (ref "E39") (pin "13") (pinfunction "I_13") (pintype "input"))
      (node (ref "E48") (pin "10") (pinfunction "O_10") (pintype "output"))
    )
    (net (code "82") (name "Net-(E41B-O)") (class "Default")
      (node (ref "E41") (pin "12") (pinfunction "I1_12") (pintype "input"))
      (node (ref "E41") (pin "2") (pinfunction "O_2") (pintype "output"))
    )
    (net (code "83") (name "Net-(E41C-O)") (class "Default")
      (node (ref "E41") (pin "14") (pinfunction "O_14") (pintype "output"))
      (node (ref "E66") (pin "5") (pinfunction "I1_5") (pintype "input"))
    )
    (net (code "84") (name "Net-(E44A-O)") (class "Default")
      (node (ref "E44") (pin "2") (pinfunction "O_2") (pintype "output"))
      (node (ref "E45") (pin "5") (pinfunction "O3_5") (pintype "input"))
    )
    (net (code "85") (name "Net-(E44B-O)") (class "Default")
      (node (ref "E44") (pin "4") (pinfunction "O_4") (pintype "output"))
      (node (ref "E45") (pin "2") (pinfunction "O2_2") (pintype "input"))
    )
    (net (code "86") (name "Net-(E44C-O)") (class "Default")
      (node (ref "E44") (pin "6") (pinfunction "O_6") (pintype "output"))
      (node (ref "E45") (pin "11") (pinfunction "O1_11") (pintype "input"))
    )
    (net (code "87") (name "Net-(E44D-O)") (class "Default")
      (node (ref "E44") (pin "8") (pinfunction "O_8") (pintype "output"))
      (node (ref "E45") (pin "14") (pinfunction "O0_14") (pintype "input"))
    )
    (net (code "88") (name "Net-(E47B-I1)") (class "Default")
      (node (ref "E47") (pin "10") (pinfunction "O_10") (pintype "output"))
      (node (ref "E47") (pin "6") (pinfunction "I1_6") (pintype "input"))
    )
    (net (code "89") (name "Net-(E47D-O)") (class "Default")
      (node (ref "E47") (pin "13") (pinfunction "O_13") (pintype "output"))
      (node (ref "E85") (pin "9") (pinfunction "CLK_9") (pintype "input"))
    )
    (net (code "90") (name "Net-(E48C-I0)") (class "Default")
      (node (ref "E48") (pin "8") (pinfunction "I0_8") (pintype "input"))
      (node (ref "E68") (pin "6") (pinfunction "A=B_O_6") (pintype "output"))
    )
    (net (code "91") (name "Net-(E48C-I1)") (class "Default")
      (node (ref "E48") (pin "9") (pinfunction "I1_9") (pintype "input"))
      (node (ref "E68") (pin "5") (pinfunction "A>B_O_5") (pintype "output"))
    )
    (net (code "92") (name "Net-(E48D-O)") (class "Default")
      (node (ref "E48") (pin "13") (pinfunction "O_13") (pintype "output"))
      (node (ref "E96") (pin "1") (pinfunction "1G_1") (pintype "input"))
      (node (ref "E96") (pin "15") (pinfunction "2G_15") (pintype "input"))
    )
    (net (code "93") (name "Net-(E49A-I0)") (class "Default")
      (node (ref "E49") (pin "1") (pinfunction "I0_1") (pintype "input"))
      (node (ref "E57") (pin "8") (pinfunction "O_8") (pintype "output"))
      (node (ref "E58") (pin "3") (pinfunction "I_3") (pintype "input"))
    )
    (net (code "94") (name "Net-(E49A-O)") (class "Default")
      (node (ref "E49") (pin "12") (pinfunction "O_12") (pintype "output"))
      (node (ref "E58") (pin "13") (pinfunction "I_13") (pintype "input"))
      (node (ref "E69") (pin "14") (pinfunction "B3_14") (pintype "input"))
      (node (ref "E79") (pin "11") (pinfunction "B2_11") (pintype "input"))
      (node (ref "E79") (pin "14") (pinfunction "B3_14") (pintype "input"))
      (node (ref "E79") (pin "2") (pinfunction "B0_2") (pintype "input"))
      (node (ref "E79") (pin "5") (pinfunction "B1_5") (pintype "input"))
    )
    (net (code "95") (name "Net-(E49B-O)") (class "Default")
      (node (ref "E49") (pin "6") (pinfunction "O_6") (pintype "output"))
      (node (ref "E70") (pin "5") (pinfunction "I1_5") (pintype "input"))
    )
    (net (code "96") (name "Net-(E49C-I1)") (class "Default")
      (node (ref "E49") (pin "10") (pinfunction "I1_10") (pintype "input"))
      (node (ref "E70") (pin "8") (pinfunction "O_8") (pintype "output"))
    )
    (net (code "97") (name "Net-(E50A-I0)") (class "Default")
      (node (ref "E50") (pin "1") (pinfunction "I0_1") (pintype "input"))
      (node (ref "E59") (pin "6") (pinfunction "~{Q}_6") (pintype "output"))
      (node (ref "E8") (pin "8") (pinfunction "I0_8") (pintype "input"))
    )
    (net (code "98") (name "Net-(E50A-O)") (class "Default")
      (node (ref "E50") (pin "3") (pinfunction "O_3") (pintype "output"))
      (node (ref "E50") (pin "4") (pinfunction "I0_4") (pintype "input"))
    )
    (net (code "99") (name "Net-(E50B-I1)") (class "Default")
      (node (ref "E50") (pin "5") (pinfunction "I1_5") (pintype "input"))
      (node (ref "E50") (pin "8") (pinfunction "O_8") (pintype "output"))
    )
    (net (code "100") (name "Net-(E50B-O)") (class "Default")
      (node (ref "E50") (pin "6") (pinfunction "O_6") (pintype "output"))
      (node (ref "E60") (pin "2") (pinfunction "D_2") (pintype "input"))
    )
    (net (code "101") (name "Net-(E50D-O)") (class "Default")
      (node (ref "E50") (pin "11") (pinfunction "O_11") (pintype "output"))
      (node (ref "E60") (pin "4") (pinfunction "PRE_4") (pintype "input"))
    )
    (net (code "102") (name "Net-(E52A-O)") (class "Default")
      (node (ref "E52") (pin "3") (pinfunction "O_3") (pintype "output"))
      (node (ref "E62") (pin "11") (pinfunction "D4_11") (pintype "input"))
    )
    (net (code "103") (name "Net-(E52B-O)") (class "Default")
      (node (ref "E52") (pin "2") (pinfunction "O_2") (pintype "output"))
      (node (ref "E62") (pin "12") (pinfunction "D3_12") (pintype "input"))
    )
    (net (code "104") (name "Net-(E52C-O)") (class "Default")
      (node (ref "E52") (pin "14") (pinfunction "O_14") (pintype "output"))
      (node (ref "E62") (pin "13") (pinfunction "D2_13") (pintype "input"))
    )
    (net (code "105") (name "Net-(E54A-O)") (class "Default")
      (node (ref "E54") (pin "3") (pinfunction "O_3") (pintype "output"))
      (node (ref "E54") (pin "4") (pinfunction "I0_4") (pintype "input"))
    )
    (net (code "106") (name "Net-(E54B-O)") (class "Default")
      (node (ref "E54") (pin "6") (pinfunction "O_6") (pintype "output"))
      (node (ref "E56") (pin "10") (pinfunction "I1_10") (pintype "input"))
    )
    (net (code "107") (name "Net-(E54C-I1)") (class "Default")
      (node (ref "E54") (pin "10") (pinfunction "I1_10") (pintype "input"))
      (node (ref "E54") (pin "12") (pinfunction "I0_12") (pintype "input"))
      (node (ref "E56") (pin "8") (pinfunction "O_8") (pintype "output"))
    )
    (net (code "108") (name "Net-(E54D-O)") (class "Default")
      (node (ref "E54") (pin "11") (pinfunction "O_11") (pintype "output"))
      (node (ref "E56") (pin "9") (pinfunction "I0_9") (pintype "input"))
    )
    (net (code "109") (name "Net-(E56A-O)") (class "Default")
      (node (ref "E56") (pin "11") (pinfunction "I2_11") (pintype "input"))
      (node (ref "E56") (pin "12") (pinfunction "O_12") (pintype "output"))
    )
    (net (code "110") (name "Net-(E57A-I0)") (class "Default")
      (node (ref "E57") (pin "1") (pinfunction "I0_1") (pintype "input"))
      (node (ref "E69") (pin "3") (pinfunction "F0_3") (pintype "output"))
    )
    (net (code "111") (name "Net-(E57A-O)") (class "Default")
      (node (ref "E57") (pin "13") (pinfunction "I1_13") (pintype "input"))
      (node (ref "E57") (pin "3") (pinfunction "O_3") (pintype "output"))
    )
    (net (code "112") (name "Net-(E58D-O)") (class "Default")
      (node (ref "E58") (pin "8") (pinfunction "O_8") (pintype "output"))
      (node (ref "E66") (pin "2") (pinfunction "I1_2") (pintype "input"))
    )
    (net (code "113") (name "Net-(E59A-CLR)") (class "Default")
      (node (ref "E59") (pin "1") (pinfunction "CLR_1") (pintype "input"))
      (node (ref "E59") (pin "13") (pinfunction "CLR_13") (pintype "input"))
      (node (ref "E59") (pin "4") (pinfunction "PRE_4") (pintype "input"))
      (node (ref "R13") (pin "1") (pinfunction "1_1") (pintype "passive"))
    )
    (net (code "114") (name "Net-(E59B-D)") (class "Default")
      (node (ref "E59") (pin "12") (pinfunction "D_12") (pintype "input"))
      (node (ref "E60") (pin "6") (pinfunction "~{Q}_6") (pintype "output"))
    )
    (net (code "115") (name "Net-(E61A-O)") (class "Default")
      (node (ref "E61") (pin "3") (pinfunction "O_3") (pintype "output"))
      (node (ref "E61") (pin "6") (pinfunction "I0_6") (pintype "input"))
    )
    (net (code "116") (name "Net-(E63A-D)") (class "Default")
      (node (ref "E63") (pin "10") (pinfunction "PRE_10") (pintype "input"))
      (node (ref "E63") (pin "2") (pinfunction "D_2") (pintype "input"))
      (node (ref "R15") (pin "1") (pinfunction "1_1") (pintype "passive"))
    )
    (net (code "117") (name "Net-(E64A-O)") (class "Default")
      (node (ref "E64") (pin "1") (pinfunction "O_1") (pintype "output"))
      (node (ref "E64") (pin "6") (pinfunction "I1_6") (pintype "input"))
    )
    (net (code "118") (name "Net-(E64B-O)") (class "Default")
      (node (ref "C12") (pin "1") (pinfunction "1_1") (pintype "passive"))
      (node (ref "E64") (pin "4") (pinfunction "O_4") (pintype "output"))
      (node (ref "R5") (pin "1") (pinfunction "1_1") (pintype "passive"))
    )
    (net (code "119") (name "Net-(E66A-O)") (class "Default")
      (node (ref "E66") (pin "3") (pinfunction "O_3") (pintype "output"))
      (node (ref "E67") (pin "12") (pinfunction "I0_12") (pintype "input"))
    )
    (net (code "120") (name "Net-(E66B-O)") (class "Default")
      (node (ref "E66") (pin "6") (pinfunction "O_6") (pintype "output"))
      (node (ref "E76") (pin "4") (pinfunction "PRE_4") (pintype "input"))
      (node (ref "E77") (pin "2") (pinfunction "B_2") (pintype "input"))
    )
    (net (code "121") (name "Net-(E66D-I1)") (class "Default")
      (node (ref "E66") (pin "13") (pinfunction "I1_13") (pintype "input"))
      (node (ref "E75") (pin "2") (pinfunction "O_2") (pintype "output"))
    )
    (net (code "122") (name "Net-(E66D-O)") (class "Default")
      (node (ref "E66") (pin "11") (pinfunction "O_11") (pintype "output"))
      (node (ref "E67") (pin "13") (pinfunction "I1_13") (pintype "input"))
    )
    (net (code "123") (name "Net-(E67A-I0)") (class "Default")
      (node (ref "E67") (pin "1") (pinfunction "I0_1") (pintype "input"))
      (node (ref "E80") (pin "1") (pinfunction "O0_1") (pintype "tri_state"))
    )
    (net (code "124") (name "Net-(E67A-O)") (class "Default")
      (node (ref "E67") (pin "3") (pinfunction "O_3") (pintype "output"))
      (node (ref "E69") (pin "1") (pinfunction "A0_1") (pintype "input"))
    )
    (net (code "125") (name "Net-(E67C-O)") (class "Default")
      (node (ref "E67") (pin "8") (pinfunction "O_8") (pintype "output"))
      (node (ref "E69") (pin "9") (pinfunction "S0_9") (pintype "input"))
      (node (ref "E79") (pin "9") (pinfunction "S0_9") (pintype "input"))
    )
    (net (code "126") (name "Net-(E67D-O)") (class "Default")
      (node (ref "E67") (pin "11") (pinfunction "O_11") (pintype "output"))
      (node (ref "E76") (pin "12") (pinfunction "D_12") (pintype "input"))
    )
    (net (code "127") (name "Net-(E68A-A<B_I)") (class "Default")
      (node (ref "E68") (pin "2") (pinfunction "A<B_I_2") (pintype "input"))
      (node (ref "E78") (pin "7") (pinfunction "A<B_O_7") (pintype "output"))
    )
    (net (code "128") (name "Net-(E68A-A=B_I)") (class "Default")
      (node (ref "E68") (pin "3") (pinfunction "A=B_I_3") (pintype "input"))
      (node (ref "E78") (pin "6") (pinfunction "A=B_O_6") (pintype "output"))
    )
    (net (code "129") (name "Net-(E68A-A>B_I)") (class "Default")
      (node (ref "E68") (pin "4") (pinfunction "A>B_I_4") (pintype "input"))
      (node (ref "E78") (pin "5") (pinfunction "A>B_O_5") (pintype "output"))
    )
    (net (code "130") (name "Net-(E69A-A1)") (class "Default")
      (node (ref "E69") (pin "6") (pinfunction "A1_6") (pintype "input"))
      (node (ref "E80") (pin "2") (pinfunction "O1_2") (pintype "tri_state"))
    )
    (net (code "131") (name "Net-(E69A-A2)") (class "Default")
      (node (ref "E69") (pin "10") (pinfunction "A2_10") (pintype "input"))
      (node (ref "E80") (pin "3") (pinfunction "O2_3") (pintype "tri_state"))
    )
    (net (code "132") (name "Net-(E69A-A3)") (class "Default")
      (node (ref "E69") (pin "15") (pinfunction "A3_15") (pintype "input"))
      (node (ref "E80") (pin "4") (pinfunction "O3_4") (pintype "tri_state"))
    )
    (net (code "133") (name "Net-(E70A-O)") (class "Default")
      (node (ref "E70") (pin "3") (pinfunction "O_3") (pintype "output"))
      (node (ref "E70") (pin "4") (pinfunction "I0_4") (pintype "input"))
    )
    (net (code "134") (name "Net-(E70D-O)") (class "Default")
      (node (ref "E70") (pin "11") (pinfunction "O_11") (pintype "output"))
      (node (ref "E80") (pin "13") (pinfunction "A3_13") (pintype "input"))
    )
    (net (code "135") (name "Net-(E76B-CLR)") (class "Default")
      (node (ref "E76") (pin "13") (pinfunction "CLR_13") (pintype "input"))
      (node (ref "R19") (pin "1") (pinfunction "1_1") (pintype "passive"))
    )
    (net (code "136") (name "Net-(E77A-C)") (class "Default")
      (node (ref "C19") (pin "1") (pinfunction "1_1") (pintype "passive"))
      (node (ref "E77") (pin "14") (pinfunction "C_14") (pintype "input"))
    )
    (net (code "137") (name "Net-(E77A-R{slash}C)") (class "Default")
      (node (ref "C19") (pin "2") (pinfunction "2_2") (pintype "passive"))
      (node (ref "E77") (pin "15") (pinfunction "R/C_15") (pintype "input"))
      (node (ref "R20") (pin "2") (pinfunction "2_2") (pintype "passive"))
    )
    (net (code "138") (name "Net-(E79A-A0)") (class "Default")
      (node (ref "E79") (pin "1") (pinfunction "A0_1") (pintype "input"))
      (node (ref "E80") (pin "5") (pinfunction "O4_5") (pintype "tri_state"))
    )
    (net (code "139") (name "Net-(E79A-A1)") (class "Default")
      (node (ref "E79") (pin "6") (pinfunction "A1_6") (pintype "input"))
      (node (ref "E80") (pin "6") (pinfunction "O5_6") (pintype "tri_state"))
    )
    (net (code "140") (name "Net-(E79A-A2)") (class "Default")
      (node (ref "E79") (pin "10") (pinfunction "A2_10") (pintype "input"))
      (node (ref "E80") (pin "7") (pinfunction "O6_7") (pintype "tri_state"))
    )
    (net (code "141") (name "Net-(E79A-A3)") (class "Default")
      (node (ref "E79") (pin "15") (pinfunction "A3_15") (pintype "input"))
      (node (ref "E80") (pin "9") (pinfunction "O7_9") (pintype "tri_state"))
    )
    (net (code "142") (name "Net-(E81A-O2)") (class "Default")
      (node (ref "E81") (pin "16") (pinfunction "O2_16") (pintype "tri_state"))
      (node (ref "E82") (pin "6") (pinfunction "D1_6") (pintype "input"))
    )
    (net (code "143") (name "Net-(E81A-O3)") (class "Default")
      (node (ref "E81") (pin "15") (pinfunction "O3_15") (pintype "tri_state"))
      (node (ref "E82") (pin "4") (pinfunction "D0_4") (pintype "input"))
    )
    (net (code "144") (name "Net-(E81A-O4)") (class "Default")
      (node (ref "E81") (pin "13") (pinfunction "O4_13") (pintype "tri_state"))
      (node (ref "E82") (pin "1") (pinfunction "A0_1") (pintype "input"))
      (node (ref "E90") (pin "11") (pinfunction "D4_11") (pintype "input"))
    )
    (net (code "145") (name "Net-(E81A-O5)") (class "Default")
      (node (ref "E81") (pin "12") (pinfunction "O5_12") (pintype "tri_state"))
      (node (ref "E82") (pin "13") (pinfunction "A3_13") (pintype "input"))
      (node (ref "E90") (pin "12") (pinfunction "D3_12") (pintype "input"))
    )
    (net (code "146") (name "Net-(E81A-O6)") (class "Default")
      (node (ref "E81") (pin "11") (pinfunction "O6_11") (pintype "tri_state"))
      (node (ref "E82") (pin "14") (pinfunction "A2_14") (pintype "input"))
      (node (ref "E90") (pin "13") (pinfunction "D2_13") (pintype "input"))
    )
    (net (code "147") (name "Net-(E81A-O7)") (class "Default")
      (node (ref "E81") (pin "10") (pinfunction "O7_10") (pintype "tri_state"))
      (node (ref "E82") (pin "15") (pinfunction "A1_15") (pintype "input"))
      (node (ref "E90") (pin "14") (pinfunction "D1_14") (pintype "input"))
    )
    (net (code "148") (name "Net-(E83C-~{G})") (class "Default")
      (node (ref "E83") (pin "15") (pinfunction "~{G}_15") (pintype "input"))
      (node (ref "E92") (pin "8") (pinfunction "O_8") (pintype "output"))
    )
    (net (code "149") (name "Net-(E84A-1G)") (class "Default")
      (node (ref "E84") (pin "1") (pinfunction "1G_1") (pintype "input"))
      (node (ref "E92") (pin "12") (pinfunction "O_12") (pintype "output"))
    )
    (net (code "150") (name "Net-(E100A-2A1)") (class "Default")
      (node (ref "E100") (pin "12") (pinfunction "2A1_12") (pintype "input"))
      (node (ref "E101") (pin "11") (pinfunction "Y1_11") (pintype "tri_state"))
      (node (ref "E120") (pin "3") (pinfunction "B_3") (pintype "input"))
      (node (ref "E82") (pin "5") (pinfunction "Q0_5") (pintype "output"))
      (node (ref "E91") (pin "11") (pinfunction "2Y1_11") (pintype "tri_state"))
      (node (ref "R23") (pin "1") (pinfunction "1_1") (pintype "passive"))
    )
    (net (code "151") (name "Net-(E100A-2A2)") (class "Default")
      (node (ref "E100") (pin "14") (pinfunction "2A2_14") (pintype "input"))
      (node (ref "E101") (pin "13") (pinfunction "Y2_13") (pintype "tri_state"))
      (node (ref "E120") (pin "2") (pinfunction "A_2") (pintype "input"))
      (node (ref "E82") (pin "7") (pinfunction "Q1_7") (pintype "output"))
      (node (ref "E91") (pin "13") (pinfunction "2Y2_13") (pintype "tri_state"))
      (node (ref "R22") (pin "1") (pinfunction "1_1") (pintype "passive"))
    )
    (net (code "152") (name "Net-(E101C-A1)") (class "Default")
      (node (ref "E101") (pin "12") (pinfunction "A1_12") (pintype "input"))
      (node (ref "E110") (pin "14") (pinfunction "~{Q4}_14") (pintype "output"))
      (node (ref "E91") (pin "2") (pinfunction "1A1_2") (pintype "input"))
    )
    (net (code "153") (name "Net-(E101C-A2)") (class "Default")
      (node (ref "E101") (pin "14") (pinfunction "A2_14") (pintype "input"))
      (node (ref "E110") (pin "11") (pinfunction "~{Q3}_11") (pintype "output"))
      (node (ref "E91") (pin "4") (pinfunction "1A2_4") (pintype "input"))
    )
    (net (code "154") (name "Net-(E102A-D2)") (class "Default")
      (node (ref "E102") (pin "5") (pinfunction "D2_5") (pintype "input"))
      (node (ref "E104") (pin "7") (pinfunction "1Y3_7") (pintype "tri_state"))
      (node (ref "E107") (pin "13") (pinfunction "2Y2_13") (pintype "tri_state"))
      (node (ref "E73") (pin "11") (pinfunction "D4_11") (pintype "input"))
      (node (ref "E84") (pin "3") (pinfunction "1Y1_3") (pintype "tri_state"))
      (node (ref "E95") (pin "13") (pinfunction "2Y2_13") (pintype "tri_state"))
      (node (ref "E96") (pin "13") (pinfunction "2Y2_13") (pintype "tri_state"))
      (node (ref "R28") (pin "1") (pinfunction "1_1") (pintype "passive"))
    )
    (net (code "155") (name "Net-(E102A-D3)") (class "Default")
      (node (ref "E102") (pin "12") (pinfunction "D3_12") (pintype "input"))
      (node (ref "E104") (pin "5") (pinfunction "1Y2_5") (pintype "tri_state"))
      (node (ref "E107") (pin "11") (pinfunction "2Y1_11") (pintype "tri_state"))
      (node (ref "E73") (pin "12") (pinfunction "D3_12") (pintype "input"))
      (node (ref "E84") (pin "5") (pinfunction "1Y2_5") (pintype "tri_state"))
      (node (ref "E95") (pin "11") (pinfunction "2Y1_11") (pintype "tri_state"))
      (node (ref "E96") (pin "11") (pinfunction "2Y1_11") (pintype "tri_state"))
      (node (ref "R32") (pin "1") (pinfunction "1_1") (pintype "passive"))
    )
    (net (code "156") (name "Net-(E102A-D4)") (class "Default")
      (node (ref "E102") (pin "13") (pinfunction "D4_13") (pintype "input"))
      (node (ref "E104") (pin "3") (pinfunction "1Y1_3") (pintype "tri_state"))
      (node (ref "E107") (pin "9") (pinfunction "1Y4_9") (pintype "tri_state"))
      (node (ref "E73") (pin "13") (pinfunction "D2_13") (pintype "input"))
      (node (ref "E84") (pin "7") (pinfunction "1Y3_7") (pintype "tri_state"))
      (node (ref "E95") (pin "9") (pinfunction "1Y4_9") (pintype "tri_state"))
      (node (ref "E96") (pin "9") (pinfunction "1Y4_9") (pintype "tri_state"))
      (node (ref "R33") (pin "1") (pinfunction "1_1") (pintype "passive"))
    )
    (net (code "157") (name "Net-(E104A-1G)") (class "Default")
      (node (ref "E104") (pin "1") (pinfunction "1G_1") (pintype "input"))
      (node (ref "E94") (pin "6") (pinfunction "O_6") (pintype "output"))
    )
    (net (code "158") (name "Net-(E105A-1G)") (class "Default")
      (node (ref "E105") (pin "1") (pinfunction "1G_1") (pintype "input"))
      (node (ref "E105") (pin "15") (pinfunction "2G_15") (pintype "input"))
      (node (ref "E115") (pin "8") (pinfunction "O_8") (pintype "output"))
    )
    (net (code "159") (name "Net-(E107A-1Y1)") (class "Default")
      (node (ref "E107") (pin "3") (pinfunction "1Y1_3") (pintype "tri_state"))
      (node (ref "E93") (pin "13") (pinfunction "D4_13") (pintype "input"))
      (node (ref "E95") (pin "3") (pinfunction "1Y1_3") (pintype "tri_state"))
      (node (ref "E96") (pin "3") (pinfunction "1Y1_3") (pintype "tri_state"))
      (node (ref "E97") (pin "11") (pinfunction "D4_11") (pintype "input"))
      (node (ref "E97") (pin "6") (pinfunction "Q4_6") (pintype "tri_state"))
      (node (ref "R35") (pin "1") (pinfunction "1_1") (pintype "passive"))
    )
    (net (code "160") (name "Net-(E107A-1Y2)") (class "Default")
      (node (ref "E107") (pin "5") (pinfunction "1Y2_5") (pintype "tri_state"))
      (node (ref "E93") (pin "12") (pinfunction "D3_12") (pintype "input"))
      (node (ref "E95") (pin "5") (pinfunction "1Y2_5") (pintype "tri_state"))
      (node (ref "E96") (pin "5") (pinfunction "1Y2_5") (pintype "tri_state"))
      (node (ref "E97") (pin "12") (pinfunction "D3_12") (pintype "input"))
      (node (ref "E97") (pin "5") (pinfunction "Q3_5") (pintype "tri_state"))
      (node (ref "R34") (pin "1") (pinfunction "1_1") (pintype "passive"))
    )
    (net (code "161") (name "Net-(E107A-1Y3)") (class "Default")
      (node (ref "E107") (pin "7") (pinfunction "1Y3_7") (pintype "tri_state"))
      (node (ref "E93") (pin "5") (pinfunction "D2_5") (pintype "input"))
      (node (ref "E95") (pin "7") (pinfunction "1Y3_7") (pintype "tri_state"))
      (node (ref "E96") (pin "7") (pinfunction "1Y3_7") (pintype "tri_state"))
      (node (ref "E97") (pin "13") (pinfunction "D2_13") (pintype "input"))
      (node (ref "E97") (pin "4") (pinfunction "Q2_4") (pintype "tri_state"))
      (node (ref "R29") (pin "1") (pinfunction "1_1") (pintype "passive"))
    )
    (net (code "162") (name "Net-(E108A-CLR)") (class "Default")
      (node (ref "E108") (pin "1") (pinfunction "CLR_1") (pintype "input"))
      (node (ref "E110") (pin "1") (pinfunction "CLR_1") (pintype "input"))
      (node (ref "E116") (pin "1") (pinfunction "CLR_1") (pintype "input"))
      (node (ref "E117") (pin "1") (pinfunction "CLR_1") (pintype "input"))
      (node (ref "R36") (pin "1") (pinfunction "1_1") (pintype "passive"))
    )
    (net (code "163") (name "Net-(E108A-D3)") (class "Default")
      (node (ref "E108") (pin "12") (pinfunction "D3_12") (pintype "input"))
      (node (ref "E109") (pin "13") (pinfunction "O4_13") (pintype "tri_state"))
    )
    (net (code "164") (name "Net-(E108A-D4)") (class "Default")
      (node (ref "E108") (pin "13") (pinfunction "D4_13") (pintype "input"))
      (node (ref "E109") (pin "12") (pinfunction "O5_12") (pintype "tri_state"))
    )
    (net (code "165") (name "Net-(E108A-Q3)") (class "Default")
      (node (ref "E108") (pin "10") (pinfunction "Q3_10") (pintype "output"))
      (node (ref "E111") (pin "5") (pinfunction "A0_5") (pintype "input"))
      (node (ref "E117") (pin "4") (pinfunction "D1_4") (pintype "input"))
    )
    (net (code "166") (name "Net-(E108A-Q4)") (class "Default")
      (node (ref "E108") (pin "15") (pinfunction "Q4_15") (pintype "output"))
      (node (ref "E111") (pin "4") (pinfunction "A3_4") (pintype "input"))
      (node (ref "E117") (pin "5") (pinfunction "D2_5") (pintype "input"))
    )
    (net (code "167") (name "Net-(E108A-~{Q3})") (class "Default")
      (node (ref "E108") (pin "11") (pinfunction "~{Q3}_11") (pintype "output"))
      (node (ref "E91") (pin "10") (pinfunction "1A4_10") (pintype "input"))
      (node (ref "E91") (pin "14") (pinfunction "2A2_14") (pintype "input"))
    )
    (net (code "168") (name "Net-(E108A-~{Q4})") (class "Default")
      (node (ref "E108") (pin "14") (pinfunction "~{Q4}_14") (pintype "output"))
      (node (ref "E91") (pin "12") (pinfunction "2A1_12") (pintype "input"))
      (node (ref "E91") (pin "6") (pinfunction "1A3_6") (pintype "input"))
    )
    (net (code "169") (name "Net-(E109A-O2)") (class "Default")
      (node (ref "E109") (pin "16") (pinfunction "O2_16") (pintype "tri_state"))
      (node (ref "E116") (pin "12") (pinfunction "D3_12") (pintype "input"))
    )
    (net (code "170") (name "Net-(E109A-O3)") (class "Default")
      (node (ref "E109") (pin "15") (pinfunction "O3_15") (pintype "tri_state"))
      (node (ref "E116") (pin "13") (pinfunction "D4_13") (pintype "input"))
    )
    (net (code "171") (name "Net-(E109A-O6)") (class "Default")
      (node (ref "E109") (pin "11") (pinfunction "O6_11") (pintype "tri_state"))
      (node (ref "E110") (pin "12") (pinfunction "D3_12") (pintype "input"))
    )
    (net (code "172") (name "Net-(E109A-O7)") (class "Default")
      (node (ref "E109") (pin "10") (pinfunction "O7_10") (pintype "tri_state"))
      (node (ref "E110") (pin "13") (pinfunction "D4_13") (pintype "input"))
    )
    (net (code "173") (name "Net-(E110A-Q3)") (class "Default")
      (node (ref "E110") (pin "10") (pinfunction "Q3_10") (pintype "output"))
      (node (ref "E111") (pin "6") (pinfunction "A1_6") (pintype "input"))
      (node (ref "E117") (pin "12") (pinfunction "D3_12") (pintype "input"))
    )
    (net (code "174") (name "Net-(E110A-Q4)") (class "Default")
      (node (ref "E110") (pin "15") (pinfunction "Q4_15") (pintype "output"))
      (node (ref "E111") (pin "3") (pinfunction "A4_3") (pintype "input"))
      (node (ref "E117") (pin "13") (pinfunction "D4_13") (pintype "input"))
    )
    (net (code "175") (name "Net-(E112A-O2)") (class "Default")
      (node (ref "E112") (pin "10") (pinfunction "O2_10") (pintype "tri_state"))
      (node (ref "E114") (pin "1") (pinfunction "A6_1") (pintype "input"))
    )
    (net (code "176") (name "Net-(E113A-A6)") (class "Default")
      (node (ref "E113") (pin "1") (pinfunction "A6_1") (pintype "input"))
      (node (ref "E87") (pin "9") (pinfunction "O3_9") (pintype "tri_state"))
    )
    (net (code "177") (name "Net-(E115A-O)") (class "Default")
      (node (ref "E115") (pin "2") (pinfunction "O_2") (pintype "output"))
      (node (ref "E97") (pin "2") (pinfunction "N_2") (pintype "input"))
    )
    (net (code "178") (name "Net-(E115C-I)") (class "Default")
      (node (ref "E115") (pin "5") (pinfunction "I_5") (pintype "input"))
      (node (ref "E72") (pin "3") (pinfunction "O_3") (pintype "output"))
      (node (ref "E92") (pin "9") (pinfunction "I0_9") (pintype "input"))
    )
    (net (code "179") (name "Net-(E115C-O)") (class "Default")
      (node (ref "E115") (pin "6") (pinfunction "O_6") (pintype "output"))
      (node (ref "E92") (pin "3") (pinfunction "I0_3") (pintype "input"))
    )
    (net (code "180") (name "Net-(E115E-O)") (class "Default")
      (node (ref "E115") (pin "10") (pinfunction "O_10") (pintype "output"))
      (node (ref "E89") (pin "3") (pinfunction "6_3") (pintype "input"))
    )
    (net (code "181") (name "Net-(E120B-Y0)") (class "Default")
      (node (ref "E120") (pin "12") (pinfunction "Y0_12") (pintype "output"))
      (node (ref "E121") (pin "11") (pinfunction "D4_11") (pintype "input"))
      (node (ref "E122") (pin "11") (pinfunction "D4_11") (pintype "input"))
    )
    (net (code "182") (name "Net-(E120B-Y1)") (class "Default")
      (node (ref "E120") (pin "11") (pinfunction "Y1_11") (pintype "output"))
      (node (ref "E121") (pin "12") (pinfunction "D3_12") (pintype "input"))
      (node (ref "E122") (pin "12") (pinfunction "D3_12") (pintype "input"))
    )
    (net (code "183") (name "Net-(E120B-Y2)") (class "Default")
      (node (ref "E120") (pin "10") (pinfunction "Y2_10") (pintype "output"))
      (node (ref "E121") (pin "13") (pinfunction "D2_13") (pintype "input"))
      (node (ref "E122") (pin "13") (pinfunction "D2_13") (pintype "input"))
    )
    (net (code "184") (name "Net-(E120B-Y3)") (class "Default")
      (node (ref "E120") (pin "9") (pinfunction "Y3_9") (pintype "output"))
      (node (ref "E121") (pin "14") (pinfunction "D1_14") (pintype "input"))
      (node (ref "E122") (pin "14") (pinfunction "D1_14") (pintype "input"))
    )
    (net (code "185") (name "Net-(Q1-B)") (class "Default")
      (node (ref "C12") (pin "2") (pinfunction "2_2") (pintype "passive"))
      (node (ref "D1") (pin "A") (pinfunction "A_A") (pintype "passive"))
      (node (ref "Q1") (pin "2") (pinfunction "B_2") (pintype "passive"))
      (node (ref "R5") (pin "2") (pinfunction "2_2") (pintype "passive"))
    )
    (net (code "186") (name "P1_3V") (class "Default")
      (node (ref "E114") (pin "2") (pinfunction "A5_2") (pintype "input"))
      (node (ref "E114") (pin "3") (pinfunction "A4_3") (pintype "input"))
      (node (ref "E114") (pin "4") (pinfunction "A3_4") (pintype "input"))
      (node (ref "E78") (pin "3") (pinfunction "A=B_I_3") (pintype "input"))
      (node (ref "R21") (pin "1") (pinfunction "1_1") (pintype "passive"))
    )
    (net (code "187") (name "P1_BB0") (class "Default")
      (node (ref "E109") (pin "3") (pinfunction "I6_3") (pintype "input"))
      (node (ref "E113") (pin "11") (pinfunction "O1_11") (pintype "tri_state"))
    )
    (net (code "188") (name "P1_BB1") (class "Default")
      (node (ref "E109") (pin "4") (pinfunction "I5_4") (pintype "input"))
      (node (ref "E113") (pin "12") (pinfunction "O0_12") (pintype "tri_state"))
    )
    (net (code "189") (name "P1_BFL0") (class "Default")
      (node (ref "E87") (pin "10") (pinfunction "O2_10") (pintype "tri_state"))
      (node (ref "E95") (pin "10") (pinfunction "1A4_10") (pintype "input"))
      (node (ref "E95") (pin "2") (pinfunction "1A1_2") (pintype "input"))
    )
    (net (code "190") (name "P1_BFL1") (class "Default")
      (node (ref "E87") (pin "11") (pinfunction "O1_11") (pintype "tri_state"))
      (node (ref "E95") (pin "12") (pinfunction "2A1_12") (pintype "input"))
      (node (ref "E95") (pin "4") (pinfunction "1A2_4") (pintype "input"))
    )
    (net (code "191") (name "P1_BFL2") (class "Default")
      (node (ref "E87") (pin "12") (pinfunction "O0_12") (pintype "tri_state"))
      (node (ref "E95") (pin "14") (pinfunction "2A2_14") (pintype "input"))
      (node (ref "E95") (pin "6") (pinfunction "1A3_6") (pintype "input"))
    )
    (net (code "192") (name "P1_CRF") (class "Default")
      (node (ref "E111") (pin "1") (pinfunction "A6_1") (pintype "input"))
      (node (ref "E114") (pin "10") (pinfunction "O2_10") (pintype "tri_state"))
    )
    (net (code "193") (name "P1_OVER") (class "Default")
      (node (ref "E39") (pin "12") (pinfunction "O_12") (pintype "output"))
      (node (ref "E49") (pin "11") (pinfunction "I2_11") (pintype "input"))
    )
    (net (code "194") (name "P1_RR0") (class "Default")
      (node (ref "E111") (pin "2") (pinfunction "A5_2") (pintype "input"))
      (node (ref "E113") (pin "3") (pinfunction "A4_3") (pintype "input"))
      (node (ref "E85") (pin "15") (pinfunction "Q6_15") (pintype "output"))
      (node (ref "E86") (pin "2") (pinfunction "1A1_2") (pintype "input"))
    )
    (net (code "195") (name "P1_RR1") (class "Default")
      (node (ref "E111") (pin "7") (pinfunction "A2_7") (pintype "input"))
      (node (ref "E113") (pin "4") (pinfunction "A3_4") (pintype "input"))
      (node (ref "E85") (pin "2") (pinfunction "Q1_2") (pintype "output"))
      (node (ref "E86") (pin "4") (pinfunction "1A2_4") (pintype "input"))
    )
    (net (code "196") (name "P1_RR2") (class "Default")
      (node (ref "E114") (pin "7") (pinfunction "A2_7") (pintype "input"))
      (node (ref "E85") (pin "12") (pinfunction "Q5_12") (pintype "output"))
      (node (ref "E86") (pin "6") (pinfunction "1A3_6") (pintype "input"))
      (node (ref "E87") (pin "2") (pinfunction "A5_2") (pintype "input"))
    )
    (net (code "197") (name "P1_RR3") (class "Default")
      (node (ref "E112") (pin "2") (pinfunction "A5_2") (pintype "input"))
      (node (ref "E85") (pin "7") (pinfunction "Q3_7") (pintype "output"))
      (node (ref "E86") (pin "10") (pinfunction "1A4_10") (pintype "input"))
      (node (ref "E87") (pin "3") (pinfunction "A4_3") (pintype "input"))
    )
    (net (code "198") (name "P1_RR4") (class "Default")
      (node (ref "E112") (pin "7") (pinfunction "A2_7") (pintype "input"))
      (node (ref "E85") (pin "10") (pinfunction "Q4_10") (pintype "output"))
      (node (ref "E86") (pin "12") (pinfunction "2A1_12") (pintype "input"))
      (node (ref "E87") (pin "4") (pinfunction "A3_4") (pintype "input"))
    )
    (net (code "199") (name "P1_US0") (class "Default")
      (node (ref "E106") (pin "2") (pinfunction "1A1_2") (pintype "input"))
      (node (ref "E68") (pin "11") (pinfunction "B1_11") (pintype "input"))
      (node (ref "E88") (pin "15") (pinfunction "Q6_15") (pintype "output"))
    )
    (net (code "200") (name "P1_US1") (class "Default")
      (node (ref "E106") (pin "4") (pinfunction "1A2_4") (pintype "input"))
      (node (ref "E68") (pin "9") (pinfunction "B0_9") (pintype "input"))
      (node (ref "E88") (pin "2") (pinfunction "Q1_2") (pintype "output"))
    )
    (net (code "201") (name "P1_US2") (class "Default")
      (node (ref "E106") (pin "6") (pinfunction "1A3_6") (pintype "input"))
      (node (ref "E78") (pin "1") (pinfunction "B3_1") (pintype "input"))
      (node (ref "E88") (pin "5") (pinfunction "Q2_5") (pintype "output"))
    )
    (net (code "202") (name "P1_US3") (class "Default")
      (node (ref "E106") (pin "10") (pinfunction "1A4_10") (pintype "input"))
      (node (ref "E78") (pin "14") (pinfunction "B2_14") (pintype "input"))
      (node (ref "E88") (pin "12") (pinfunction "Q5_12") (pintype "output"))
    )
    (net (code "203") (name "P1_US4") (class "Default")
      (node (ref "E106") (pin "12") (pinfunction "2A1_12") (pintype "input"))
      (node (ref "E78") (pin "11") (pinfunction "B1_11") (pintype "input"))
      (node (ref "E88") (pin "7") (pinfunction "Q3_7") (pintype "output"))
    )
    (net (code "204") (name "P1_US5") (class "Default")
      (node (ref "E106") (pin "14") (pinfunction "2A2_14") (pintype "input"))
      (node (ref "E78") (pin "9") (pinfunction "B0_9") (pintype "input"))
      (node (ref "E88") (pin "10") (pinfunction "Q4_10") (pintype "output"))
    )
    (net (code "205") (name "P2_3V") (class "Default")
      (node (ref "E102") (pin "1") (pinfunction "CLR_1") (pintype "input"))
      (node (ref "E103") (pin "1") (pinfunction "CLR_1") (pintype "input"))
      (node (ref "E93") (pin "1") (pinfunction "CLR_1") (pintype "input"))
      (node (ref "R30") (pin "1") (pinfunction "1_1") (pintype "passive"))
    )
    (net (code "206") (name "P2_DFA") (class "Default")
      (node (ref "E102") (pin "6") (pinfunction "~{Q2}_6") (pintype "output"))
      (node (ref "E112") (pin "5") (pinfunction "A0_5") (pintype "input"))
    )
    (net (code "207") (name "P2_DFB") (class "Default")
      (node (ref "E102") (pin "11") (pinfunction "~{Q3}_11") (pintype "output"))
      (node (ref "E112") (pin "4") (pinfunction "A3_4") (pintype "input"))
    )
    (net (code "208") (name "P2_DFC") (class "Default")
      (node (ref "E102") (pin "14") (pinfunction "~{Q4}_14") (pintype "output"))
      (node (ref "E114") (pin "5") (pinfunction "A0_5") (pintype "input"))
    )
    (net (code "209") (name "P2_EMAEN") (class "Default")
      (node (ref "E63") (pin "9") (pinfunction "Q_9") (pintype "output"))
      (node (ref "E64") (pin "9") (pinfunction "I1_9") (pintype "input"))
    )
    (net (code "210") (name "P2_IFA") (class "Default")
      (node (ref "E112") (pin "6") (pinfunction "A1_6") (pintype "input"))
      (node (ref "E93") (pin "6") (pinfunction "~{Q2}_6") (pintype "output"))
    )
    (net (code "211") (name "P2_IFB") (class "Default")
      (node (ref "E112") (pin "3") (pinfunction "A4_3") (pintype "input"))
      (node (ref "E93") (pin "11") (pinfunction "~{Q3}_11") (pintype "output"))
    )
    (net (code "212") (name "P2_IFC") (class "Default")
      (node (ref "E114") (pin "6") (pinfunction "A1_6") (pintype "input"))
      (node (ref "E93") (pin "14") (pinfunction "~{Q4}_14") (pintype "output"))
    )
    (net (code "213") (name "P2_SF0") (class "Default")
      (node (ref "E103") (pin "2") (pinfunction "Q1_2") (pintype "output"))
      (node (ref "E105") (pin "14") (pinfunction "2A2_14") (pintype "input"))
      (node (ref "E107") (pin "2") (pinfunction "1A1_2") (pintype "input"))
    )
    (net (code "214") (name "P2_SF1") (class "Default")
      (node (ref "E103") (pin "5") (pinfunction "Q2_5") (pintype "output"))
      (node (ref "E105") (pin "12") (pinfunction "2A1_12") (pintype "input"))
      (node (ref "E107") (pin "4") (pinfunction "1A2_4") (pintype "input"))
    )
    (net (code "215") (name "P2_SF2") (class "Default")
      (node (ref "E103") (pin "7") (pinfunction "Q3_7") (pintype "output"))
      (node (ref "E105") (pin "10") (pinfunction "1A4_10") (pintype "input"))
      (node (ref "E107") (pin "6") (pinfunction "1A3_6") (pintype "input"))
    )
    (net (code "216") (name "P2_SF3") (class "Default")
      (node (ref "E103") (pin "10") (pinfunction "Q4_10") (pintype "output"))
      (node (ref "E105") (pin "6") (pinfunction "1A3_6") (pintype "input"))
      (node (ref "E107") (pin "10") (pinfunction "1A4_10") (pintype "input"))
    )
    (net (code "217") (name "P2_SF4") (class "Default")
      (node (ref "E103") (pin "12") (pinfunction "Q5_12") (pintype "output"))
      (node (ref "E105") (pin "4") (pinfunction "1A2_4") (pintype "input"))
      (node (ref "E107") (pin "12") (pinfunction "2A1_12") (pintype "input"))
    )
    (net (code "218") (name "P2_SF5") (class "Default")
      (node (ref "E103") (pin "15") (pinfunction "Q6_15") (pintype "output"))
      (node (ref "E105") (pin "2") (pinfunction "1A1_2") (pintype "input"))
      (node (ref "E107") (pin "14") (pinfunction "2A2_14") (pintype "input"))
    )
    (net (code "219") (name "P2_SUF_OUT") (class "Default")
      (node (ref "E115") (pin "9") (pinfunction "I_9") (pintype "input"))
      (node (ref "E38") (pin "13") (pinfunction "I1_13") (pintype "input"))
      (node (ref "E56") (pin "6") (pinfunction "O_6") (pintype "output"))
      (node (ref "E8") (pin "9") (pinfunction "I1_9") (pintype "input"))
    )
    (net (code "220") (name "P3_BD") (class "Default")
      (node (ref "E61") (pin "14") (pinfunction "O_14") (pintype "output"))
      (node (ref "E66") (pin "1") (pinfunction "I0_1") (pintype "input"))
      (node (ref "E70") (pin "2") (pinfunction "I1_2") (pintype "input"))
    )
    (net (code "221") (name "P3_BD0") (class "Default")
      (node (ref "E12") (pin "6") (pinfunction "I3_6") (pintype "output"))
      (node (ref "E17") (pin "3") (pinfunction "D1_3") (pintype "input"))
      (node (ref "E35") (pin "13") (pinfunction "D4_13") (pintype "input"))
      (node (ref "E81") (pin "24") (pinfunction "I11_24") (pintype "input"))
    )
    (net (code "222") (name "P3_BD1") (class "Default")
      (node (ref "E109") (pin "5") (pinfunction "I4_5") (pintype "input"))
      (node (ref "E12") (pin "3") (pinfunction "I2_3") (pintype "output"))
      (node (ref "E120") (pin "14") (pinfunction "A_14") (pintype "input"))
      (node (ref "E17") (pin "4") (pinfunction "D2_4") (pintype "input"))
      (node (ref "E35") (pin "12") (pinfunction "D3_12") (pintype "input"))
      (node (ref "E81") (pin "25") (pinfunction "I10_25") (pintype "input"))
    )
    (net (code "223") (name "P3_BD2") (class "Default")
      (node (ref "E109") (pin "6") (pinfunction "I3_6") (pintype "input"))
      (node (ref "E12") (pin "10") (pinfunction "I1_10") (pintype "output"))
      (node (ref "E120") (pin "13") (pinfunction "B_13") (pintype "input"))
      (node (ref "E17") (pin "6") (pinfunction "D3_6") (pintype "input"))
      (node (ref "E35") (pin "5") (pinfunction "D2_5") (pintype "input"))
      (node (ref "E81") (pin "26") (pinfunction "I9_26") (pintype "input"))
    )
    (net (code "224") (name "P3_BD3") (class "Default")
      (node (ref "E109") (pin "7") (pinfunction "I2_7") (pintype "input"))
      (node (ref "E12") (pin "13") (pinfunction "I0_13") (pintype "output"))
      (node (ref "E17") (pin "11") (pinfunction "D4_11") (pintype "input"))
      (node (ref "E35") (pin "4") (pinfunction "D1_4") (pintype "input"))
      (node (ref "E81") (pin "27") (pinfunction "I8_27") (pintype "input"))
    )
    (net (code "225") (name "P3_BD4") (class "Default")
      (node (ref "E109") (pin "8") (pinfunction "I1_8") (pintype "input"))
      (node (ref "E13") (pin "6") (pinfunction "I3_6") (pintype "output"))
      (node (ref "E17") (pin "13") (pinfunction "D5_13") (pintype "input"))
      (node (ref "E46") (pin "13") (pinfunction "D4_13") (pintype "input"))
      (node (ref "E81") (pin "2") (pinfunction "I7_2") (pintype "input"))
    )
    (net (code "226") (name "P3_BD5") (class "Default")
      (node (ref "E109") (pin "9") (pinfunction "I0_9") (pintype "input"))
      (node (ref "E13") (pin "3") (pinfunction "I2_3") (pintype "output"))
      (node (ref "E17") (pin "14") (pinfunction "D6_14") (pintype "input"))
      (node (ref "E46") (pin "12") (pinfunction "D3_12") (pintype "input"))
      (node (ref "E50") (pin "10") (pinfunction "I1_10") (pintype "input"))
      (node (ref "E81") (pin "3") (pinfunction "I6_3") (pintype "input"))
    )
    (net (code "227") (name "P3_BD6") (class "Default")
      (node (ref "E13") (pin "10") (pinfunction "I1_10") (pintype "output"))
      (node (ref "E15") (pin "3") (pinfunction "D1_3") (pintype "input"))
      (node (ref "E2") (pin "1") (pinfunction "I_1") (pintype "input"))
      (node (ref "E46") (pin "5") (pinfunction "D2_5") (pintype "input"))
      (node (ref "E81") (pin "4") (pinfunction "I5_4") (pintype "input"))
      (node (ref "E88") (pin "14") (pinfunction "D6_14") (pintype "input"))
      (node (ref "E96") (pin "2") (pinfunction "1A1_2") (pintype "input"))
    )
    (net (code "228") (name "P3_BD7") (class "Default")
      (node (ref "E13") (pin "13") (pinfunction "I0_13") (pintype "output"))
      (node (ref "E15") (pin "4") (pinfunction "D2_4") (pintype "input"))
      (node (ref "E2") (pin "3") (pinfunction "I_3") (pintype "input"))
      (node (ref "E81") (pin "5") (pinfunction "I4_5") (pintype "input"))
      (node (ref "E85") (pin "14") (pinfunction "D6_14") (pintype "input"))
      (node (ref "E88") (pin "3") (pinfunction "D1_3") (pintype "input"))
      (node (ref "E96") (pin "4") (pinfunction "1A2_4") (pintype "input"))
    )
    (net (code "229") (name "P3_BD8") (class "Default")
      (node (ref "E15") (pin "6") (pinfunction "D3_6") (pintype "input"))
      (node (ref "E2") (pin "5") (pinfunction "I_5") (pintype "input"))
      (node (ref "E45") (pin "6") (pinfunction "I3_6") (pintype "output"))
      (node (ref "E81") (pin "6") (pinfunction "I3_6") (pintype "input"))
      (node (ref "E85") (pin "3") (pinfunction "D1_3") (pintype "input"))
      (node (ref "E88") (pin "4") (pinfunction "D2_4") (pintype "input"))
      (node (ref "E96") (pin "6") (pinfunction "1A3_6") (pintype "input"))
    )
    (net (code "230") (name "P3_BD9") (class "Default")
      (node (ref "E15") (pin "11") (pinfunction "D4_11") (pintype "input"))
      (node (ref "E45") (pin "3") (pinfunction "I2_3") (pintype "output"))
      (node (ref "E81") (pin "7") (pinfunction "I2_7") (pintype "input"))
      (node (ref "E85") (pin "13") (pinfunction "D5_13") (pintype "input"))
      (node (ref "E88") (pin "13") (pinfunction "D5_13") (pintype "input"))
      (node (ref "E96") (pin "10") (pinfunction "1A4_10") (pintype "input"))
    )
    (net (code "231") (name "P3_BD10") (class "Default")
      (node (ref "E15") (pin "13") (pinfunction "D5_13") (pintype "input"))
      (node (ref "E45") (pin "10") (pinfunction "I1_10") (pintype "output"))
      (node (ref "E81") (pin "8") (pinfunction "I1_8") (pintype "input"))
      (node (ref "E85") (pin "6") (pinfunction "D3_6") (pintype "input"))
      (node (ref "E88") (pin "6") (pinfunction "D3_6") (pintype "input"))
      (node (ref "E96") (pin "12") (pinfunction "2A1_12") (pintype "input"))
    )
    (net (code "232") (name "P3_BD11") (class "Default")
      (node (ref "E15") (pin "14") (pinfunction "D6_14") (pintype "input"))
      (node (ref "E45") (pin "13") (pinfunction "I0_13") (pintype "output"))
      (node (ref "E81") (pin "9") (pinfunction "I0_9") (pintype "input"))
      (node (ref "E85") (pin "11") (pinfunction "D4_11") (pintype "input"))
      (node (ref "E88") (pin "11") (pinfunction "D4_11") (pintype "input"))
      (node (ref "E96") (pin "14") (pinfunction "2A2_14") (pintype "input"))
    )
    (net (code "233") (name "P3_BF") (class "Default")
      (node (ref "E21") (pin "2") (pinfunction "I1_2") (pintype "input"))
      (node (ref "E30") (pin "11") (pinfunction "I6_11") (pintype "input"))
      (node (ref "E49") (pin "4") (pinfunction "I1_4") (pintype "input"))
      (node (ref "E61") (pin "13") (pinfunction "O_13") (pintype "output"))
    )
    (net (code "234") (name "P3_BINIT") (class "Default")
      (node (ref "E22") (pin "3") (pinfunction "I_3") (pintype "input"))
      (node (ref "E53") (pin "13") (pinfunction "O_13") (pintype "output"))
      (node (ref "E62") (pin "15") (pinfunction "CLR_15") (pintype "input"))
      (node (ref "E90") (pin "15") (pinfunction "CLR_15") (pintype "input"))
      (node (ref "E98") (pin "15") (pinfunction "CLR_15") (pintype "input"))
      (node (ref "E99") (pin "15") (pinfunction "CLR_15") (pintype "input"))
    )
    (net (code "235") (name "P3_BM0") (class "Default")
      (node (ref "E11") (pin "2") (pinfunction "O_2") (pintype "output"))
      (node (ref "E21") (pin "13") (pinfunction "I2_13") (pintype "input"))
      (node (ref "E30") (pin "1") (pinfunction "I0_1") (pintype "input"))
      (node (ref "E5") (pin "11") (pinfunction "I_11") (pintype "input"))
    )
    (net (code "236") (name "P3_BM1") (class "Default")
      (node (ref "E11") (pin "3") (pinfunction "O_3") (pintype "output"))
      (node (ref "E21") (pin "1") (pinfunction "I0_1") (pintype "input"))
      (node (ref "E29") (pin "3") (pinfunction "I1_3") (pintype "input"))
      (node (ref "E30") (pin "2") (pinfunction "I1_2") (pintype "input"))
    )
    (net (code "237") (name "P3_BM2") (class "Default")
      (node (ref "E11") (pin "13") (pinfunction "O_13") (pintype "output"))
      (node (ref "E14") (pin "21") (pinfunction "I14_21") (pintype "input"))
      (node (ref "E5") (pin "13") (pinfunction "I_13") (pintype "input"))
      (node (ref "E8") (pin "2") (pinfunction "I0_2") (pintype "input"))
    )
    (net (code "238") (name "P3_BM3") (class "Default")
      (node (ref "E11") (pin "14") (pinfunction "O_14") (pintype "output"))
      (node (ref "E14") (pin "22") (pinfunction "I13_22") (pintype "input"))
      (node (ref "E7") (pin "11") (pinfunction "I_11") (pintype "input"))
    )
    (net (code "239") (name "P3_BM4") (class "Default")
      (node (ref "E14") (pin "23") (pinfunction "I12_23") (pintype "input"))
      (node (ref "E25") (pin "2") (pinfunction "O_2") (pintype "output"))
      (node (ref "E28") (pin "3") (pinfunction "A4_3") (pintype "input"))
      (node (ref "E36") (pin "1") (pinfunction "I0_1") (pintype "input"))
      (node (ref "E7") (pin "13") (pinfunction "I_13") (pintype "input"))
    )
    (net (code "240") (name "P3_BM5") (class "Default")
      (node (ref "E113") (pin "6") (pinfunction "A1_6") (pintype "input"))
      (node (ref "E14") (pin "24") (pinfunction "I11_24") (pintype "input"))
      (node (ref "E25") (pin "3") (pinfunction "O_3") (pintype "output"))
      (node (ref "E28") (pin "4") (pinfunction "A3_4") (pintype "input"))
      (node (ref "E68") (pin "10") (pinfunction "A0_10") (pintype "input"))
    )
    (net (code "241") (name "P3_BM6") (class "Default")
      (node (ref "E14") (pin "25") (pinfunction "I10_25") (pintype "input"))
      (node (ref "E21") (pin "9") (pinfunction "I0_9") (pintype "input"))
      (node (ref "E25") (pin "13") (pinfunction "O_13") (pintype "output"))
      (node (ref "E31") (pin "21") (pinfunction "C_21") (pintype "input"))
      (node (ref "E78") (pin "13") (pinfunction "A2_13") (pintype "input"))
      (node (ref "E87") (pin "7") (pinfunction "A2_7") (pintype "input"))
    )
    (net (code "242") (name "P3_BM7") (class "Default")
      (node (ref "E14") (pin "26") (pinfunction "I9_26") (pintype "input"))
      (node (ref "E21") (pin "10") (pinfunction "I1_10") (pintype "input"))
      (node (ref "E25") (pin "14") (pinfunction "O_14") (pintype "output"))
      (node (ref "E31") (pin "22") (pinfunction "B_22") (pintype "input"))
      (node (ref "E78") (pin "12") (pinfunction "A1_12") (pintype "input"))
      (node (ref "E87") (pin "6") (pinfunction "A1_6") (pintype "input"))
    )
    (net (code "243") (name "P3_BM8") (class "Default")
      (node (ref "E14") (pin "27") (pinfunction "I8_27") (pintype "input"))
      (node (ref "E21") (pin "11") (pinfunction "I2_11") (pintype "input"))
      (node (ref "E31") (pin "23") (pinfunction "A_23") (pintype "input"))
      (node (ref "E71") (pin "2") (pinfunction "O_2") (pintype "output"))
      (node (ref "E78") (pin "10") (pinfunction "A0_10") (pintype "input"))
      (node (ref "E87") (pin "5") (pinfunction "A0_5") (pintype "input"))
    )
    (net (code "244") (name "P3_BM9") (class "Default")
      (node (ref "E113") (pin "5") (pinfunction "A0_5") (pintype "input"))
      (node (ref "E14") (pin "2") (pinfunction "I7_2") (pintype "input"))
      (node (ref "E28") (pin "7") (pinfunction "A2_7") (pintype "input"))
      (node (ref "E31") (pin "20") (pinfunction "D_20") (pintype "input"))
      (node (ref "E34") (pin "13") (pinfunction "C_13") (pintype "input"))
      (node (ref "E36") (pin "10") (pinfunction "I1_10") (pintype "input"))
      (node (ref "E43") (pin "4") (pinfunction "I2_4") (pintype "input"))
      (node (ref "E44") (pin "11") (pinfunction "I_11") (pintype "input"))
      (node (ref "E47") (pin "5") (pinfunction "I0_5") (pintype "input"))
      (node (ref "E47") (pin "9") (pinfunction "I1_9") (pintype "input"))
      (node (ref "E71") (pin "3") (pinfunction "O_3") (pintype "output"))
      (node (ref "E78") (pin "15") (pinfunction "A3_15") (pintype "input"))
    )
    (net (code "245") (name "P3_BM10") (class "Default")
      (node (ref "E14") (pin "3") (pinfunction "I6_3") (pintype "input"))
      (node (ref "E28") (pin "6") (pinfunction "A1_6") (pintype "input"))
      (node (ref "E34") (pin "14") (pinfunction "B_14") (pintype "input"))
      (node (ref "E71") (pin "13") (pinfunction "O_13") (pintype "output"))
    )
    (net (code "246") (name "P3_BM11") (class "Default")
      (node (ref "E14") (pin "4") (pinfunction "I5_4") (pintype "input"))
      (node (ref "E28") (pin "5") (pinfunction "A0_5") (pintype "input"))
      (node (ref "E34") (pin "15") (pinfunction "A_15") (pintype "input"))
      (node (ref "E36") (pin "12") (pinfunction "I2_12") (pintype "input"))
      (node (ref "E44") (pin "13") (pinfunction "I_13") (pintype "input"))
      (node (ref "E71") (pin "14") (pinfunction "O_14") (pintype "output"))
    )
    (net (code "247") (name "P3_BPAUSE") (class "Default")
      (node (ref "E14") (pin "5") (pinfunction "I4_5") (pintype "input"))
      (node (ref "E26") (pin "16") (pinfunction "1Q_16") (pintype "output"))
      (node (ref "E74") (pin "7") (pinfunction "A2_7") (pintype "input"))
    )
    (net (code "248") (name "P3_BPLA") (class "Default")
      (node (ref "E53") (pin "3") (pinfunction "O_3") (pintype "output"))
      (node (ref "E57") (pin "5") (pinfunction "I1_5") (pintype "input"))
    )
    (net (code "249") (name "P3_BTP1") (class "Default")
      (node (ref "E53") (pin "2") (pinfunction "O_2") (pintype "output"))
      (node (ref "E54") (pin "9") (pinfunction "I0_9") (pintype "input"))
    )
    (net (code "250") (name "P3_BTP2") (class "Default")
      (node (ref "E15") (pin "9") (pinfunction "CLK_9") (pintype "input"))
      (node (ref "E17") (pin "9") (pinfunction "CLK_9") (pintype "input"))
      (node (ref "E21") (pin "3") (pinfunction "I0_3") (pintype "input"))
      (node (ref "E22") (pin "1") (pinfunction "I_1") (pintype "input"))
      (node (ref "E53") (pin "14") (pinfunction "O_14") (pintype "output"))
    )
    (net (code "251") (name "P3_BTP3") (class "Default")
      (node (ref "E18") (pin "1") (pinfunction "I0_1") (pintype "input"))
      (node (ref "E18") (pin "4") (pinfunction "I0_4") (pintype "input"))
      (node (ref "E29") (pin "8") (pinfunction "I0_8") (pintype "input"))
      (node (ref "E32") (pin "11") (pinfunction "CLK_11") (pintype "input"))
      (node (ref "E38") (pin "3") (pinfunction "O_3") (pintype "output"))
      (node (ref "E50") (pin "12") (pinfunction "I0_12") (pintype "input"))
      (node (ref "E56") (pin "13") (pinfunction "I2_13") (pintype "input"))
      (node (ref "E6") (pin "1") (pinfunction "I0_1") (pintype "input"))
      (node (ref "E67") (pin "10") (pinfunction "I1_10") (pintype "input"))
      (node (ref "E76") (pin "11") (pinfunction "CLK_11") (pintype "input"))
    )
    (net (code "252") (name "P3_BTP4") (class "Default")
      (node (ref "E118") (pin "7") (pinfunction "CLK_7") (pintype "input"))
      (node (ref "E119") (pin "7") (pinfunction "CLK_7") (pintype "input"))
      (node (ref "E27") (pin "12") (pinfunction "O_12") (pintype "output"))
      (node (ref "E54") (pin "5") (pinfunction "I1_5") (pintype "input"))
      (node (ref "E57") (pin "9") (pinfunction "I0_9") (pintype "input"))
      (node (ref "E63") (pin "11") (pinfunction "CLK_11") (pintype "input"))
      (node (ref "E63") (pin "3") (pinfunction "CLK_3") (pintype "input"))
      (node (ref "E65") (pin "3") (pinfunction "CLK_3") (pintype "input"))
      (node (ref "E73") (pin "7") (pinfunction "CLK_7") (pintype "input"))
      (node (ref "E90") (pin "7") (pinfunction "CLK_7") (pintype "input"))
    )
    (net (code "253") (name "P3_BTS3") (class "Default")
      (node (ref "E20") (pin "12") (pinfunction "I1_12") (pintype "input"))
      (node (ref "E26") (pin "4") (pinfunction "1C,2C_4") (pintype "input"))
      (node (ref "E51") (pin "13") (pinfunction "O_13") (pintype "output"))
      (node (ref "E64") (pin "2") (pinfunction "I0_2") (pintype "input"))
      (node (ref "E64") (pin "3") (pinfunction "I1_3") (pintype "input"))
    )
    (net (code "254") (name "P3_BTS4") (class "Default")
      (node (ref "E20") (pin "2") (pinfunction "I0_2") (pintype "input"))
      (node (ref "E26") (pin "3") (pinfunction "2D_3") (pintype "input"))
      (node (ref "E51") (pin "3") (pinfunction "O_3") (pintype "output"))
      (node (ref "E6") (pin "10") (pinfunction "I1_10") (pintype "input"))
      (node (ref "E74") (pin "4") (pinfunction "A3_4") (pintype "input"))
      (node (ref "E81") (pin "21") (pinfunction "I14_21") (pintype "input"))
      (node (ref "E92") (pin "1") (pinfunction "I0_1") (pintype "input"))
    )
    (net (code "255") (name "P3_INIOEN") (class "Default")
      (node (ref "E14") (pin "10") (pinfunction "O7_10") (pintype "tri_state"))
      (node (ref "E36") (pin "13") (pinfunction "I3_13") (pintype "input"))
      (node (ref "E36") (pin "5") (pinfunction "I3_5") (pintype "input"))
      (node (ref "E43") (pin "5") (pinfunction "I3_5") (pintype "input"))
    )
    (net (code "256") (name "P3_MBK") (class "Default")
      (node (ref "E19") (pin "2") (pinfunction "I0_2") (pintype "input"))
      (node (ref "E19") (pin "3") (pinfunction "I1_3") (pintype "input"))
      (node (ref "E19") (pin "5") (pinfunction "I0_5") (pintype "input"))
      (node (ref "E19") (pin "6") (pinfunction "I1_6") (pintype "input"))
      (node (ref "E20") (pin "3") (pinfunction "I1_3") (pintype "input"))
      (node (ref "E21") (pin "5") (pinfunction "I2_5") (pintype "input"))
      (node (ref "E4") (pin "11") (pinfunction "I0_11") (pintype "input"))
      (node (ref "E4") (pin "12") (pinfunction "I1_12") (pintype "input"))
      (node (ref "E6") (pin "6") (pinfunction "O_6") (pintype "output"))
      (node (ref "E6") (pin "9") (pinfunction "I0_9") (pintype "input"))
    )
    (net (code "257") (name "P4_3V") (class "Default")
      (node (ref "E76") (pin "1") (pinfunction "CLR_1") (pintype "input"))
      (node (ref "E77") (pin "3") (pinfunction "R_3") (pintype "input"))
      (node (ref "R18") (pin "1") (pinfunction "1_1") (pintype "passive"))
    )
    (net (code "258") (name "P4_BTS1") (class "Default")
      (node (ref "E20") (pin "5") (pinfunction "I0_5") (pintype "input"))
      (node (ref "E41") (pin "13") (pinfunction "O_13") (pintype "output"))
      (node (ref "E92") (pin "10") (pinfunction "I1_10") (pintype "input"))
      (node (ref "E92") (pin "5") (pinfunction "I2_5") (pintype "input"))
      (node (ref "E94") (pin "2") (pinfunction "I1_2") (pintype "input"))
    )
    (net (code "259") (name "P4_CKDB") (class "Default")
      (node (ref "E108") (pin "9") (pinfunction "CLK_9") (pintype "input"))
      (node (ref "E69") (pin "13") (pinfunction "F3_13") (pintype "output"))
    )
    (net (code "260") (name "P4_CKDF") (class "Default")
      (node (ref "E102") (pin "9") (pinfunction "CLK_9") (pintype "input"))
      (node (ref "E79") (pin "3") (pinfunction "F0_3") (pintype "output"))
    )
    (net (code "261") (name "P4_CKIBB") (class "Default")
      (node (ref "E116") (pin "9") (pinfunction "CLK_9") (pintype "input"))
      (node (ref "E79") (pin "12") (pinfunction "F2_12") (pintype "output"))
    )
    (net (code "262") (name "P4_CKIF") (class "Default")
      (node (ref "E110") (pin "9") (pinfunction "CLK_9") (pintype "input"))
      (node (ref "E79") (pin "4") (pinfunction "F1_4") (pintype "output"))
      (node (ref "E93") (pin "9") (pinfunction "CLK_9") (pintype "input"))
    )
    (net (code "263") (name "P4_CKIFB") (class "Default")
      (node (ref "E79") (pin "13") (pinfunction "F3_13") (pintype "output"))
      (node (ref "E97") (pin "7") (pinfunction "CLK_7") (pintype "input"))
    )
    (net (code "264") (name "P4_CKSV") (class "Default")
      (node (ref "E103") (pin "9") (pinfunction "CLK_9") (pintype "input"))
      (node (ref "E117") (pin "9") (pinfunction "CLK_9") (pintype "input"))
      (node (ref "E58") (pin "4") (pinfunction "O_4") (pintype "output"))
      (node (ref "E59") (pin "3") (pinfunction "CLK_3") (pintype "input"))
    )
    (net (code "265") (name "P4_CKUF") (class "Default")
      (node (ref "E59") (pin "11") (pinfunction "CLK_11") (pintype "input"))
      (node (ref "E69") (pin "4") (pinfunction "F1_4") (pintype "output"))
    )
    (net (code "266") (name "P4_CKUFB") (class "Default")
      (node (ref "E60") (pin "3") (pinfunction "CLK_3") (pintype "input"))
      (node (ref "E69") (pin "12") (pinfunction "F2_12") (pintype "output"))
    )
    (net (code "267") (name "P4_DFEN") (class "Default")
      (node (ref "E66") (pin "12") (pinfunction "I0_12") (pintype "input"))
      (node (ref "E74") (pin "1") (pinfunction "A6_1") (pintype "input"))
      (node (ref "E76") (pin "8") (pinfunction "~{Q}_8") (pintype "output"))
      (node (ref "E94") (pin "4") (pinfunction "I0_4") (pintype "input"))
    )
    (net (code "268") (name "P4_FATAL(0)") (class "Default")
      (node (ref "E32") (pin "5") (pinfunction "Q_5") (pintype "output"))
      (node (ref "E83") (pin "12") (pinfunction "A1_12") (pintype "input"))
    )
    (net (code "269") (name "P4_INIT_EN") (class "Default")
      (node (ref "E76") (pin "6") (pinfunction "~{Q}_6") (pintype "output"))
      (node (ref "E94") (pin "5") (pinfunction "I1_5") (pintype "input"))
    )
    (net (code "270") (name "P4_INT") (class "Default")
      (node (ref "E115") (pin "3") (pinfunction "I_3") (pintype "input"))
      (node (ref "E29") (pin "4") (pinfunction "O_4") (pintype "output"))
      (node (ref "E57") (pin "10") (pinfunction "I1_10") (pintype "input"))
      (node (ref "E97") (pin "1") (pinfunction "M_1") (pintype "input"))
    )
    (net (code "271") (name "P4_INT_IN") (class "Default")
      (node (ref "E38") (pin "5") (pinfunction "I1_5") (pintype "input"))
      (node (ref "E4") (pin "5") (pinfunction "I0_5") (pintype "input"))
      (node (ref "E57") (pin "11") (pinfunction "O_11") (pintype "output"))
      (node (ref "E9") (pin "13") (pinfunction "I3_13") (pintype "input"))
    )
    (net (code "272") (name "P4_INT_IN_PROG") (class "Default")
      (node (ref "E29") (pin "5") (pinfunction "I0_5") (pintype "input"))
      (node (ref "E3") (pin "2") (pinfunction "O_2") (pintype "output"))
    )
    (net (code "273") (name "P4_JMP+JMS") (class "Default")
      (node (ref "E58") (pin "9") (pinfunction "I_9") (pintype "input"))
      (node (ref "E61") (pin "2") (pinfunction "O_2") (pintype "output"))
      (node (ref "E70") (pin "1") (pinfunction "I0_1") (pintype "input"))
    )
    (net (code "274") (name "P4_LXA") (class "Default")
      (node (ref "E39") (pin "11") (pinfunction "I_11") (pintype "input"))
      (node (ref "E48") (pin "11") (pinfunction "I0_11") (pintype "input"))
      (node (ref "E51") (pin "14") (pinfunction "O_14") (pintype "output"))
      (node (ref "E57") (pin "4") (pinfunction "I0_4") (pintype "input"))
      (node (ref "E61") (pin "10") (pinfunction "I1_10") (pintype "input"))
      (node (ref "E61") (pin "11") (pinfunction "I0_11") (pintype "input"))
    )
    (net (code "275") (name "P4_NEW_FLD") (class "Default")
      (node (ref "E115") (pin "1") (pinfunction "I_1") (pintype "input"))
      (node (ref "E115") (pin "11") (pinfunction "I_11") (pintype "input"))
      (node (ref "E18") (pin "10") (pinfunction "I1_10") (pintype "input"))
      (node (ref "E18") (pin "2") (pinfunction "I1_2") (pintype "input"))
      (node (ref "E56") (pin "2") (pinfunction "I1_2") (pintype "input"))
      (node (ref "E70") (pin "6") (pinfunction "O_6") (pintype "output"))
      (node (ref "E80") (pin "10") (pinfunction "A0_10") (pintype "input"))
    )
    (net (code "276") (name "P4_PCLR") (class "Default")
      (node (ref "E1") (pin "15") (pinfunction "CLR_15") (pintype "input"))
      (node (ref "E121") (pin "15") (pinfunction "CLR_15") (pintype "input"))
      (node (ref "E73") (pin "15") (pinfunction "CLR_15") (pintype "input"))
      (node (ref "E77") (pin "13") (pinfunction "Q_13") (pintype "output"))
    )
    (net (code "277") (name "P4_PLXA") (class "Default")
      (node (ref "E1") (pin "7") (pinfunction "CLK_7") (pintype "input"))
      (node (ref "E121") (pin "7") (pinfunction "CLK_7") (pintype "input"))
      (node (ref "E122") (pin "7") (pinfunction "CLK_7") (pintype "input"))
      (node (ref "E58") (pin "2") (pinfunction "O_2") (pintype "output"))
      (node (ref "E65") (pin "1") (pinfunction "CLR_1") (pintype "input"))
    )
    (net (code "278") (name "P4_USINT") (class "Default")
      (node (ref "E32") (pin "4") (pinfunction "PRE_4") (pintype "input"))
      (node (ref "E32") (pin "8") (pinfunction "~{Q}_8") (pintype "output"))
      (node (ref "E38") (pin "4") (pinfunction "I0_4") (pintype "input"))
      (node (ref "E42") (pin "11") (pinfunction "I0_11") (pintype "input"))
      (node (ref "E42") (pin "12") (pinfunction "I1_12") (pintype "input"))
      (node (ref "E42") (pin "5") (pinfunction "I0_5") (pintype "input"))
    )
    (net (code "279") (name "P6_BIND2") (class "Default")
      (node (ref "E20") (pin "6") (pinfunction "I1_6") (pintype "input"))
      (node (ref "E72") (pin "2") (pinfunction "O_2") (pintype "output"))
      (node (ref "E92") (pin "11") (pinfunction "I2_11") (pintype "input"))
      (node (ref "E92") (pin "4") (pinfunction "I1_4") (pintype "input"))
      (node (ref "E94") (pin "1") (pinfunction "I0_1") (pintype "input"))
    )
    (net (code "280") (name "P6_DIOI") (class "Default")
      (node (ref "E14") (pin "9") (pinfunction "I0_9") (pintype "input"))
      (node (ref "E46") (pin "15") (pinfunction "Q4_15") (pintype "output"))
    )
    (net (code "281") (name "P6_EBM") (class "Default")
      (node (ref "E46") (pin "10") (pinfunction "Q3_10") (pintype "output"))
      (node (ref "E74") (pin "6") (pinfunction "A1_6") (pintype "input"))
    )
    (net (code "282") (name "P6_EEM") (class "Default")
      (node (ref "E14") (pin "7") (pinfunction "I2_7") (pintype "input"))
      (node (ref "E35") (pin "15") (pinfunction "Q4_15") (pintype "output"))
      (node (ref "E47") (pin "8") (pinfunction "I0_8") (pintype "input"))
    )
    (net (code "283") (name "P6_EN5") (class "Default")
      (node (ref "E28") (pin "1") (pinfunction "A6_1") (pintype "input"))
      (node (ref "E35") (pin "10") (pinfunction "Q3_10") (pintype "output"))
    )
    (net (code "284") (name "P6_EN9") (class "Default")
      (node (ref "E28") (pin "2") (pinfunction "A5_2") (pintype "input"))
      (node (ref "E35") (pin "7") (pinfunction "Q2_7") (pintype "output"))
    )
    (net (code "285") (name "P6_MAINT") (class "Default")
      (node (ref "E18") (pin "9") (pinfunction "I0_9") (pintype "input"))
      (node (ref "E48") (pin "1") (pinfunction "O_1") (pintype "output"))
      (node (ref "E56") (pin "1") (pinfunction "I0_1") (pintype "input"))
    )
    (net (code "286") (name "P6_PRUP") (class "Default")
      (node (ref "E55") (pin "1") (pinfunction "1G_1") (pintype "input"))
      (node (ref "E64") (pin "8") (pinfunction "I0_8") (pintype "input"))
      (node (ref "E65") (pin "6") (pinfunction "~{Q}_6") (pintype "output"))
    )
    (net (code "287") (name "P6_RVFEN") (class "Default")
      (node (ref "E14") (pin "6") (pinfunction "I3_6") (pintype "input"))
      (node (ref "E35") (pin "2") (pinfunction "Q1_2") (pintype "output"))
    )
    (net (code "288") (name "P6_USM") (class "Default")
      (node (ref "E111") (pin "14") (pinfunction "A8_14") (pintype "input"))
      (node (ref "E112") (pin "1") (pinfunction "A6_1") (pintype "input"))
      (node (ref "E112") (pin "14") (pinfunction "A8_14") (pintype "input"))
      (node (ref "E113") (pin "15") (pinfunction "A7_15") (pintype "input"))
      (node (ref "E114") (pin "14") (pinfunction "A8_14") (pintype "input"))
      (node (ref "E14") (pin "8") (pinfunction "I1_8") (pintype "input"))
      (node (ref "E30") (pin "12") (pinfunction "I7_12") (pintype "input"))
      (node (ref "E49") (pin "9") (pinfunction "I0_9") (pintype "input"))
      (node (ref "E59") (pin "8") (pinfunction "~{Q}_8") (pintype "output"))
      (node (ref "E8") (pin "3") (pinfunction "I1_3") (pintype "input"))
      (node (ref "E8") (pin "6") (pinfunction "I1_6") (pintype "input"))
      (node (ref "E87") (pin "15") (pinfunction "A7_15") (pintype "input"))
    )
    (net (code "289") (name "PULSE_LA") (class "Default")
      (node (ref "E53") (pin "5") (pinfunction "I1_5") (pintype "input"))
      (node (ref "U$1") (pin "DR2") (pinfunction "1_DR2") (pintype "bidirectional"))
    )
    (net (code "290") (name "TP1") (class "Default")
      (node (ref "E53") (pin "7") (pinfunction "I1_7") (pintype "input"))
      (node (ref "U$1") (pin "CD2") (pinfunction "1_CD2") (pintype "bidirectional"))
    )
    (net (code "291") (name "TP2") (class "Default")
      (node (ref "E53") (pin "10") (pinfunction "I1_10") (pintype "input"))
      (node (ref "U$1") (pin "CE2") (pinfunction "1_CE2") (pintype "bidirectional"))
    )
    (net (code "292") (name "TP3") (class "Default")
      (node (ref "E51") (pin "7") (pinfunction "I1_7") (pintype "input"))
      (node (ref "U$1") (pin "CH2") (pinfunction "1_CH2") (pintype "bidirectional"))
    )
    (net (code "293") (name "TP4") (class "Default")
      (node (ref "E27") (pin "1") (pinfunction "I0_1") (pintype "input"))
      (node (ref "E27") (pin "13") (pinfunction "I2_13") (pintype "input"))
      (node (ref "E27") (pin "2") (pinfunction "I1_2") (pintype "input"))
      (node (ref "U$1") (pin "CJ2") (pinfunction "1_CJ2") (pintype "bidirectional"))
    )
    (net (code "294") (name "VCC") (class "Default")
      (node (ref "C1") (pin "+") (pinfunction "+_+") (pintype "passive"))
      (node (ref "C10") (pin "1") (pinfunction "1_1") (pintype "passive"))
      (node (ref "C11") (pin "1") (pinfunction "1_1") (pintype "passive"))
      (node (ref "C13") (pin "1") (pinfunction "1_1") (pintype "passive"))
      (node (ref "C14") (pin "+") (pinfunction "+_+") (pintype "passive"))
      (node (ref "C15") (pin "1") (pinfunction "1_1") (pintype "passive"))
      (node (ref "C16") (pin "+") (pinfunction "+_+") (pintype "passive"))
      (node (ref "C17") (pin "1") (pinfunction "1_1") (pintype "passive"))
      (node (ref "C18") (pin "1") (pinfunction "1_1") (pintype "passive"))
      (node (ref "C2") (pin "1") (pinfunction "1_1") (pintype "passive"))
      (node (ref "C20") (pin "1") (pinfunction "1_1") (pintype "passive"))
      (node (ref "C21") (pin "1") (pinfunction "1_1") (pintype "passive"))
      (node (ref "C22") (pin "1") (pinfunction "1_1") (pintype "passive"))
      (node (ref "C23") (pin "1") (pinfunction "1_1") (pintype "passive"))
      (node (ref "C24") (pin "+") (pinfunction "+_+") (pintype "passive"))
      (node (ref "C25") (pin "1") (pinfunction "1_1") (pintype "passive"))
      (node (ref "C26") (pin "1") (pinfunction "1_1") (pintype "passive"))
      (node (ref "C27") (pin "1") (pinfunction "1_1") (pintype "passive"))
      (node (ref "C28") (pin "1") (pinfunction "1_1") (pintype "passive"))
      (node (ref "C29") (pin "1") (pinfunction "1_1") (pintype "passive"))
      (node (ref "C3") (pin "1") (pinfunction "1_1") (pintype "passive"))
      (node (ref "C31") (pin "1") (pinfunction "1_1") (pintype "passive"))
      (node (ref "C32") (pin "1") (pinfunction "1_1") (pintype "passive"))
      (node (ref "C33") (pin "1") (pinfunction "1_1") (pintype "passive"))
      (node (ref "C34") (pin "1") (pinfunction "1_1") (pintype "passive"))
      (node (ref "C35") (pin "1") (pinfunction "1_1") (pintype "passive"))
      (node (ref "C36") (pin "1") (pinfunction "1_1") (pintype "passive"))
      (node (ref "C4") (pin "1") (pinfunction "1_1") (pintype "passive"))
      (node (ref "C5") (pin "1") (pinfunction "1_1") (pintype "passive"))
      (node (ref "C6") (pin "1") (pinfunction "1_1") (pintype "passive"))
      (node (ref "C7") (pin "1") (pinfunction "1_1") (pintype "passive"))
      (node (ref "C8") (pin "+") (pinfunction "+_+") (pintype "passive"))
      (node (ref "C9") (pin "1") (pinfunction "1_1") (pintype "passive"))
      (node (ref "E101") (pin "16") (pinfunction "+UB_16") (pintype "power_in"))
      (node (ref "E26") (pin "5") (pinfunction "+UB_5") (pintype "power_in"))
      (node (ref "E83") (pin "16") (pinfunction "+UB_16") (pintype "power_in"))
      (node (ref "R1") (pin "1") (pinfunction "1_1") (pintype "passive"))
      (node (ref "R10") (pin "2") (pinfunction "2_2") (pintype "passive"))
      (node (ref "R11") (pin "2") (pinfunction "2_2") (pintype "passive"))
      (node (ref "R12") (pin "1") (pinfunction "1_1") (pintype "passive"))
      (node (ref "R13") (pin "2") (pinfunction "2_2") (pintype "passive"))
      (node (ref "R14") (pin "2") (pinfunction "2_2") (pintype "passive"))
      (node (ref "R15") (pin "2") (pinfunction "2_2") (pintype "passive"))
      (node (ref "R16") (pin "2") (pinfunction "2_2") (pintype "passive"))
      (node (ref "R17") (pin "2") (pinfunction "2_2") (pintype "passive"))
      (node (ref "R18") (pin "2") (pinfunction "2_2") (pintype "passive"))
      (node (ref "R19") (pin "2") (pinfunction "2_2") (pintype "passive"))
      (node (ref "R2") (pin "1") (pinfunction "1_1") (pintype "passive"))
      (node (ref "R20") (pin "1") (pinfunction "1_1") (pintype "passive"))
      (node (ref "R21") (pin "2") (pinfunction "2_2") (pintype "passive"))
      (node (ref "R22") (pin "2") (pinfunction "2_2") (pintype "passive"))
      (node (ref "R23") (pin "2") (pinfunction "2_2") (pintype "passive"))
      (node (ref "R24") (pin "1") (pinfunction "1_1") (pintype "passive"))
      (node (ref "R25") (pin "1") (pinfunction "1_1") (pintype "passive"))
      (node (ref "R26") (pin "1") (pinfunction "1_1") (pintype "passive"))
      (node (ref "R27") (pin "1") (pinfunction "1_1") (pintype "passive"))
      (node (ref "R28") (pin "2") (pinfunction "2_2") (pintype "passive"))
      (node (ref "R29") (pin "2") (pinfunction "2_2") (pintype "passive"))
      (node (ref "R3") (pin "2") (pinfunction "2_2") (pintype "passive"))
      (node (ref "R30") (pin "2") (pinfunction "2_2") (pintype "passive"))
      (node (ref "R31") (pin "1") (pinfunction "1_1") (pintype "passive"))
      (node (ref "R32") (pin "2") (pinfunction "2_2") (pintype "passive"))
      (node (ref "R33") (pin "2") (pinfunction "2_2") (pintype "passive"))
      (node (ref "R34") (pin "2") (pinfunction "2_2") (pintype "passive"))
      (node (ref "R35") (pin "2") (pinfunction "2_2") (pintype "passive"))
      (node (ref "R36") (pin "2") (pinfunction "2_2") (pintype "passive"))
      (node (ref "R37") (pin "2") (pinfunction "2_2") (pintype "passive"))
      (node (ref "R38") (pin "2") (pinfunction "2_2") (pintype "passive"))
      (node (ref "R39") (pin "2") (pinfunction "2_2") (pintype "passive"))
      (node (ref "R4") (pin "2") (pinfunction "2_2") (pintype "passive"))
      (node (ref "R6") (pin "1") (pinfunction "1_1") (pintype "passive"))
      (node (ref "R7") (pin "1") (pinfunction "1_1") (pintype "passive"))
      (node (ref "R8") (pin "1") (pinfunction "1_1") (pintype "passive"))
      (node (ref "R9") (pin "1") (pinfunction "1_1") (pintype "passive"))
      (node (ref "U$1") (pin "AA2") (pinfunction "1_AA2") (pintype "bidirectional"))
      (node (ref "U$1") (pin "BA2") (pinfunction "1_BA2") (pintype "bidirectional"))
      (node (ref "U$1") (pin "CA2") (pinfunction "1_CA2") (pintype "bidirectional"))
    )
    (net (code "295") (name "unconnected-(E1A-D1-Pad14)") (class "Default")
      (node (ref "E1") (pin "14") (pinfunction "D1_14") (pintype "input"))
    )
    (net (code "296") (name "unconnected-(E1A-Q1-Pad3)") (class "Default")
      (node (ref "E1") (pin "3") (pinfunction "Q1_3") (pintype "tri_state"))
    )
    (net (code "297") (name "unconnected-(E2E-I-Pad11)") (class "Default")
      (node (ref "E2") (pin "11") (pinfunction "I_11") (pintype "input"))
    )
    (net (code "298") (name "unconnected-(E2E-O-Pad10)") (class "Default")
      (node (ref "E2") (pin "10") (pinfunction "O_10") (pintype "output"))
    )
    (net (code "299") (name "unconnected-(E2F-I-Pad13)") (class "Default")
      (node (ref "E2") (pin "13") (pinfunction "I_13") (pintype "input"))
    )
    (net (code "300") (name "unconnected-(E2F-O-Pad12)") (class "Default")
      (node (ref "E2") (pin "12") (pinfunction "O_12") (pintype "output"))
    )
    (net (code "301") (name "unconnected-(E3C-I0-Pad9)") (class "Default")
      (node (ref "E3") (pin "9") (pinfunction "I0_9") (pintype "input"))
    )
    (net (code "302") (name "unconnected-(E3C-I1-Pad10)") (class "Default")
      (node (ref "E3") (pin "10") (pinfunction "I1_10") (pintype "input"))
    )
    (net (code "303") (name "unconnected-(E3C-O-Pad14)") (class "Default")
      (node (ref "E3") (pin "14") (pinfunction "O_14") (pintype "output"))
    )
    (net (code "304") (name "unconnected-(E4A-I0-Pad2)") (class "Default")
      (node (ref "E4") (pin "2") (pinfunction "I0_2") (pintype "input"))
    )
    (net (code "305") (name "unconnected-(E4A-I1-Pad3)") (class "Default")
      (node (ref "E4") (pin "3") (pinfunction "I1_3") (pintype "input"))
    )
    (net (code "306") (name "unconnected-(E4A-O-Pad1)") (class "Default")
      (node (ref "E4") (pin "1") (pinfunction "O_1") (pintype "open_collector"))
    )
    (net (code "307") (name "unconnected-(E10-Pad1)") (class "Default")
      (node (ref "E10") (pin "1") (pinfunction "1_1") (pintype "passive"))
    )
    (net (code "308") (name "unconnected-(E10-Pad2)") (class "Default")
      (node (ref "E10") (pin "2") (pinfunction "2_2") (pintype "passive"))
    )
    (net (code "309") (name "unconnected-(E10-Pad3)") (class "Default")
      (node (ref "E10") (pin "3") (pinfunction "3_3") (pintype "passive"))
    )
    (net (code "310") (name "unconnected-(E10-Pad4)") (class "Default")
      (node (ref "E10") (pin "4") (pinfunction "4_4") (pintype "passive"))
    )
    (net (code "311") (name "unconnected-(E10-Pad5)") (class "Default")
      (node (ref "E10") (pin "5") (pinfunction "5_5") (pintype "passive"))
    )
    (net (code "312") (name "unconnected-(E10-Pad6)") (class "Default")
      (node (ref "E10") (pin "6") (pinfunction "6_6") (pintype "passive"))
    )
    (net (code "313") (name "unconnected-(E10-Pad7)") (class "Default")
      (node (ref "E10") (pin "7") (pinfunction "7_7") (pintype "passive"))
    )
    (net (code "314") (name "unconnected-(E10-Pad8)") (class "Default")
      (node (ref "E10") (pin "8") (pinfunction "8_8") (pintype "passive"))
    )
    (net (code "315") (name "unconnected-(E10-Pad9)") (class "Default")
      (node (ref "E10") (pin "9") (pinfunction "9_9") (pintype "passive"))
    )
    (net (code "316") (name "unconnected-(E10-Pad10)") (class "Default")
      (node (ref "E10") (pin "10") (pinfunction "10_10") (pintype "passive"))
    )
    (net (code "317") (name "unconnected-(E10-Pad11)") (class "Default")
      (node (ref "E10") (pin "11") (pinfunction "11_11") (pintype "passive"))
    )
    (net (code "318") (name "unconnected-(E10-Pad12)") (class "Default")
      (node (ref "E10") (pin "12") (pinfunction "12_12") (pintype "passive"))
    )
    (net (code "319") (name "unconnected-(E10-Pad13)") (class "Default")
      (node (ref "E10") (pin "13") (pinfunction "13_13") (pintype "passive"))
    )
    (net (code "320") (name "unconnected-(E10-Pad14)") (class "Default")
      (node (ref "E10") (pin "14") (pinfunction "14_14") (pintype "passive"))
    )
    (net (code "321") (name "unconnected-(E10-Pad15)") (class "Default")
      (node (ref "E10") (pin "15") (pinfunction "15_15") (pintype "passive"))
    )
    (net (code "322") (name "unconnected-(E10-Pad16)") (class "Default")
      (node (ref "E10") (pin "16") (pinfunction "16_16") (pintype "passive"))
    )
    (net (code "323") (name "unconnected-(E20C-I0-Pad8)") (class "Default")
      (node (ref "E20") (pin "8") (pinfunction "I0_8") (pintype "input"))
    )
    (net (code "324") (name "unconnected-(E20C-I1-Pad9)") (class "Default")
      (node (ref "E20") (pin "9") (pinfunction "I1_9") (pintype "input"))
    )
    (net (code "325") (name "unconnected-(E20C-O-Pad10)") (class "Default")
      (node (ref "E20") (pin "10") (pinfunction "O_10") (pintype "open_collector"))
    )
    (net (code "326") (name "unconnected-(E26C-1D-Pad6)") (class "Default")
      (node (ref "E26") (pin "6") (pinfunction "1D_6") (pintype "input"))
    )
    (net (code "327") (name "unconnected-(E26C-1Q-Pad10)") (class "Default")
      (node (ref "E26") (pin "10") (pinfunction "1Q_10") (pintype "output"))
    )
    (net (code "328") (name "unconnected-(E26C-2Q-Pad9)") (class "Default")
      (node (ref "E26") (pin "9") (pinfunction "2Q_9") (pintype "output"))
    )
    (net (code "329") (name "unconnected-(E26C-~{1Q}-Pad11)") (class "Default")
      (node (ref "E26") (pin "11") (pinfunction "~{1Q}_11") (pintype "output"))
    )
    (net (code "330") (name "unconnected-(E26D-~{1Q}-Pad1)") (class "Default")
      (node (ref "E26") (pin "1") (pinfunction "~{1Q}_1") (pintype "output"))
    )
    (net (code "331") (name "unconnected-(E26D-~{2Q}-Pad14)") (class "Default")
      (node (ref "E26") (pin "14") (pinfunction "~{2Q}_14") (pintype "output"))
    )
    (net (code "332") (name "unconnected-(E27C-I0-Pad9)") (class "Default")
      (node (ref "E27") (pin "9") (pinfunction "I0_9") (pintype "input"))
    )
    (net (code "333") (name "unconnected-(E27C-I1-Pad10)") (class "Default")
      (node (ref "E27") (pin "10") (pinfunction "I1_10") (pintype "input"))
    )
    (net (code "334") (name "unconnected-(E27C-I2-Pad11)") (class "Default")
      (node (ref "E27") (pin "11") (pinfunction "I2_11") (pintype "input"))
    )
    (net (code "335") (name "unconnected-(E27C-O-Pad8)") (class "Default")
      (node (ref "E27") (pin "8") (pinfunction "O_8") (pintype "output"))
    )
    (net (code "336") (name "unconnected-(E31A-0-Pad1)") (class "Default")
      (node (ref "E31") (pin "1") (pinfunction "0_1") (pintype "output"))
    )
    (net (code "337") (name "unconnected-(E32A-D-Pad2)") (class "Default")
      (node (ref "E32") (pin "2") (pinfunction "D_2") (pintype "input"))
    )
    (net (code "338") (name "unconnected-(E34A-O8-Pad10)") (class "Default")
      (node (ref "E34") (pin "10") (pinfunction "O8_10") (pintype "output"))
    )
    (net (code "339") (name "unconnected-(E34A-O9-Pad11)") (class "Default")
      (node (ref "E34") (pin "11") (pinfunction "O9_11") (pintype "output"))
    )
    (net (code "340") (name "unconnected-(E40-Pad1)") (class "Default")
      (node (ref "E40") (pin "1") (pinfunction "1_1") (pintype "passive"))
    )
    (net (code "341") (name "unconnected-(E40-Pad2)") (class "Default")
      (node (ref "E40") (pin "2") (pinfunction "2_2") (pintype "passive"))
    )
    (net (code "342") (name "unconnected-(E40-Pad3)") (class "Default")
      (node (ref "E40") (pin "3") (pinfunction "3_3") (pintype "passive"))
    )
    (net (code "343") (name "unconnected-(E40-Pad4)") (class "Default")
      (node (ref "E40") (pin "4") (pinfunction "4_4") (pintype "passive"))
    )
    (net (code "344") (name "unconnected-(E40-Pad5)") (class "Default")
      (node (ref "E40") (pin "5") (pinfunction "5_5") (pintype "passive"))
    )
    (net (code "345") (name "unconnected-(E40-Pad6)") (class "Default")
      (node (ref "E40") (pin "6") (pinfunction "6_6") (pintype "passive"))
    )
    (net (code "346") (name "unconnected-(E40-Pad7)") (class "Default")
      (node (ref "E40") (pin "7") (pinfunction "7_7") (pintype "passive"))
    )
    (net (code "347") (name "unconnected-(E40-Pad8)") (class "Default")
      (node (ref "E40") (pin "8") (pinfunction "8_8") (pintype "passive"))
    )
    (net (code "348") (name "unconnected-(E40-Pad9)") (class "Default")
      (node (ref "E40") (pin "9") (pinfunction "9_9") (pintype "passive"))
    )
    (net (code "349") (name "unconnected-(E40-Pad10)") (class "Default")
      (node (ref "E40") (pin "10") (pinfunction "10_10") (pintype "passive"))
    )
    (net (code "350") (name "unconnected-(E40-Pad11)") (class "Default")
      (node (ref "E40") (pin "11") (pinfunction "11_11") (pintype "passive"))
    )
    (net (code "351") (name "unconnected-(E40-Pad12)") (class "Default")
      (node (ref "E40") (pin "12") (pinfunction "12_12") (pintype "passive"))
    )
    (net (code "352") (name "unconnected-(E40-Pad13)") (class "Default")
      (node (ref "E40") (pin "13") (pinfunction "13_13") (pintype "passive"))
    )
    (net (code "353") (name "unconnected-(E40-Pad14)") (class "Default")
      (node (ref "E40") (pin "14") (pinfunction "14_14") (pintype "passive"))
    )
    (net (code "354") (name "unconnected-(E40-Pad15)") (class "Default")
      (node (ref "E40") (pin "15") (pinfunction "15_15") (pintype "passive"))
    )
    (net (code "355") (name "unconnected-(E40-Pad16)") (class "Default")
      (node (ref "E40") (pin "16") (pinfunction "16_16") (pintype "passive"))
    )
    (net (code "356") (name "unconnected-(E43B-I0-Pad9)") (class "Default")
      (node (ref "E43") (pin "9") (pinfunction "I0_9") (pintype "input"))
    )
    (net (code "357") (name "unconnected-(E43B-I1-Pad10)") (class "Default")
      (node (ref "E43") (pin "10") (pinfunction "I1_10") (pintype "input"))
    )
    (net (code "358") (name "unconnected-(E43B-I2-Pad12)") (class "Default")
      (node (ref "E43") (pin "12") (pinfunction "I2_12") (pintype "input"))
    )
    (net (code "359") (name "unconnected-(E43B-I3-Pad13)") (class "Default")
      (node (ref "E43") (pin "13") (pinfunction "I3_13") (pintype "input"))
    )
    (net (code "360") (name "unconnected-(E43B-O-Pad8)") (class "Default")
      (node (ref "E43") (pin "8") (pinfunction "O_8") (pintype "output"))
    )
    (net (code "361") (name "unconnected-(E46A-D1-Pad4)") (class "Default")
      (node (ref "E46") (pin "4") (pinfunction "D1_4") (pintype "input"))
    )
    (net (code "362") (name "unconnected-(E46A-Q1-Pad2)") (class "Default")
      (node (ref "E46") (pin "2") (pinfunction "Q1_2") (pintype "output"))
    )
    (net (code "363") (name "unconnected-(E46A-Q2-Pad7)") (class "Default")
      (node (ref "E46") (pin "7") (pinfunction "Q2_7") (pintype "output"))
    )
    (net (code "364") (name "unconnected-(E46A-~{Q1}-Pad3)") (class "Default")
      (node (ref "E46") (pin "3") (pinfunction "~{Q1}_3") (pintype "output"))
    )
    (net (code "365") (name "unconnected-(E55A-2A2-Pad14)") (class "Default")
      (node (ref "E55") (pin "14") (pinfunction "2A2_14") (pintype "input"))
    )
    (net (code "366") (name "unconnected-(E55A-2Y2-Pad13)") (class "Default")
      (node (ref "E55") (pin "13") (pinfunction "2Y2_13") (pintype "tri_state"))
    )
    (net (code "367") (name "unconnected-(E58C-I-Pad5)") (class "Default")
      (node (ref "E58") (pin "5") (pinfunction "I_5") (pintype "input"))
    )
    (net (code "368") (name "unconnected-(E58C-O-Pad6)") (class "Default")
      (node (ref "E58") (pin "6") (pinfunction "O_6") (pintype "output"))
    )
    (net (code "369") (name "unconnected-(E58E-I-Pad11)") (class "Default")
      (node (ref "E58") (pin "11") (pinfunction "I_11") (pintype "input"))
    )
    (net (code "370") (name "unconnected-(E58E-O-Pad10)") (class "Default")
      (node (ref "E58") (pin "10") (pinfunction "O_10") (pintype "output"))
    )
    (net (code "371") (name "unconnected-(E59A-Q-Pad5)") (class "Default")
      (node (ref "E59") (pin "5") (pinfunction "Q_5") (pintype "output"))
    )
    (net (code "372") (name "unconnected-(E60A-Q-Pad5)") (class "Default")
      (node (ref "E60") (pin "5") (pinfunction "Q_5") (pintype "output"))
    )
    (net (code "373") (name "unconnected-(E60B-CLK-Pad11)") (class "Default")
      (node (ref "E60") (pin "11") (pinfunction "CLK_11") (pintype "input"))
    )
    (net (code "374") (name "unconnected-(E60B-CLR-Pad13)") (class "Default")
      (node (ref "E60") (pin "13") (pinfunction "CLR_13") (pintype "input"))
    )
    (net (code "375") (name "unconnected-(E60B-D-Pad12)") (class "Default")
      (node (ref "E60") (pin "12") (pinfunction "D_12") (pintype "input"))
    )
    (net (code "376") (name "unconnected-(E60B-PRE-Pad10)") (class "Default")
      (node (ref "E60") (pin "10") (pinfunction "PRE_10") (pintype "input"))
    )
    (net (code "377") (name "unconnected-(E60B-Q-Pad9)") (class "Default")
      (node (ref "E60") (pin "9") (pinfunction "Q_9") (pintype "output"))
    )
    (net (code "378") (name "unconnected-(E60B-~{Q}-Pad8)") (class "Default")
      (node (ref "E60") (pin "8") (pinfunction "~{Q}_8") (pintype "output"))
    )
    (net (code "379") (name "unconnected-(E62A-D1-Pad14)") (class "Default")
      (node (ref "E62") (pin "14") (pinfunction "D1_14") (pintype "input"))
    )
    (net (code "380") (name "unconnected-(E62A-Q1-Pad3)") (class "Default")
      (node (ref "E62") (pin "3") (pinfunction "Q1_3") (pintype "tri_state"))
    )
    (net (code "381") (name "unconnected-(E64C-O-Pad10)") (class "Default")
      (node (ref "E64") (pin "10") (pinfunction "O_10") (pintype "output"))
    )
    (net (code "382") (name "unconnected-(E64D-I0-Pad11)") (class "Default")
      (node (ref "E64") (pin "11") (pinfunction "I0_11") (pintype "input"))
    )
    (net (code "383") (name "unconnected-(E64D-I1-Pad12)") (class "Default")
      (node (ref "E64") (pin "12") (pinfunction "I1_12") (pintype "input"))
    )
    (net (code "384") (name "unconnected-(E64D-O-Pad13)") (class "Default")
      (node (ref "E64") (pin "13") (pinfunction "O_13") (pintype "output"))
    )
    (net (code "385") (name "unconnected-(E65B-CLK-Pad11)") (class "Default")
      (node (ref "E65") (pin "11") (pinfunction "CLK_11") (pintype "input"))
    )
    (net (code "386") (name "unconnected-(E65B-CLR-Pad13)") (class "Default")
      (node (ref "E65") (pin "13") (pinfunction "CLR_13") (pintype "input"))
    )
    (net (code "387") (name "unconnected-(E65B-D-Pad12)") (class "Default")
      (node (ref "E65") (pin "12") (pinfunction "D_12") (pintype "input"))
    )
    (net (code "388") (name "unconnected-(E65B-PRE-Pad10)") (class "Default")
      (node (ref "E65") (pin "10") (pinfunction "PRE_10") (pintype "input"))
    )
    (net (code "389") (name "unconnected-(E65B-Q-Pad9)") (class "Default")
      (node (ref "E65") (pin "9") (pinfunction "Q_9") (pintype "output"))
    )
    (net (code "390") (name "unconnected-(E65B-~{Q}-Pad8)") (class "Default")
      (node (ref "E65") (pin "8") (pinfunction "~{Q}_8") (pintype "output"))
    )
    (net (code "391") (name "unconnected-(E66C-I0-Pad9)") (class "Default")
      (node (ref "E66") (pin "9") (pinfunction "I0_9") (pintype "input"))
    )
    (net (code "392") (name "unconnected-(E66C-I1-Pad10)") (class "Default")
      (node (ref "E66") (pin "10") (pinfunction "I1_10") (pintype "input"))
    )
    (net (code "393") (name "unconnected-(E66C-O-Pad8)") (class "Default")
      (node (ref "E66") (pin "8") (pinfunction "O_8") (pintype "output"))
    )
    (net (code "394") (name "unconnected-(E68A-A<B_O-Pad7)") (class "Default")
      (node (ref "E68") (pin "7") (pinfunction "A<B_O_7") (pintype "output"))
    )
    (net (code "395") (name "unconnected-(E72C-I0-Pad9)") (class "Default")
      (node (ref "E72") (pin "9") (pinfunction "I0_9") (pintype "input"))
    )
    (net (code "396") (name "unconnected-(E72C-I1-Pad10)") (class "Default")
      (node (ref "E72") (pin "10") (pinfunction "I1_10") (pintype "input"))
    )
    (net (code "397") (name "unconnected-(E72C-O-Pad14)") (class "Default")
      (node (ref "E72") (pin "14") (pinfunction "O_14") (pintype "output"))
    )
    (net (code "398") (name "unconnected-(E72D-I0-Pad11)") (class "Default")
      (node (ref "E72") (pin "11") (pinfunction "I0_11") (pintype "input"))
    )
    (net (code "399") (name "unconnected-(E72D-I1-Pad12)") (class "Default")
      (node (ref "E72") (pin "12") (pinfunction "I1_12") (pintype "input"))
    )
    (net (code "400") (name "unconnected-(E72D-O-Pad13)") (class "Default")
      (node (ref "E72") (pin "13") (pinfunction "O_13") (pintype "output"))
    )
    (net (code "401") (name "unconnected-(E73A-D1-Pad14)") (class "Default")
      (node (ref "E73") (pin "14") (pinfunction "D1_14") (pintype "input"))
    )
    (net (code "402") (name "unconnected-(E73A-Q1-Pad3)") (class "Default")
      (node (ref "E73") (pin "3") (pinfunction "Q1_3") (pintype "tri_state"))
    )
    (net (code "403") (name "unconnected-(E75A-I0-Pad4)") (class "Default")
      (node (ref "E75") (pin "4") (pinfunction "I0_4") (pintype "input"))
    )
    (net (code "404") (name "unconnected-(E75A-I1-Pad5)") (class "Default")
      (node (ref "E75") (pin "5") (pinfunction "I1_5") (pintype "input"))
    )
    (net (code "405") (name "unconnected-(E75A-O-Pad3)") (class "Default")
      (node (ref "E75") (pin "3") (pinfunction "O_3") (pintype "output"))
    )
    (net (code "406") (name "unconnected-(E75C-I0-Pad9)") (class "Default")
      (node (ref "E75") (pin "9") (pinfunction "I0_9") (pintype "input"))
    )
    (net (code "407") (name "unconnected-(E75C-I1-Pad10)") (class "Default")
      (node (ref "E75") (pin "10") (pinfunction "I1_10") (pintype "input"))
    )
    (net (code "408") (name "unconnected-(E75C-O-Pad14)") (class "Default")
      (node (ref "E75") (pin "14") (pinfunction "O_14") (pintype "output"))
    )
    (net (code "409") (name "unconnected-(E75D-I0-Pad11)") (class "Default")
      (node (ref "E75") (pin "11") (pinfunction "I0_11") (pintype "input"))
    )
    (net (code "410") (name "unconnected-(E75D-I1-Pad12)") (class "Default")
      (node (ref "E75") (pin "12") (pinfunction "I1_12") (pintype "input"))
    )
    (net (code "411") (name "unconnected-(E75D-O-Pad13)") (class "Default")
      (node (ref "E75") (pin "13") (pinfunction "O_13") (pintype "output"))
    )
    (net (code "412") (name "unconnected-(E77B-A-Pad9)") (class "Default")
      (node (ref "E77") (pin "9") (pinfunction "A_9") (pintype "input"))
    )
    (net (code "413") (name "unconnected-(E77B-B-Pad10)") (class "Default")
      (node (ref "E77") (pin "10") (pinfunction "B_10") (pintype "input"))
    )
    (net (code "414") (name "unconnected-(E77B-C-Pad6)") (class "Default")
      (node (ref "E77") (pin "6") (pinfunction "C_6") (pintype "input"))
    )
    (net (code "415") (name "unconnected-(E77B-Q-Pad5)") (class "Default")
      (node (ref "E77") (pin "5") (pinfunction "Q_5") (pintype "output"))
    )
    (net (code "416") (name "unconnected-(E77B-R-Pad11)") (class "Default")
      (node (ref "E77") (pin "11") (pinfunction "R_11") (pintype "input"))
    )
    (net (code "417") (name "unconnected-(E77B-R{slash}C-Pad7)") (class "Default")
      (node (ref "E77") (pin "7") (pinfunction "R/C_7") (pintype "input"))
    )
    (net (code "418") (name "unconnected-(E77B-~{Q}-Pad12)") (class "Default")
      (node (ref "E77") (pin "12") (pinfunction "~{Q}_12") (pintype "output"))
    )
    (net (code "419") (name "unconnected-(E81A-O0-Pad18)") (class "Default")
      (node (ref "E81") (pin "18") (pinfunction "O0_18") (pintype "tri_state"))
    )
    (net (code "420") (name "unconnected-(E82A-D2-Pad10)") (class "Default")
      (node (ref "E82") (pin "10") (pinfunction "D2_10") (pintype "input"))
    )
    (net (code "421") (name "unconnected-(E82A-D3-Pad12)") (class "Default")
      (node (ref "E82") (pin "12") (pinfunction "D3_12") (pintype "input"))
    )
    (net (code "422") (name "unconnected-(E82A-Q2-Pad9)") (class "Default")
      (node (ref "E82") (pin "9") (pinfunction "Q2_9") (pintype "output"))
    )
    (net (code "423") (name "unconnected-(E82A-Q3-Pad11)") (class "Default")
      (node (ref "E82") (pin "11") (pinfunction "Q3_11") (pintype "output"))
    )
    (net (code "424") (name "unconnected-(E83D-A4-Pad10)") (class "Default")
      (node (ref "E83") (pin "10") (pinfunction "A4_10") (pintype "input"))
    )
    (net (code "425") (name "unconnected-(E83D-Y4-Pad9)") (class "Default")
      (node (ref "E83") (pin "9") (pinfunction "Y4_9") (pintype "tri_state"))
    )
    (net (code "426") (name "unconnected-(E84A-1A4-Pad10)") (class "Default")
      (node (ref "E84") (pin "10") (pinfunction "1A4_10") (pintype "input"))
    )
    (net (code "427") (name "unconnected-(E84A-1Y4-Pad9)") (class "Default")
      (node (ref "E84") (pin "9") (pinfunction "1Y4_9") (pintype "tri_state"))
    )
    (net (code "428") (name "unconnected-(E84A-2A1-Pad12)") (class "Default")
      (node (ref "E84") (pin "12") (pinfunction "2A1_12") (pintype "input"))
    )
    (net (code "429") (name "unconnected-(E84A-2A2-Pad14)") (class "Default")
      (node (ref "E84") (pin "14") (pinfunction "2A2_14") (pintype "input"))
    )
    (net (code "430") (name "unconnected-(E84A-2G-Pad15)") (class "Default")
      (node (ref "E84") (pin "15") (pinfunction "2G_15") (pintype "input"))
    )
    (net (code "431") (name "unconnected-(E84A-2Y1-Pad11)") (class "Default")
      (node (ref "E84") (pin "11") (pinfunction "2Y1_11") (pintype "tri_state"))
    )
    (net (code "432") (name "unconnected-(E84A-2Y2-Pad13)") (class "Default")
      (node (ref "E84") (pin "13") (pinfunction "2Y2_13") (pintype "tri_state"))
    )
    (net (code "433") (name "unconnected-(E85A-D2-Pad4)") (class "Default")
      (node (ref "E85") (pin "4") (pinfunction "D2_4") (pintype "input"))
    )
    (net (code "434") (name "unconnected-(E85A-Q2-Pad5)") (class "Default")
      (node (ref "E85") (pin "5") (pinfunction "Q2_5") (pintype "output"))
    )
    (net (code "435") (name "unconnected-(E86A-2A2-Pad14)") (class "Default")
      (node (ref "E86") (pin "14") (pinfunction "2A2_14") (pintype "input"))
    )
    (net (code "436") (name "unconnected-(E86A-2Y2-Pad13)") (class "Default")
      (node (ref "E86") (pin "13") (pinfunction "2Y2_13") (pintype "tri_state"))
    )
    (net (code "437") (name "unconnected-(E89A-EO-Pad15)") (class "Default")
      (node (ref "E89") (pin "15") (pinfunction "EO_15") (pintype "output"))
    )
    (net (code "438") (name "unconnected-(E89A-GS-Pad14)") (class "Default")
      (node (ref "E89") (pin "14") (pinfunction "GS_14") (pintype "output"))
    )
    (net (code "439") (name "unconnected-(E93A-D1-Pad4)") (class "Default")
      (node (ref "E93") (pin "4") (pinfunction "D1_4") (pintype "input"))
    )
    (net (code "440") (name "unconnected-(E93A-Q1-Pad2)") (class "Default")
      (node (ref "E93") (pin "2") (pinfunction "Q1_2") (pintype "output"))
    )
    (net (code "441") (name "unconnected-(E93A-~{Q1}-Pad3)") (class "Default")
      (node (ref "E93") (pin "3") (pinfunction "~{Q1}_3") (pintype "output"))
    )
    (net (code "442") (name "unconnected-(E94C-I0-Pad9)") (class "Default")
      (node (ref "E94") (pin "9") (pinfunction "I0_9") (pintype "input"))
    )
    (net (code "443") (name "unconnected-(E94C-I1-Pad10)") (class "Default")
      (node (ref "E94") (pin "10") (pinfunction "I1_10") (pintype "input"))
    )
    (net (code "444") (name "unconnected-(E94C-O-Pad8)") (class "Default")
      (node (ref "E94") (pin "8") (pinfunction "O_8") (pintype "output"))
    )
    (net (code "445") (name "unconnected-(E94D-I0-Pad12)") (class "Default")
      (node (ref "E94") (pin "12") (pinfunction "I0_12") (pintype "input"))
    )
    (net (code "446") (name "unconnected-(E94D-I1-Pad13)") (class "Default")
      (node (ref "E94") (pin "13") (pinfunction "I1_13") (pintype "input"))
    )
    (net (code "447") (name "unconnected-(E94D-O-Pad11)") (class "Default")
      (node (ref "E94") (pin "11") (pinfunction "O_11") (pintype "output"))
    )
    (net (code "448") (name "unconnected-(E97A-CLR-Pad15)") (class "Default")
      (node (ref "E97") (pin "15") (pinfunction "CLR_15") (pintype "input"))
    )
    (net (code "449") (name "unconnected-(E97A-D1-Pad14)") (class "Default")
      (node (ref "E97") (pin "14") (pinfunction "D1_14") (pintype "input"))
    )
    (net (code "450") (name "unconnected-(E97A-G1-Pad9)") (class "Default")
      (node (ref "E97") (pin "9") (pinfunction "G1_9") (pintype "input"))
    )
    (net (code "451") (name "unconnected-(E97A-G2-Pad10)") (class "Default")
      (node (ref "E97") (pin "10") (pinfunction "G2_10") (pintype "input"))
    )
    (net (code "452") (name "unconnected-(E97A-Q1-Pad3)") (class "Default")
      (node (ref "E97") (pin "3") (pinfunction "Q1_3") (pintype "tri_state"))
    )
    (net (code "453") (name "unconnected-(E101D-A4-Pad10)") (class "Default")
      (node (ref "E101") (pin "10") (pinfunction "A4_10") (pintype "input"))
    )
    (net (code "454") (name "unconnected-(E101D-Y4-Pad9)") (class "Default")
      (node (ref "E101") (pin "9") (pinfunction "Y4_9") (pintype "tri_state"))
    )
    (net (code "455") (name "unconnected-(E102A-D1-Pad4)") (class "Default")
      (node (ref "E102") (pin "4") (pinfunction "D1_4") (pintype "input"))
    )
    (net (code "456") (name "unconnected-(E102A-Q1-Pad2)") (class "Default")
      (node (ref "E102") (pin "2") (pinfunction "Q1_2") (pintype "output"))
    )
    (net (code "457") (name "unconnected-(E102A-~{Q1}-Pad3)") (class "Default")
      (node (ref "E102") (pin "3") (pinfunction "~{Q1}_3") (pintype "output"))
    )
    (net (code "458") (name "unconnected-(E104A-1A4-Pad10)") (class "Default")
      (node (ref "E104") (pin "10") (pinfunction "1A4_10") (pintype "input"))
    )
    (net (code "459") (name "unconnected-(E104A-1Y4-Pad9)") (class "Default")
      (node (ref "E104") (pin "9") (pinfunction "1Y4_9") (pintype "tri_state"))
    )
    (net (code "460") (name "unconnected-(E104A-2A1-Pad12)") (class "Default")
      (node (ref "E104") (pin "12") (pinfunction "2A1_12") (pintype "input"))
    )
    (net (code "461") (name "unconnected-(E104A-2A2-Pad14)") (class "Default")
      (node (ref "E104") (pin "14") (pinfunction "2A2_14") (pintype "input"))
    )
    (net (code "462") (name "unconnected-(E104A-2G-Pad15)") (class "Default")
      (node (ref "E104") (pin "15") (pinfunction "2G_15") (pintype "input"))
    )
    (net (code "463") (name "unconnected-(E104A-2Y1-Pad11)") (class "Default")
      (node (ref "E104") (pin "11") (pinfunction "2Y1_11") (pintype "tri_state"))
    )
    (net (code "464") (name "unconnected-(E104A-2Y2-Pad13)") (class "Default")
      (node (ref "E104") (pin "13") (pinfunction "2Y2_13") (pintype "tri_state"))
    )
    (net (code "465") (name "unconnected-(E108A-D1-Pad4)") (class "Default")
      (node (ref "E108") (pin "4") (pinfunction "D1_4") (pintype "input"))
    )
    (net (code "466") (name "unconnected-(E108A-D2-Pad5)") (class "Default")
      (node (ref "E108") (pin "5") (pinfunction "D2_5") (pintype "input"))
    )
    (net (code "467") (name "unconnected-(E108A-Q1-Pad2)") (class "Default")
      (node (ref "E108") (pin "2") (pinfunction "Q1_2") (pintype "output"))
    )
    (net (code "468") (name "unconnected-(E108A-Q2-Pad7)") (class "Default")
      (node (ref "E108") (pin "7") (pinfunction "Q2_7") (pintype "output"))
    )
    (net (code "469") (name "unconnected-(E108A-~{Q1}-Pad3)") (class "Default")
      (node (ref "E108") (pin "3") (pinfunction "~{Q1}_3") (pintype "output"))
    )
    (net (code "470") (name "unconnected-(E108A-~{Q2}-Pad6)") (class "Default")
      (node (ref "E108") (pin "6") (pinfunction "~{Q2}_6") (pintype "output"))
    )
    (net (code "471") (name "unconnected-(E109A-O0-Pad18)") (class "Default")
      (node (ref "E109") (pin "18") (pinfunction "O0_18") (pintype "tri_state"))
    )
    (net (code "472") (name "unconnected-(E109A-O1-Pad17)") (class "Default")
      (node (ref "E109") (pin "17") (pinfunction "O1_17") (pintype "tri_state"))
    )
    (net (code "473") (name "unconnected-(E110A-D1-Pad4)") (class "Default")
      (node (ref "E110") (pin "4") (pinfunction "D1_4") (pintype "input"))
    )
    (net (code "474") (name "unconnected-(E110A-D2-Pad5)") (class "Default")
      (node (ref "E110") (pin "5") (pinfunction "D2_5") (pintype "input"))
    )
    (net (code "475") (name "unconnected-(E110A-Q1-Pad2)") (class "Default")
      (node (ref "E110") (pin "2") (pinfunction "Q1_2") (pintype "output"))
    )
    (net (code "476") (name "unconnected-(E110A-Q2-Pad7)") (class "Default")
      (node (ref "E110") (pin "7") (pinfunction "Q2_7") (pintype "output"))
    )
    (net (code "477") (name "unconnected-(E110A-~{Q1}-Pad3)") (class "Default")
      (node (ref "E110") (pin "3") (pinfunction "~{Q1}_3") (pintype "output"))
    )
    (net (code "478") (name "unconnected-(E110A-~{Q2}-Pad6)") (class "Default")
      (node (ref "E110") (pin "6") (pinfunction "~{Q2}_6") (pintype "output"))
    )
    (net (code "479") (name "unconnected-(E111A-O2-Pad10)") (class "Default")
      (node (ref "E111") (pin "10") (pinfunction "O2_10") (pintype "tri_state"))
    )
    (net (code "480") (name "unconnected-(E111A-O3-Pad9)") (class "Default")
      (node (ref "E111") (pin "9") (pinfunction "O3_9") (pintype "tri_state"))
    )
    (net (code "481") (name "unconnected-(E112A-O3-Pad9)") (class "Default")
      (node (ref "E112") (pin "9") (pinfunction "O3_9") (pintype "tri_state"))
    )
    (net (code "482") (name "unconnected-(E113A-O2-Pad10)") (class "Default")
      (node (ref "E113") (pin "10") (pinfunction "O2_10") (pintype "tri_state"))
    )
    (net (code "483") (name "unconnected-(E113A-O3-Pad9)") (class "Default")
      (node (ref "E113") (pin "9") (pinfunction "O3_9") (pintype "tri_state"))
    )
    (net (code "484") (name "unconnected-(E114A-O1-Pad11)") (class "Default")
      (node (ref "E114") (pin "11") (pinfunction "O1_11") (pintype "tri_state"))
    )
    (net (code "485") (name "unconnected-(E114A-O3-Pad9)") (class "Default")
      (node (ref "E114") (pin "9") (pinfunction "O3_9") (pintype "tri_state"))
    )
    (net (code "486") (name "unconnected-(E115F-I-Pad13)") (class "Default")
      (node (ref "E115") (pin "13") (pinfunction "I_13") (pintype "input"))
    )
    (net (code "487") (name "unconnected-(E115F-O-Pad12)") (class "Default")
      (node (ref "E115") (pin "12") (pinfunction "O_12") (pintype "output"))
    )
    (net (code "488") (name "unconnected-(E116A-D1-Pad4)") (class "Default")
      (node (ref "E116") (pin "4") (pinfunction "D1_4") (pintype "input"))
    )
    (net (code "489") (name "unconnected-(E116A-D2-Pad5)") (class "Default")
      (node (ref "E116") (pin "5") (pinfunction "D2_5") (pintype "input"))
    )
    (net (code "490") (name "unconnected-(E116A-Q1-Pad2)") (class "Default")
      (node (ref "E116") (pin "2") (pinfunction "Q1_2") (pintype "output"))
    )
    (net (code "491") (name "unconnected-(E116A-Q2-Pad7)") (class "Default")
      (node (ref "E116") (pin "7") (pinfunction "Q2_7") (pintype "output"))
    )
    (net (code "492") (name "unconnected-(E116A-~{Q1}-Pad3)") (class "Default")
      (node (ref "E116") (pin "3") (pinfunction "~{Q1}_3") (pintype "output"))
    )
    (net (code "493") (name "unconnected-(E116A-~{Q2}-Pad6)") (class "Default")
      (node (ref "E116") (pin "6") (pinfunction "~{Q2}_6") (pintype "output"))
    )
    (net (code "494") (name "unconnected-(E116A-~{Q3}-Pad11)") (class "Default")
      (node (ref "E116") (pin "11") (pinfunction "~{Q3}_11") (pintype "output"))
    )
    (net (code "495") (name "unconnected-(E116A-~{Q4}-Pad14)") (class "Default")
      (node (ref "E116") (pin "14") (pinfunction "~{Q4}_14") (pintype "output"))
    )
    (net (code "496") (name "unconnected-(E117A-Q1-Pad2)") (class "Default")
      (node (ref "E117") (pin "2") (pinfunction "Q1_2") (pintype "output"))
    )
    (net (code "497") (name "unconnected-(E117A-Q2-Pad7)") (class "Default")
      (node (ref "E117") (pin "7") (pinfunction "Q2_7") (pintype "output"))
    )
    (net (code "498") (name "unconnected-(E117A-Q3-Pad10)") (class "Default")
      (node (ref "E117") (pin "10") (pinfunction "Q3_10") (pintype "output"))
    )
    (net (code "499") (name "unconnected-(E117A-Q4-Pad15)") (class "Default")
      (node (ref "E117") (pin "15") (pinfunction "Q4_15") (pintype "output"))
    )
    (net (code "500") (name "~{BREAK_IN_PROG}") (class "Default")
      (node (ref "E4") (pin "13") (pinfunction "O_13") (pintype "open_collector"))
      (node (ref "U$1") (pin "BE2") (pinfunction "1_BE2") (pintype "bidirectional"))
    )
    (net (code "501") (name "~{C0}") (class "Default")
      (node (ref "E19") (pin "13") (pinfunction "O_13") (pintype "open_collector"))
      (node (ref "U$1") (pin "CE1") (pinfunction "1_CE1") (pintype "bidirectional"))
    )
    (net (code "502") (name "~{C1}") (class "Default")
      (node (ref "E19") (pin "10") (pinfunction "O_10") (pintype "open_collector"))
      (node (ref "U$1") (pin "CH1") (pinfunction "1_CH1") (pintype "bidirectional"))
    )
    (net (code "503") (name "~{CPMA_DISABLE}") (class "Default")
      (node (ref "E19") (pin "4") (pinfunction "O_4") (pintype "open_collector"))
      (node (ref "E52") (pin "12") (pinfunction "I1_12") (pintype "input"))
      (node (ref "U$1") (pin "CU1") (pinfunction "1_CU1") (pintype "bidirectional"))
    )
    (net (code "504") (name "~{DATA00}") (class "Default")
      (node (ref "E12") (pin "4") (pinfunction "B3_4") (pintype "bidirectional"))
      (node (ref "U$1") (pin "AR1") (pinfunction "1_AR1") (pintype "bidirectional"))
    )
    (net (code "505") (name "~{DATA01}") (class "Default")
      (node (ref "E12") (pin "1") (pinfunction "B2_1") (pintype "bidirectional"))
      (node (ref "U$1") (pin "AS1") (pinfunction "1_AS1") (pintype "bidirectional"))
    )
    (net (code "506") (name "~{DATA02}") (class "Default")
      (node (ref "E12") (pin "12") (pinfunction "B1_12") (pintype "bidirectional"))
      (node (ref "U$1") (pin "AU1") (pinfunction "1_AU1") (pintype "bidirectional"))
    )
    (net (code "507") (name "~{DATA03}") (class "Default")
      (node (ref "E12") (pin "15") (pinfunction "B0_15") (pintype "bidirectional"))
      (node (ref "U$1") (pin "AV1") (pinfunction "1_AV1") (pintype "bidirectional"))
    )
    (net (code "508") (name "~{DATA04}") (class "Default")
      (node (ref "E13") (pin "4") (pinfunction "B3_4") (pintype "bidirectional"))
      (node (ref "U$1") (pin "BR1") (pinfunction "1_BR1") (pintype "bidirectional"))
    )
    (net (code "509") (name "~{DATA05}") (class "Default")
      (node (ref "E13") (pin "1") (pinfunction "B2_1") (pintype "bidirectional"))
      (node (ref "U$1") (pin "BS1") (pinfunction "1_BS1") (pintype "bidirectional"))
    )
    (net (code "510") (name "~{DATA06}") (class "Default")
      (node (ref "E13") (pin "12") (pinfunction "B1_12") (pintype "bidirectional"))
      (node (ref "U$1") (pin "BU1") (pinfunction "1_BU1") (pintype "bidirectional"))
    )
    (net (code "511") (name "~{DATA07}") (class "Default")
      (node (ref "E13") (pin "15") (pinfunction "B0_15") (pintype "bidirectional"))
      (node (ref "U$1") (pin "BV1") (pinfunction "1_BV1") (pintype "bidirectional"))
    )
    (net (code "512") (name "~{DATA08}") (class "Default")
      (node (ref "E45") (pin "4") (pinfunction "B3_4") (pintype "bidirectional"))
      (node (ref "U$1") (pin "DR1") (pinfunction "1_DR1") (pintype "bidirectional"))
    )
    (net (code "513") (name "~{DATA09}") (class "Default")
      (node (ref "E45") (pin "1") (pinfunction "B2_1") (pintype "bidirectional"))
      (node (ref "U$1") (pin "DS1") (pinfunction "1_DS1") (pintype "bidirectional"))
    )
    (net (code "514") (name "~{DATA10}") (class "Default")
      (node (ref "E45") (pin "12") (pinfunction "B1_12") (pintype "bidirectional"))
      (node (ref "U$1") (pin "DU1") (pinfunction "1_DU1") (pintype "bidirectional"))
    )
    (net (code "515") (name "~{DATA11}") (class "Default")
      (node (ref "E45") (pin "15") (pinfunction "B0_15") (pintype "bidirectional"))
      (node (ref "U$1") (pin "DV1") (pinfunction "1_DV1") (pintype "bidirectional"))
    )
    (net (code "516") (name "~{D}") (class "Default")
      (node (ref "E61") (pin "9") (pinfunction "I0_9") (pintype "input"))
      (node (ref "U$1") (pin "DK2") (pinfunction "1_DK2") (pintype "bidirectional"))
    )
    (net (code "517") (name "~{EMA0}") (class "Default")
      (node (ref "E1") (pin "6") (pinfunction "Q4_6") (pintype "tri_state"))
      (node (ref "E52") (pin "9") (pinfunction "I0_9") (pintype "input"))
      (node (ref "E73") (pin "6") (pinfunction "Q4_6") (pintype "tri_state"))
      (node (ref "U$1") (pin "AH2") (pinfunction "1_AH2") (pintype "bidirectional"))
    )
    (net (code "518") (name "~{EMA1}") (class "Default")
      (node (ref "E1") (pin "5") (pinfunction "Q3_5") (pintype "tri_state"))
      (node (ref "E52") (pin "6") (pinfunction "I0_6") (pintype "input"))
      (node (ref "E73") (pin "5") (pinfunction "Q3_5") (pintype "tri_state"))
      (node (ref "U$1") (pin "AE2") (pinfunction "1_AE2") (pintype "bidirectional"))
    )
    (net (code "519") (name "~{EMA2}") (class "Default")
      (node (ref "E1") (pin "4") (pinfunction "Q2_4") (pintype "tri_state"))
      (node (ref "E52") (pin "4") (pinfunction "I0_4") (pintype "input"))
      (node (ref "E73") (pin "4") (pinfunction "Q2_4") (pintype "tri_state"))
      (node (ref "U$1") (pin "AD2") (pinfunction "1_AD2") (pintype "bidirectional"))
    )
    (net (code "520") (name "~{FORCE_0}") (class "Default")
      (node (ref "E74") (pin "9") (pinfunction "O3_9") (pintype "tri_state"))
      (node (ref "E89") (pin "4") (pinfunction "7_4") (pintype "input"))
    )
    (net (code "521") (name "~{F_SET}") (class "Default")
      (node (ref "E75") (pin "7") (pinfunction "I1_7") (pintype "input"))
      (node (ref "U$1") (pin "DP2") (pinfunction "1_DP2") (pintype "bidirectional"))
    )
    (net (code "522") (name "~{F}") (class "Default")
      (node (ref "E61") (pin "12") (pinfunction "I1_12") (pintype "input"))
      (node (ref "U$1") (pin "DJ2") (pinfunction "1_DJ2") (pintype "bidirectional"))
    )
    (net (code "523") (name "~{IBS}") (class "Default")
      (node (ref "E101") (pin "15") (pinfunction "~{G}_15") (pintype "input"))
      (node (ref "E74") (pin "12") (pinfunction "O0_12") (pintype "tri_state"))
    )
    (net (code "524") (name "~{IND1}") (class "Default")
      (node (ref "E72") (pin "5") (pinfunction "I1_5") (pintype "input"))
      (node (ref "U$1") (pin "CU2") (pinfunction "1_CU2") (pintype "bidirectional"))
    )
    (net (code "525") (name "~{IND2}") (class "Default")
      (node (ref "E72") (pin "7") (pinfunction "I1_7") (pintype "input"))
      (node (ref "U$1") (pin "CV2") (pinfunction "1_CV2") (pintype "bidirectional"))
    )
    (net (code "526") (name "~{INT_IN_PROG}") (class "Default")
      (node (ref "E3") (pin "7") (pinfunction "I1_7") (pintype "input"))
      (node (ref "U$1") (pin "BP2") (pinfunction "1_BP2") (pintype "bidirectional"))
    )
    (net (code "527") (name "~{INT_RQST}") (class "Default")
      (node (ref "E42") (pin "1") (pinfunction "O_1") (pintype "open_collector"))
      (node (ref "E42") (pin "13") (pinfunction "O_13") (pintype "open_collector"))
      (node (ref "U$1") (pin "CP1") (pinfunction "1_CP1") (pintype "bidirectional"))
    )
    (net (code "528") (name "~{IR0}") (class "Default")
      (node (ref "E61") (pin "7") (pinfunction "I1_7") (pintype "input"))
      (node (ref "U$1") (pin "DD2") (pinfunction "1_DD2") (pintype "bidirectional"))
    )
    (net (code "529") (name "~{IR1}") (class "Default")
      (node (ref "E61") (pin "5") (pinfunction "I1_5") (pintype "input"))
      (node (ref "U$1") (pin "DE2") (pinfunction "1_DE2") (pintype "bidirectional"))
    )
    (net (code "530") (name "~{KEY_CONTROL}") (class "Default")
      (node (ref "E51") (pin "9") (pinfunction "I0_9") (pintype "input"))
      (node (ref "U$1") (pin "DU2") (pinfunction "1_DU2") (pintype "bidirectional"))
    )
    (net (code "531") (name "~{LA_EN}") (class "Default")
      (node (ref "E41") (pin "7") (pinfunction "I1_7") (pintype "input"))
      (node (ref "E51") (pin "10") (pinfunction "I1_10") (pintype "input"))
      (node (ref "U$1") (pin "BM2") (pinfunction "1_BM2") (pintype "bidirectional"))
    )
    (net (code "532") (name "~{LINK}") (class "Default")
      (node (ref "E3") (pin "12") (pinfunction "I1_12") (pintype "input"))
      (node (ref "U$1") (pin "AV2") (pinfunction "1_AV2") (pintype "bidirectional"))
    )
    (net (code "533") (name "~{MBCT4}") (class "Default")
      (node (ref "E16") (pin "6") (pinfunction "I3_6") (pintype "input"))
      (node (ref "E33") (pin "2") (pinfunction "I1_2") (pintype "input"))
      (node (ref "E6") (pin "8") (pinfunction "O_8") (pintype "output"))
      (node (ref "E9") (pin "5") (pinfunction "I3_5") (pintype "input"))
    )
    (net (code "534") (name "~{MD00}") (class "Default")
      (node (ref "E11") (pin "7") (pinfunction "I1_7") (pintype "input"))
      (node (ref "U$1") (pin "AK1") (pinfunction "1_AK1") (pintype "bidirectional"))
    )
    (net (code "535") (name "~{MD01}") (class "Default")
      (node (ref "E11") (pin "4") (pinfunction "I0_4") (pintype "input"))
      (node (ref "U$1") (pin "AL1") (pinfunction "1_AL1") (pintype "bidirectional"))
    )
    (net (code "536") (name "~{MD02}") (class "Default")
      (node (ref "E11") (pin "11") (pinfunction "I0_11") (pintype "input"))
      (node (ref "U$1") (pin "AM1") (pinfunction "1_AM1") (pintype "bidirectional"))
    )
    (net (code "537") (name "~{MD03}") (class "Default")
      (node (ref "E11") (pin "10") (pinfunction "I1_10") (pintype "input"))
      (node (ref "U$1") (pin "AP1") (pinfunction "1_AP1") (pintype "bidirectional"))
    )
    (net (code "538") (name "~{MD04}") (class "Default")
      (node (ref "E25") (pin "7") (pinfunction "I1_7") (pintype "input"))
      (node (ref "U$1") (pin "BK1") (pinfunction "1_BK1") (pintype "bidirectional"))
    )
    (net (code "539") (name "~{MD05}") (class "Default")
      (node (ref "E25") (pin "4") (pinfunction "I0_4") (pintype "input"))
      (node (ref "U$1") (pin "BL1") (pinfunction "1_BL1") (pintype "bidirectional"))
    )
    (net (code "540") (name "~{MD06}") (class "Default")
      (node (ref "E25") (pin "11") (pinfunction "I0_11") (pintype "input"))
      (node (ref "U$1") (pin "BM1") (pinfunction "1_BM1") (pintype "bidirectional"))
    )
    (net (code "541") (name "~{MD07}") (class "Default")
      (node (ref "E25") (pin "10") (pinfunction "I1_10") (pintype "input"))
      (node (ref "U$1") (pin "BP1") (pinfunction "1_BP1") (pintype "bidirectional"))
    )
    (net (code "542") (name "~{MD08}") (class "Default")
      (node (ref "E71") (pin "7") (pinfunction "I1_7") (pintype "input"))
      (node (ref "U$1") (pin "DK1") (pinfunction "1_DK1") (pintype "bidirectional"))
    )
    (net (code "543") (name "~{MD09}") (class "Default")
      (node (ref "E71") (pin "4") (pinfunction "I0_4") (pintype "input"))
      (node (ref "U$1") (pin "DL1") (pinfunction "1_DL1") (pintype "bidirectional"))
    )
    (net (code "544") (name "~{MD10}") (class "Default")
      (node (ref "E71") (pin "11") (pinfunction "I0_11") (pintype "input"))
      (node (ref "U$1") (pin "DM1") (pinfunction "1_DM1") (pintype "bidirectional"))
    )
    (net (code "545") (name "~{MD11}") (class "Default")
      (node (ref "E71") (pin "10") (pinfunction "I1_10") (pintype "input"))
      (node (ref "U$1") (pin "DP1") (pinfunction "1_DP1") (pintype "bidirectional"))
    )
    (net (code "546") (name "~{MSIRDIS}") (class "Default")
      (node (ref "E19") (pin "1") (pinfunction "O_1") (pintype "open_collector"))
      (node (ref "U$1") (pin "CV1") (pinfunction "1_CV1") (pintype "bidirectional"))
    )
    (net (code "547") (name "~{P1_ENRF}") (class "Default")
      (node (ref "E111") (pin "13") (pinfunction "~{G}_13") (pintype "input"))
      (node (ref "E112") (pin "13") (pinfunction "~{G}_13") (pintype "input"))
      (node (ref "E114") (pin "13") (pinfunction "~{G}_13") (pintype "input"))
      (node (ref "E27") (pin "5") (pinfunction "I2_5") (pintype "input"))
      (node (ref "E33") (pin "11") (pinfunction "O_11") (pintype "output"))
    )
    (net (code "548") (name "~{P2_BCPMAD}") (class "Default")
      (node (ref "E52") (pin "13") (pinfunction "O_13") (pintype "output"))
      (node (ref "E63") (pin "12") (pinfunction "D_12") (pintype "input"))
      (node (ref "E74") (pin "3") (pinfunction "A4_3") (pintype "input"))
    )
    (net (code "549") (name "~{P2_DFA}") (class "Default")
      (node (ref "E101") (pin "6") (pinfunction "A3_6") (pintype "input"))
      (node (ref "E102") (pin "7") (pinfunction "Q2_7") (pintype "output"))
      (node (ref "E103") (pin "14") (pinfunction "D6_14") (pintype "input"))
      (node (ref "E104") (pin "6") (pinfunction "1A3_6") (pintype "input"))
    )
    (net (code "550") (name "~{P2_DFB}") (class "Default")
      (node (ref "E101") (pin "4") (pinfunction "A2_4") (pintype "input"))
      (node (ref "E102") (pin "10") (pinfunction "Q3_10") (pintype "output"))
      (node (ref "E103") (pin "13") (pinfunction "D5_13") (pintype "input"))
      (node (ref "E104") (pin "4") (pinfunction "1A2_4") (pintype "input"))
    )
    (net (code "551") (name "~{P2_DFC}") (class "Default")
      (node (ref "E101") (pin "2") (pinfunction "A1_2") (pintype "input"))
      (node (ref "E102") (pin "15") (pinfunction "Q4_15") (pintype "output"))
      (node (ref "E103") (pin "11") (pinfunction "D4_11") (pintype "input"))
      (node (ref "E104") (pin "2") (pinfunction "1A1_2") (pintype "input"))
    )
    (net (code "552") (name "~{P2_ELAR}") (class "Default")
      (node (ref "E1") (pin "1") (pinfunction "M_1") (pintype "input"))
      (node (ref "E1") (pin "2") (pinfunction "N_2") (pintype "input"))
      (node (ref "E121") (pin "1") (pinfunction "M_1") (pintype "input"))
      (node (ref "E121") (pin "2") (pinfunction "N_2") (pintype "input"))
      (node (ref "E122") (pin "1") (pinfunction "M_1") (pintype "input"))
      (node (ref "E122") (pin "2") (pinfunction "N_2") (pintype "input"))
      (node (ref "E63") (pin "5") (pinfunction "Q_5") (pintype "output"))
    )
    (net (code "553") (name "~{P2_EMAEN}") (class "Default")
      (node (ref "E63") (pin "8") (pinfunction "~{Q}_8") (pintype "output"))
      (node (ref "E73") (pin "1") (pinfunction "M_1") (pintype "input"))
      (node (ref "E73") (pin "2") (pinfunction "N_2") (pintype "input"))
    )
    (net (code "554") (name "~{P2_ENBS}") (class "Default")
      (node (ref "E118") (pin "2") (pinfunction "N_2") (pintype "input"))
      (node (ref "E119") (pin "2") (pinfunction "N_2") (pintype "input"))
      (node (ref "E63") (pin "6") (pinfunction "~{Q}_6") (pintype "output"))
    )
    (net (code "555") (name "~{P2_IFA}") (class "Default")
      (node (ref "E103") (pin "6") (pinfunction "D3_6") (pintype "input"))
      (node (ref "E83") (pin "2") (pinfunction "A1_2") (pintype "input"))
      (node (ref "E84") (pin "6") (pinfunction "1A3_6") (pintype "input"))
      (node (ref "E93") (pin "7") (pinfunction "Q2_7") (pintype "output"))
    )
    (net (code "556") (name "~{P2_IFB}") (class "Default")
      (node (ref "E103") (pin "4") (pinfunction "D2_4") (pintype "input"))
      (node (ref "E83") (pin "4") (pinfunction "A2_4") (pintype "input"))
      (node (ref "E84") (pin "4") (pinfunction "1A2_4") (pintype "input"))
      (node (ref "E93") (pin "10") (pinfunction "Q3_10") (pintype "output"))
    )
    (net (code "557") (name "~{P2_IFC}") (class "Default")
      (node (ref "E103") (pin "3") (pinfunction "D1_3") (pintype "input"))
      (node (ref "E83") (pin "6") (pinfunction "A3_6") (pintype "input"))
      (node (ref "E84") (pin "2") (pinfunction "1A1_2") (pintype "input"))
      (node (ref "E93") (pin "15") (pinfunction "Q4_15") (pintype "output"))
    )
    (net (code "558") (name "~{P2_INT}") (class "Default")
      (node (ref "E115") (pin "4") (pinfunction "O_4") (pintype "output"))
      (node (ref "E92") (pin "2") (pinfunction "I1_2") (pintype "input"))
    )
    (net (code "559") (name "~{P2_RSB}") (class "Default")
      (node (ref "E100") (pin "1") (pinfunction "1G_1") (pintype "input"))
      (node (ref "E38") (pin "11") (pinfunction "O_11") (pintype "output"))
    )
    (net (code "560") (name "~{P2_RST}") (class "Default")
      (node (ref "E35") (pin "1") (pinfunction "CLR_1") (pintype "input"))
      (node (ref "E46") (pin "1") (pinfunction "CLR_1") (pintype "input"))
      (node (ref "E63") (pin "13") (pinfunction "CLR_13") (pintype "input"))
      (node (ref "E67") (pin "6") (pinfunction "O_6") (pintype "output"))
      (node (ref "E85") (pin "1") (pinfunction "CLR_1") (pintype "input"))
      (node (ref "E88") (pin "1") (pinfunction "CLR_1") (pintype "input"))
    )
    (net (code "561") (name "~{P3_BINIT}") (class "Default")
      (node (ref "E15") (pin "1") (pinfunction "CLR_1") (pintype "input"))
      (node (ref "E17") (pin "1") (pinfunction "CLR_1") (pintype "input"))
      (node (ref "E21") (pin "4") (pinfunction "I1_4") (pintype "input"))
      (node (ref "E22") (pin "4") (pinfunction "O_4") (pintype "output"))
      (node (ref "E32") (pin "10") (pinfunction "PRE_10") (pintype "input"))
    )
    (net (code "562") (name "~{P3_BM0}") (class "Default")
      (node (ref "E29") (pin "2") (pinfunction "I0_2") (pintype "input"))
      (node (ref "E5") (pin "10") (pinfunction "O_10") (pintype "output"))
    )
    (net (code "563") (name "~{P3_BM2}") (class "Default")
      (node (ref "E30") (pin "3") (pinfunction "I2_3") (pintype "input"))
      (node (ref "E5") (pin "12") (pinfunction "O_12") (pintype "output"))
    )
    (net (code "564") (name "~{P3_BM3}") (class "Default")
      (node (ref "E49") (pin "5") (pinfunction "I2_5") (pintype "input"))
      (node (ref "E7") (pin "10") (pinfunction "O_10") (pintype "output"))
    )
    (net (code "565") (name "~{P3_BM4}") (class "Default")
      (node (ref "E36") (pin "9") (pinfunction "I0_9") (pintype "input"))
      (node (ref "E43") (pin "2") (pinfunction "I1_2") (pintype "input"))
      (node (ref "E7") (pin "12") (pinfunction "O_12") (pintype "output"))
    )
    (net (code "566") (name "~{P3_BM9}") (class "Default")
      (node (ref "E36") (pin "2") (pinfunction "I1_2") (pintype "input"))
      (node (ref "E44") (pin "10") (pinfunction "O_10") (pintype "output"))
    )
    (net (code "567") (name "~{P3_BM11}") (class "Default")
      (node (ref "E36") (pin "4") (pinfunction "I2_4") (pintype "input"))
      (node (ref "E43") (pin "1") (pinfunction "I0_1") (pintype "input"))
      (node (ref "E44") (pin "12") (pinfunction "O_12") (pintype "output"))
    )
    (net (code "568") (name "~{P3_BTP2}") (class "Default")
      (node (ref "E22") (pin "2") (pinfunction "O_2") (pintype "output"))
      (node (ref "E54") (pin "13") (pinfunction "I1_13") (pintype "input"))
    )
    (net (code "569") (name "~{P3_BTP3}") (class "Default")
      (node (ref "E26") (pin "13") (pinfunction "1C,2C_13") (pintype "input"))
      (node (ref "E29") (pin "11") (pinfunction "I0_11") (pintype "input"))
      (node (ref "E38") (pin "1") (pinfunction "I0_1") (pintype "input"))
      (node (ref "E38") (pin "2") (pinfunction "I1_2") (pintype "input"))
      (node (ref "E47") (pin "11") (pinfunction "I0_11") (pintype "input"))
      (node (ref "E48") (pin "6") (pinfunction "I1_6") (pintype "input"))
      (node (ref "E51") (pin "2") (pinfunction "O_2") (pintype "output"))
    )
    (net (code "570") (name "~{P3_C17EN}") (class "Default")
      (node (ref "E14") (pin "13") (pinfunction "O4_13") (pintype "tri_state"))
      (node (ref "E34") (pin "12") (pinfunction "D_12") (pintype "input"))
    )
    (net (code "571") (name "~{P3_CFROM}") (class "Default")
      (node (ref "E14") (pin "12") (pinfunction "O5_12") (pintype "tri_state"))
      (node (ref "E28") (pin "13") (pinfunction "~{G1}_13") (pintype "input"))
    )
    (net (code "572") (name "~{P3_DECEN}") (class "Default")
      (node (ref "E14") (pin "11") (pinfunction "O6_11") (pintype "tri_state"))
      (node (ref "E31") (pin "18") (pinfunction "G1_18") (pintype "input"))
      (node (ref "E47") (pin "2") (pinfunction "I0_2") (pintype "input"))
    )
    (net (code "573") (name "~{P3_E2CFROM}") (class "Default")
      (node (ref "E26") (pin "15") (pinfunction "2Q_15") (pintype "output"))
      (node (ref "E28") (pin "14") (pinfunction "~{G2}_14") (pintype "input"))
    )
    (net (code "574") (name "~{P3_HOS}") (class "Default")
      (node (ref "E14") (pin "15") (pinfunction "O3_15") (pintype "tri_state"))
      (node (ref "E24") (pin "2") (pinfunction "I1_2") (pintype "input"))
    )
    (net (code "575") (name "~{P4_BLBM}") (class "Default")
      (node (ref "E26") (pin "8") (pinfunction "~{2Q}_8") (pintype "output"))
      (node (ref "E82") (pin "3") (pinfunction "WE_3") (pintype "input"))
    )
    (net (code "576") (name "~{P4_CDF}") (class "Default")
      (node (ref "E28") (pin "9") (pinfunction "O3_9") (pintype "tri_state"))
      (node (ref "E70") (pin "10") (pinfunction "I1_10") (pintype "input"))
      (node (ref "E80") (pin "12") (pinfunction "A2_12") (pintype "input"))
      (node (ref "E89") (pin "1") (pinfunction "4_1") (pintype "input"))
      (node (ref "R17") (pin "1") (pinfunction "1_1") (pintype "passive"))
    )
    (net (code "577") (name "~{P4_CIF}") (class "Default")
      (node (ref "E28") (pin "10") (pinfunction "O2_10") (pintype "tri_state"))
      (node (ref "E70") (pin "9") (pinfunction "I0_9") (pintype "input"))
      (node (ref "E80") (pin "11") (pinfunction "A1_11") (pintype "input"))
      (node (ref "E89") (pin "2") (pinfunction "5_2") (pintype "input"))
      (node (ref "R16") (pin "1") (pinfunction "1_1") (pintype "passive"))
    )
    (net (code "578") (name "~{P4_CINT}") (class "Default")
      (node (ref "E31") (pin "9") (pinfunction "8_9") (pintype "output"))
      (node (ref "E33") (pin "5") (pinfunction "I1_5") (pintype "input"))
    )
    (net (code "579") (name "~{P4_CUF}") (class "Default")
      (node (ref "E22") (pin "11") (pinfunction "I_11") (pintype "input"))
      (node (ref "E31") (pin "16") (pinfunction "14_16") (pintype "output"))
    )
    (net (code "580") (name "~{P4_CUMB}") (class "Default")
      (node (ref "E33") (pin "8") (pinfunction "O_8") (pintype "output"))
      (node (ref "E59") (pin "10") (pinfunction "PRE_10") (pintype "input"))
      (node (ref "E60") (pin "1") (pinfunction "CLR_1") (pintype "input"))
    )
    (net (code "581") (name "~{P4_DFEN}") (class "Default")
      (node (ref "E76") (pin "9") (pinfunction "Q_9") (pintype "output"))
      (node (ref "E92") (pin "13") (pinfunction "I2_13") (pintype "input"))
    )
    (net (code "582") (name "~{P4_FATAL}") (class "Default")
      (node (ref "E32") (pin "1") (pinfunction "CLR_1") (pintype "input"))
      (node (ref "E38") (pin "6") (pinfunction "O_6") (pintype "output"))
      (node (ref "E4") (pin "6") (pinfunction "I1_6") (pintype "input"))
    )
    (net (code "583") (name "~{P4_GTF}") (class "Default")
      (node (ref "E18") (pin "12") (pinfunction "I0_12") (pintype "input"))
      (node (ref "E18") (pin "13") (pinfunction "I1_13") (pintype "input"))
      (node (ref "E38") (pin "12") (pinfunction "I0_12") (pintype "input"))
      (node (ref "E43") (pin "6") (pinfunction "O_6") (pintype "output"))
      (node (ref "E56") (pin "3") (pinfunction "I0_3") (pintype "input"))
      (node (ref "E6") (pin "12") (pinfunction "I0_12") (pintype "input"))
    )
    (net (code "584") (name "~{P4_GTS}") (class "Default")
      (node (ref "E31") (pin "2") (pinfunction "1_2") (pintype "output"))
      (node (ref "E56") (pin "5") (pinfunction "I2_5") (pintype "input"))
      (node (ref "E6") (pin "13") (pinfunction "I1_13") (pintype "input"))
    )
    (net (code "585") (name "~{P4_INIT_EN}") (class "Default")
      (node (ref "E74") (pin "2") (pinfunction "A5_2") (pintype "input"))
      (node (ref "E76") (pin "5") (pinfunction "Q_5") (pintype "output"))
    )
    (net (code "586") (name "~{P4_INT_INH}") (class "Default")
      (node (ref "E48") (pin "3") (pinfunction "I1_3") (pintype "input"))
      (node (ref "E57") (pin "12") (pinfunction "I0_12") (pintype "input"))
      (node (ref "E9") (pin "8") (pinfunction "O_8") (pintype "output"))
    )
    (net (code "587") (name "~{P4_INT_IN_PROG}") (class "Default")
      (node (ref "E4") (pin "4") (pinfunction "O_4") (pintype "open_collector"))
      (node (ref "E74") (pin "15") (pinfunction "A7_15") (pintype "input"))
    )
    (net (code "588") (name "~{P4_LBM}") (class "Default")
      (node (ref "E29") (pin "9") (pinfunction "I1_9") (pintype "input"))
      (node (ref "E34") (pin "1") (pinfunction "O0_1") (pintype "output"))
      (node (ref "E81") (pin "23") (pinfunction "I12_23") (pintype "input"))
    )
    (net (code "589") (name "~{P4_LET_IO}") (class "Default")
      (node (ref "E24") (pin "11") (pinfunction "I2_11") (pintype "input"))
      (node (ref "E28") (pin "12") (pinfunction "O0_12") (pintype "tri_state"))
      (node (ref "E30") (pin "5") (pinfunction "I4_5") (pintype "input"))
      (node (ref "E30") (pin "6") (pinfunction "I5_6") (pintype "input"))
      (node (ref "E64") (pin "5") (pinfunction "I0_5") (pintype "input"))
      (node (ref "E95") (pin "1") (pinfunction "1G_1") (pintype "input"))
      (node (ref "E95") (pin "15") (pinfunction "2G_15") (pintype "input"))
      (node (ref "R14") (pin "1") (pinfunction "1_1") (pintype "passive"))
    )
    (net (code "590") (name "~{P4_LRR}") (class "Default")
      (node (ref "E31") (pin "5") (pinfunction "4_5") (pintype "output"))
      (node (ref "E47") (pin "12") (pinfunction "I1_12") (pintype "input"))
    )
    (net (code "591") (name "~{P4_LUSR}") (class "Default")
      (node (ref "E29") (pin "12") (pinfunction "I1_12") (pintype "input"))
      (node (ref "E31") (pin "7") (pinfunction "6_7") (pintype "output"))
    )
    (net (code "592") (name "~{P4_LXM}") (class "Default")
      (node (ref "E24") (pin "9") (pinfunction "I0_9") (pintype "input"))
      (node (ref "E36") (pin "6") (pinfunction "O_6") (pintype "output"))
      (node (ref "E48") (pin "5") (pinfunction "I0_5") (pintype "input"))
    )
    (net (code "593") (name "~{P4_MBC}") (class "Default")
      (node (ref "E22") (pin "5") (pinfunction "I_5") (pintype "input"))
      (node (ref "E34") (pin "5") (pinfunction "O4_5") (pintype "output"))
    )
    (net (code "594") (name "~{P4_PCLR}") (class "Default")
      (node (ref "E49") (pin "2") (pinfunction "I1_2") (pintype "input"))
      (node (ref "E63") (pin "4") (pinfunction "PRE_4") (pintype "input"))
      (node (ref "E65") (pin "4") (pinfunction "PRE_4") (pintype "input"))
      (node (ref "E67") (pin "5") (pinfunction "I1_5") (pintype "input"))
      (node (ref "E76") (pin "3") (pinfunction "CLK_3") (pintype "input"))
      (node (ref "E77") (pin "4") (pinfunction "~{Q}_4") (pintype "output"))
    )
    (net (code "595") (name "~{P4_PLXA}") (class "Default")
      (node (ref "E49") (pin "13") (pinfunction "I2_13") (pintype "input"))
      (node (ref "E57") (pin "6") (pinfunction "O_6") (pintype "output"))
      (node (ref "E58") (pin "1") (pinfunction "I_1") (pintype "input"))
      (node (ref "E63") (pin "1") (pinfunction "CLR_1") (pintype "input"))
      (node (ref "E67") (pin "4") (pinfunction "I0_4") (pintype "input"))
    )
    (net (code "596") (name "~{P4_RACA}") (class "Default")
      (node (ref "E16") (pin "7") (pinfunction "I2_7") (pintype "input"))
      (node (ref "E23") (pin "1") (pinfunction "~{A}/B_1") (pintype "input"))
      (node (ref "E33") (pin "1") (pinfunction "I0_1") (pintype "input"))
      (node (ref "E34") (pin "6") (pinfunction "O5_6") (pintype "output"))
      (node (ref "E9") (pin "1") (pinfunction "I0_1") (pintype "input"))
    )
    (net (code "597") (name "~{P4_RACB}") (class "Default")
      (node (ref "E16") (pin "8") (pinfunction "I1_8") (pintype "input"))
      (node (ref "E34") (pin "7") (pinfunction "O6_7") (pintype "output"))
      (node (ref "E9") (pin "2") (pinfunction "I1_2") (pintype "input"))
    )
    (net (code "598") (name "~{P4_RACC}") (class "Default")
      (node (ref "E16") (pin "9") (pinfunction "I0_9") (pintype "input"))
      (node (ref "E34") (pin "9") (pinfunction "O7_9") (pintype "output"))
      (node (ref "E9") (pin "4") (pinfunction "I2_4") (pintype "input"))
    )
    (net (code "599") (name "~{P4_RBM}") (class "Default")
      (node (ref "E100") (pin "15") (pinfunction "2G_15") (pintype "input"))
      (node (ref "E34") (pin "2") (pinfunction "O1_2") (pintype "output"))
      (node (ref "E81") (pin "22") (pinfunction "I13_22") (pintype "input"))
    )
    (net (code "600") (name "~{P4_RDF}") (class "Default")
      (node (ref "E111") (pin "15") (pinfunction "A7_15") (pintype "input"))
      (node (ref "E112") (pin "15") (pinfunction "A7_15") (pintype "input"))
      (node (ref "E114") (pin "15") (pinfunction "A7_15") (pintype "input"))
      (node (ref "E31") (pin "10") (pinfunction "9_10") (pintype "output"))
      (node (ref "E33") (pin "13") (pinfunction "I1_13") (pintype "input"))
    )
    (net (code "601") (name "~{P4_RIB}") (class "Default")
      (node (ref "E31") (pin "13") (pinfunction "11_13") (pintype "output"))
      (node (ref "E56") (pin "4") (pinfunction "I1_4") (pintype "input"))
    )
    (net (code "602") (name "~{P4_RIF}") (class "Default")
      (node (ref "E31") (pin "11") (pinfunction "10_11") (pintype "output"))
      (node (ref "E33") (pin "12") (pinfunction "I0_12") (pintype "input"))
    )
    (net (code "603") (name "~{P4_RLB}") (class "Default")
      (node (ref "E34") (pin "3") (pinfunction "O2_3") (pintype "output"))
      (node (ref "E90") (pin "1") (pinfunction "M_1") (pintype "input"))
      (node (ref "E90") (pin "2") (pinfunction "N_2") (pintype "input"))
    )
    (net (code "604") (name "~{P4_RMF}") (class "Default")
      (node (ref "E107") (pin "1") (pinfunction "1G_1") (pintype "input"))
      (node (ref "E107") (pin "15") (pinfunction "2G_15") (pintype "input"))
      (node (ref "E31") (pin "14") (pinfunction "12_14") (pintype "output"))
      (node (ref "E39") (pin "1") (pinfunction "I_1") (pintype "input"))
      (node (ref "E50") (pin "9") (pinfunction "I0_9") (pintype "input"))
      (node (ref "E70") (pin "13") (pinfunction "I1_13") (pintype "input"))
      (node (ref "E89") (pin "11") (pinfunction "1_11") (pintype "input"))
    )
    (net (code "605") (name "~{P4_RMR}") (class "Default")
      (node (ref "E34") (pin "4") (pinfunction "O3_4") (pintype "output"))
      (node (ref "E62") (pin "1") (pinfunction "M_1") (pintype "input"))
      (node (ref "E62") (pin "2") (pinfunction "N_2") (pintype "input"))
      (node (ref "E98") (pin "1") (pinfunction "M_1") (pintype "input"))
      (node (ref "E98") (pin "2") (pinfunction "N_2") (pintype "input"))
      (node (ref "E99") (pin "1") (pinfunction "M_1") (pintype "input"))
      (node (ref "E99") (pin "2") (pinfunction "N_2") (pintype "input"))
    )
    (net (code "606") (name "~{P4_RRR}") (class "Default")
      (node (ref "E31") (pin "6") (pinfunction "5_6") (pintype "output"))
      (node (ref "E86") (pin "1") (pinfunction "1G_1") (pintype "input"))
      (node (ref "E86") (pin "15") (pinfunction "2G_15") (pintype "input"))
    )
    (net (code "607") (name "~{P4_RTF}") (class "Default")
      (node (ref "E36") (pin "8") (pinfunction "O_8") (pintype "output"))
      (node (ref "E38") (pin "9") (pinfunction "I0_9") (pintype "input"))
      (node (ref "E80") (pin "14") (pinfunction "A4_14") (pintype "input"))
    )
    (net (code "608") (name "~{P4_RTS}") (class "Default")
      (node (ref "E31") (pin "3") (pinfunction "2_3") (pintype "output"))
      (node (ref "E38") (pin "10") (pinfunction "I1_10") (pintype "input"))
      (node (ref "E70") (pin "12") (pinfunction "I0_12") (pintype "input"))
      (node (ref "E89") (pin "12") (pinfunction "2_12") (pintype "input"))
    )
    (net (code "609") (name "~{P4_RUSR}") (class "Default")
      (node (ref "E106") (pin "1") (pinfunction "1G_1") (pintype "input"))
      (node (ref "E106") (pin "15") (pinfunction "2G_15") (pintype "input"))
      (node (ref "E31") (pin "8") (pinfunction "7_8") (pintype "output"))
    )
    (net (code "610") (name "~{P4_RXM}") (class "Default")
      (node (ref "E31") (pin "4") (pinfunction "3_4") (pintype "output"))
      (node (ref "E37") (pin "1") (pinfunction "1G_1") (pintype "input"))
      (node (ref "E37") (pin "15") (pinfunction "2G_15") (pintype "input"))
      (node (ref "E55") (pin "15") (pinfunction "2G_15") (pintype "input"))
    )
    (net (code "611") (name "~{P4_SINT}") (class "Default")
      (node (ref "E22") (pin "13") (pinfunction "I_13") (pintype "input"))
      (node (ref "E31") (pin "15") (pinfunction "13_15") (pintype "output"))
    )
    (net (code "612") (name "~{P4_SUF}") (class "Default")
      (node (ref "E31") (pin "17") (pinfunction "15_17") (pintype "output"))
      (node (ref "E39") (pin "3") (pinfunction "I_3") (pintype "input"))
      (node (ref "E67") (pin "2") (pinfunction "I1_2") (pintype "input"))
    )
    (net (code "613") (name "~{P4_USINT}") (class "Default")
      (node (ref "E24") (pin "4") (pinfunction "I1_4") (pintype "input"))
      (node (ref "E32") (pin "9") (pinfunction "Q_9") (pintype "output"))
    )
    (net (code "614") (name "~{P5_BMEN}") (class "Default")
      (node (ref "E54") (pin "2") (pinfunction "I1_2") (pintype "input"))
      (node (ref "E74") (pin "10") (pinfunction "O2_10") (pintype "tri_state"))
      (node (ref "E82") (pin "2") (pinfunction "CS_2") (pintype "input"))
      (node (ref "E90") (pin "10") (pinfunction "G2_10") (pintype "input"))
      (node (ref "E90") (pin "9") (pinfunction "G1_9") (pintype "input"))
    )
    (net (code "615") (name "~{P5_DBS}") (class "Default")
      (node (ref "E54") (pin "1") (pinfunction "I0_1") (pintype "input"))
      (node (ref "E74") (pin "11") (pinfunction "O1_11") (pintype "tri_state"))
      (node (ref "E91") (pin "15") (pinfunction "2G_15") (pintype "input"))
    )
    (net (code "616") (name "~{P5_IBS0}") (class "Default")
      (node (ref "E118") (pin "11") (pinfunction "D4_11") (pintype "input"))
      (node (ref "E119") (pin "11") (pinfunction "D4_11") (pintype "input"))
      (node (ref "E120") (pin "7") (pinfunction "Y3_7") (pintype "output"))
    )
    (net (code "617") (name "~{P5_IBS1}") (class "Default")
      (node (ref "E118") (pin "12") (pinfunction "D3_12") (pintype "input"))
      (node (ref "E119") (pin "12") (pinfunction "D3_12") (pintype "input"))
      (node (ref "E120") (pin "6") (pinfunction "Y2_6") (pintype "output"))
    )
    (net (code "618") (name "~{P5_IBS2}") (class "Default")
      (node (ref "E118") (pin "13") (pinfunction "D2_13") (pintype "input"))
      (node (ref "E119") (pin "13") (pinfunction "D2_13") (pintype "input"))
      (node (ref "E120") (pin "5") (pinfunction "Y1_5") (pintype "output"))
    )
    (net (code "619") (name "~{P5_IBS3}") (class "Default")
      (node (ref "E118") (pin "14") (pinfunction "D1_14") (pintype "input"))
      (node (ref "E119") (pin "14") (pinfunction "D1_14") (pintype "input"))
      (node (ref "E120") (pin "4") (pinfunction "Y0_4") (pintype "output"))
    )
    (net (code "620") (name "~{P6_BS0}") (class "Default")
      (node (ref "E118") (pin "6") (pinfunction "Q4_6") (pintype "tri_state"))
      (node (ref "E121") (pin "6") (pinfunction "Q4_6") (pintype "tri_state"))
      (node (ref "E55") (pin "7") (pinfunction "1Y3_7") (pintype "tri_state"))
      (node (ref "E55") (pin "9") (pinfunction "1Y4_9") (pintype "tri_state"))
      (node (ref "E98") (pin "11") (pinfunction "D4_11") (pintype "input"))
      (node (ref "U$1") (pin "EB2") (pinfunction "1_EB2") (pintype "bidirectional"))
    )
    (net (code "621") (name "~{P6_BS1}") (class "Default")
      (node (ref "E118") (pin "5") (pinfunction "Q3_5") (pintype "tri_state"))
      (node (ref "E121") (pin "5") (pinfunction "Q3_5") (pintype "tri_state"))
      (node (ref "E98") (pin "12") (pinfunction "D3_12") (pintype "input"))
      (node (ref "U$1") (pin "ED2") (pinfunction "1_ED2") (pintype "bidirectional"))
    )
    (net (code "622") (name "~{P6_BS2}") (class "Default")
      (node (ref "E118") (pin "4") (pinfunction "Q2_4") (pintype "tri_state"))
      (node (ref "E121") (pin "4") (pinfunction "Q2_4") (pintype "tri_state"))
      (node (ref "E98") (pin "13") (pinfunction "D2_13") (pintype "input"))
      (node (ref "U$1") (pin "EL2") (pinfunction "1_EL2") (pintype "bidirectional"))
    )
    (net (code "623") (name "~{P6_BS3}") (class "Default")
      (node (ref "E118") (pin "3") (pinfunction "Q1_3") (pintype "tri_state"))
      (node (ref "E121") (pin "3") (pinfunction "Q1_3") (pintype "tri_state"))
      (node (ref "E98") (pin "14") (pinfunction "D1_14") (pintype "input"))
      (node (ref "U$1") (pin "EP2") (pinfunction "1_EP2") (pintype "bidirectional"))
    )
    (net (code "624") (name "~{P6_CKMR}") (class "Default")
      (node (ref "E54") (pin "8") (pinfunction "O_8") (pintype "output"))
      (node (ref "E62") (pin "7") (pinfunction "CLK_7") (pintype "input"))
      (node (ref "E98") (pin "7") (pinfunction "CLK_7") (pintype "input"))
      (node (ref "E99") (pin "7") (pinfunction "CLK_7") (pintype "input"))
    )
    (net (code "625") (name "~{P6_DIOI}") (class "Default")
      (node (ref "E27") (pin "3") (pinfunction "I0_3") (pintype "input"))
      (node (ref "E27") (pin "4") (pinfunction "I1_4") (pintype "input"))
      (node (ref "E30") (pin "4") (pinfunction "I3_4") (pintype "input"))
      (node (ref "E37") (pin "6") (pinfunction "1A3_6") (pintype "input"))
      (node (ref "E46") (pin "14") (pinfunction "~{Q4}_14") (pintype "output"))
    )
    (net (code "626") (name "~{P6_DISF}") (class "Default")
      (node (ref "E101") (pin "1") (pinfunction "~{G}_1") (pintype "input"))
      (node (ref "E83") (pin "1") (pinfunction "~{G}_1") (pintype "input"))
      (node (ref "E94") (pin "3") (pinfunction "O_3") (pintype "output"))
    )
    (net (code "627") (name "~{P6_DISPB}") (class "Default")
      (node (ref "E91") (pin "1") (pinfunction "1G_1") (pintype "input"))
      (node (ref "E92") (pin "6") (pinfunction "O_6") (pintype "output"))
    )
    (net (code "628") (name "~{P6_EBM}") (class "Default")
      (node (ref "E37") (pin "4") (pinfunction "1A2_4") (pintype "input"))
      (node (ref "E46") (pin "11") (pinfunction "~{Q3}_11") (pintype "output"))
    )
    (net (code "629") (name "~{P6_EEM}") (class "Default")
      (node (ref "E35") (pin "14") (pinfunction "~{Q4}_14") (pintype "output"))
      (node (ref "E55") (pin "12") (pinfunction "2A1_12") (pintype "input"))
    )
    (net (code "630") (name "~{P6_EN5}") (class "Default")
      (node (ref "E35") (pin "11") (pinfunction "~{Q3}_11") (pintype "output"))
      (node (ref "E37") (pin "14") (pinfunction "2A2_14") (pintype "input"))
    )
    (net (code "631") (name "~{P6_EN9}") (class "Default")
      (node (ref "E35") (pin "6") (pinfunction "~{Q2}_6") (pintype "output"))
      (node (ref "E37") (pin "12") (pinfunction "2A1_12") (pintype "input"))
    )
    (net (code "632") (name "~{P6_MAINT}") (class "Default")
      (node (ref "E37") (pin "2") (pinfunction "1A1_2") (pintype "input"))
      (node (ref "E46") (pin "6") (pinfunction "~{Q2}_6") (pintype "output"))
      (node (ref "E48") (pin "2") (pinfunction "I0_2") (pintype "input"))
    )
    (net (code "633") (name "~{P6_PRUP}") (class "Default")
      (node (ref "E118") (pin "1") (pinfunction "M_1") (pintype "input"))
      (node (ref "E119") (pin "1") (pinfunction "M_1") (pintype "input"))
      (node (ref "E65") (pin "5") (pinfunction "Q_5") (pintype "output"))
    )
    (net (code "634") (name "~{P6_RVFEN}") (class "Default")
      (node (ref "E35") (pin "3") (pinfunction "~{Q1}_3") (pintype "output"))
      (node (ref "E37") (pin "10") (pinfunction "1A4_10") (pintype "input"))
    )
    (net (code "635") (name "~{P6_USM}") (class "Default")
      (node (ref "E59") (pin "2") (pinfunction "D_2") (pintype "input"))
      (node (ref "E59") (pin "9") (pinfunction "Q_9") (pintype "output"))
      (node (ref "E83") (pin "14") (pinfunction "A2_14") (pintype "input"))
    )
    (net (code "636") (name "~{PAUSE}") (class "Default")
      (node (ref "D1") (pin "C") (pinfunction "C_C") (pintype "passive"))
      (node (ref "E41") (pin "4") (pinfunction "I0_4") (pintype "input"))
      (node (ref "Q1") (pin "3") (pinfunction "C_3") (pintype "passive"))
      (node (ref "U$1") (pin "CD1") (pinfunction "1_CD1") (pintype "bidirectional"))
    )
    (net (code "637") (name "~{POWER_OK}") (class "Default")
      (node (ref "E41") (pin "9") (pinfunction "I0_9") (pintype "input"))
      (node (ref "U$1") (pin "BV2") (pinfunction "1_BV2") (pintype "bidirectional"))
    )
    (net (code "638") (name "~{RBS0}") (class "Default")
      (node (ref "E119") (pin "6") (pinfunction "Q4_6") (pintype "tri_state"))
      (node (ref "E122") (pin "6") (pinfunction "Q4_6") (pintype "tri_state"))
      (node (ref "E55") (pin "3") (pinfunction "1Y1_3") (pintype "tri_state"))
      (node (ref "E55") (pin "5") (pinfunction "1Y2_5") (pintype "tri_state"))
      (node (ref "E99") (pin "14") (pinfunction "D1_14") (pintype "input"))
      (node (ref "J1") (pin "1") (pinfunction "1_1") (pintype "passive"))
      (node (ref "R11") (pin "1") (pinfunction "1_1") (pintype "passive"))
    )
    (net (code "639") (name "~{RBS1}") (class "Default")
      (node (ref "E119") (pin "5") (pinfunction "Q3_5") (pintype "tri_state"))
      (node (ref "E122") (pin "5") (pinfunction "Q3_5") (pintype "tri_state"))
      (node (ref "E99") (pin "13") (pinfunction "D2_13") (pintype "input"))
      (node (ref "J1") (pin "3") (pinfunction "3_3") (pintype "passive"))
      (node (ref "R39") (pin "1") (pinfunction "1_1") (pintype "passive"))
    )
    (net (code "640") (name "~{RBS2}") (class "Default")
      (node (ref "E119") (pin "4") (pinfunction "Q2_4") (pintype "tri_state"))
      (node (ref "E122") (pin "4") (pinfunction "Q2_4") (pintype "tri_state"))
      (node (ref "E99") (pin "12") (pinfunction "D3_12") (pintype "input"))
      (node (ref "J1") (pin "5") (pinfunction "5_5") (pintype "passive"))
      (node (ref "R38") (pin "1") (pinfunction "1_1") (pintype "passive"))
    )
    (net (code "641") (name "~{RBS3}") (class "Default")
      (node (ref "E119") (pin "3") (pinfunction "Q1_3") (pintype "tri_state"))
      (node (ref "E122") (pin "3") (pinfunction "Q1_3") (pintype "tri_state"))
      (node (ref "E99") (pin "11") (pinfunction "D4_11") (pintype "input"))
      (node (ref "J1") (pin "7") (pinfunction "7_7") (pintype "passive"))
      (node (ref "R37") (pin "1") (pinfunction "1_1") (pintype "passive"))
    )
    (net (code "642") (name "~{RD0}") (class "Default")
      (node (ref "E16") (pin "10") (pinfunction "O7_10") (pintype "tri_state"))
      (node (ref "E4") (pin "10") (pinfunction "O_10") (pintype "open_collector"))
      (node (ref "E5") (pin "1") (pinfunction "I_1") (pintype "input"))
      (node (ref "E55") (pin "11") (pinfunction "2Y1_11") (pintype "tri_state"))
      (node (ref "R12") (pin "2") (pinfunction "2_2") (pintype "passive"))
    )
    (net (code "643") (name "~{RD1}") (class "Default")
      (node (ref "E100") (pin "3") (pinfunction "1Y1_3") (pintype "tri_state"))
      (node (ref "E16") (pin "11") (pinfunction "O6_11") (pintype "tri_state"))
      (node (ref "E37") (pin "13") (pinfunction "2Y2_13") (pintype "tri_state"))
      (node (ref "E5") (pin "3") (pinfunction "I_3") (pintype "input"))
      (node (ref "E91") (pin "3") (pinfunction "1Y1_3") (pintype "tri_state"))
      (node (ref "E99") (pin "3") (pinfunction "Q1_3") (pintype "tri_state"))
      (node (ref "R9") (pin "2") (pinfunction "2_2") (pintype "passive"))
    )
    (net (code "644") (name "~{RD2}") (class "Default")
      (node (ref "E100") (pin "5") (pinfunction "1Y2_5") (pintype "tri_state"))
      (node (ref "E16") (pin "12") (pinfunction "O5_12") (pintype "tri_state"))
      (node (ref "E37") (pin "11") (pinfunction "2Y1_11") (pintype "tri_state"))
      (node (ref "E5") (pin "5") (pinfunction "I_5") (pintype "input"))
      (node (ref "E91") (pin "5") (pinfunction "1Y2_5") (pintype "tri_state"))
      (node (ref "E99") (pin "4") (pinfunction "Q2_4") (pintype "tri_state"))
      (node (ref "R8") (pin "2") (pinfunction "2_2") (pintype "passive"))
    )
    (net (code "645") (name "~{RD3}") (class "Default")
      (node (ref "E100") (pin "7") (pinfunction "1Y3_7") (pintype "tri_state"))
      (node (ref "E23") (pin "4") (pinfunction "1Y_4") (pintype "tri_state"))
      (node (ref "E37") (pin "9") (pinfunction "1Y4_9") (pintype "tri_state"))
      (node (ref "E5") (pin "9") (pinfunction "I_9") (pintype "input"))
      (node (ref "E8") (pin "13") (pinfunction "O_13") (pintype "open_collector"))
      (node (ref "E83") (pin "11") (pinfunction "Y1_11") (pintype "tri_state"))
      (node (ref "E99") (pin "5") (pinfunction "Q3_5") (pintype "tri_state"))
      (node (ref "R2") (pin "2") (pinfunction "2_2") (pintype "passive"))
    )
    (net (code "646") (name "~{RD4}") (class "Default")
      (node (ref "E100") (pin "9") (pinfunction "1Y4_9") (pintype "tri_state"))
      (node (ref "E23") (pin "7") (pinfunction "2Y_7") (pintype "tri_state"))
      (node (ref "E37") (pin "7") (pinfunction "1Y3_7") (pintype "tri_state"))
      (node (ref "E7") (pin "1") (pinfunction "I_1") (pintype "input"))
      (node (ref "E91") (pin "7") (pinfunction "1Y3_7") (pintype "tri_state"))
      (node (ref "E99") (pin "6") (pinfunction "Q4_6") (pintype "tri_state"))
      (node (ref "R1") (pin "2") (pinfunction "2_2") (pintype "passive"))
    )
    (net (code "647") (name "~{RD5}") (class "Default")
      (node (ref "E111") (pin "11") (pinfunction "O1_11") (pintype "tri_state"))
      (node (ref "E16") (pin "13") (pinfunction "O4_13") (pintype "tri_state"))
      (node (ref "E37") (pin "5") (pinfunction "1Y2_5") (pintype "tri_state"))
      (node (ref "E7") (pin "3") (pinfunction "I_3") (pintype "input"))
      (node (ref "E8") (pin "10") (pinfunction "O_10") (pintype "open_collector"))
      (node (ref "E83") (pin "13") (pinfunction "Y2_13") (pintype "tri_state"))
      (node (ref "E91") (pin "9") (pinfunction "1Y4_9") (pintype "tri_state"))
      (node (ref "E98") (pin "6") (pinfunction "Q4_6") (pintype "tri_state"))
      (node (ref "R6") (pin "2") (pinfunction "2_2") (pintype "passive"))
    )
    (net (code "648") (name "~{RD6}") (class "Default")
      (node (ref "E105") (pin "13") (pinfunction "2Y2_13") (pintype "tri_state"))
      (node (ref "E106") (pin "3") (pinfunction "1Y1_3") (pintype "tri_state"))
      (node (ref "E114") (pin "12") (pinfunction "O0_12") (pintype "tri_state"))
      (node (ref "E16") (pin "15") (pinfunction "O3_15") (pintype "tri_state"))
      (node (ref "E37") (pin "3") (pinfunction "1Y1_3") (pintype "tri_state"))
      (node (ref "E7") (pin "5") (pinfunction "I_5") (pintype "input"))
      (node (ref "E83") (pin "7") (pinfunction "Y3_7") (pintype "tri_state"))
      (node (ref "E90") (pin "3") (pinfunction "Q1_3") (pintype "tri_state"))
      (node (ref "E98") (pin "5") (pinfunction "Q3_5") (pintype "tri_state"))
      (node (ref "R7") (pin "2") (pinfunction "2_2") (pintype "passive"))
    )
    (net (code "649") (name "~{RD7}") (class "Default")
      (node (ref "E105") (pin "11") (pinfunction "2Y1_11") (pintype "tri_state"))
      (node (ref "E106") (pin "5") (pinfunction "1Y2_5") (pintype "tri_state"))
      (node (ref "E112") (pin "11") (pinfunction "O1_11") (pintype "tri_state"))
      (node (ref "E16") (pin "16") (pinfunction "O2_16") (pintype "tri_state"))
      (node (ref "E7") (pin "9") (pinfunction "I_9") (pintype "input"))
      (node (ref "E83") (pin "5") (pinfunction "Y2_5") (pintype "tri_state"))
      (node (ref "E86") (pin "3") (pinfunction "1Y1_3") (pintype "tri_state"))
      (node (ref "E90") (pin "4") (pinfunction "Q2_4") (pintype "tri_state"))
      (node (ref "E98") (pin "4") (pinfunction "Q2_4") (pintype "tri_state"))
      (node (ref "R31") (pin "2") (pinfunction "2_2") (pintype "passive"))
    )
    (net (code "650") (name "~{RD8}") (class "Default")
      (node (ref "E105") (pin "9") (pinfunction "1Y4_9") (pintype "tri_state"))
      (node (ref "E106") (pin "7") (pinfunction "1Y3_7") (pintype "tri_state"))
      (node (ref "E112") (pin "12") (pinfunction "O0_12") (pintype "tri_state"))
      (node (ref "E16") (pin "17") (pinfunction "O1_17") (pintype "tri_state"))
      (node (ref "E44") (pin "1") (pinfunction "I_1") (pintype "input"))
      (node (ref "E83") (pin "3") (pinfunction "Y1_3") (pintype "tri_state"))
      (node (ref "E86") (pin "5") (pinfunction "1Y2_5") (pintype "tri_state"))
      (node (ref "E90") (pin "5") (pinfunction "Q3_5") (pintype "tri_state"))
      (node (ref "E98") (pin "3") (pinfunction "Q1_3") (pintype "tri_state"))
      (node (ref "R25") (pin "2") (pinfunction "2_2") (pintype "passive"))
    )
    (net (code "651") (name "~{RD9}") (class "Default")
      (node (ref "E101") (pin "3") (pinfunction "Y1_3") (pintype "tri_state"))
      (node (ref "E105") (pin "7") (pinfunction "1Y3_7") (pintype "tri_state"))
      (node (ref "E106") (pin "9") (pinfunction "1Y4_9") (pintype "tri_state"))
      (node (ref "E111") (pin "12") (pinfunction "O0_12") (pintype "tri_state"))
      (node (ref "E16") (pin "18") (pinfunction "O0_18") (pintype "tri_state"))
      (node (ref "E44") (pin "3") (pinfunction "I_3") (pintype "input"))
      (node (ref "E62") (pin "4") (pinfunction "Q2_4") (pintype "tri_state"))
      (node (ref "E86") (pin "7") (pinfunction "1Y3_7") (pintype "tri_state"))
      (node (ref "E90") (pin "6") (pinfunction "Q4_6") (pintype "tri_state"))
      (node (ref "R24") (pin "2") (pinfunction "2_2") (pintype "passive"))
    )
    (net (code "652") (name "~{RD10}") (class "Default")
      (node (ref "E100") (pin "11") (pinfunction "2Y1_11") (pintype "tri_state"))
      (node (ref "E101") (pin "5") (pinfunction "Y2_5") (pintype "tri_state"))
      (node (ref "E105") (pin "5") (pinfunction "1Y2_5") (pintype "tri_state"))
      (node (ref "E106") (pin "11") (pinfunction "2Y1_11") (pintype "tri_state"))
      (node (ref "E23") (pin "9") (pinfunction "3Y_9") (pintype "tri_state"))
      (node (ref "E44") (pin "5") (pinfunction "I_5") (pintype "input"))
      (node (ref "E62") (pin "5") (pinfunction "Q3_5") (pintype "tri_state"))
      (node (ref "E86") (pin "9") (pinfunction "1Y4_9") (pintype "tri_state"))
      (node (ref "R26") (pin "2") (pinfunction "2_2") (pintype "passive"))
    )
    (net (code "653") (name "~{RD11}") (class "Default")
      (node (ref "E100") (pin "13") (pinfunction "2Y2_13") (pintype "tri_state"))
      (node (ref "E101") (pin "7") (pinfunction "Y3_7") (pintype "tri_state"))
      (node (ref "E105") (pin "3") (pinfunction "1Y1_3") (pintype "tri_state"))
      (node (ref "E106") (pin "13") (pinfunction "2Y2_13") (pintype "tri_state"))
      (node (ref "E23") (pin "12") (pinfunction "4Y_12") (pintype "tri_state"))
      (node (ref "E44") (pin "9") (pinfunction "I_9") (pintype "input"))
      (node (ref "E62") (pin "6") (pinfunction "Q4_6") (pintype "tri_state"))
      (node (ref "E86") (pin "11") (pinfunction "2Y1_11") (pintype "tri_state"))
      (node (ref "R27") (pin "2") (pinfunction "2_2") (pintype "passive"))
    )
    (net (code "654") (name "~{RUN}") (class "Default")
      (node (ref "E66") (pin "4") (pinfunction "I0_4") (pintype "input"))
      (node (ref "U$1") (pin "BU2") (pinfunction "1_BU2") (pintype "bidirectional"))
    )
    (net (code "655") (name "~{SB0}") (class "Default")
      (node (ref "E100") (pin "2") (pinfunction "1A1_2") (pintype "input"))
      (node (ref "E109") (pin "23") (pinfunction "I12_23") (pintype "input"))
      (node (ref "E117") (pin "14") (pinfunction "~{Q4}_14") (pintype "output"))
    )
    (net (code "656") (name "~{SB1}") (class "Default")
      (node (ref "E100") (pin "4") (pinfunction "1A2_4") (pintype "input"))
      (node (ref "E109") (pin "24") (pinfunction "I11_24") (pintype "input"))
      (node (ref "E117") (pin "11") (pinfunction "~{Q3}_11") (pintype "output"))
    )
    (net (code "657") (name "~{SB2}") (class "Default")
      (node (ref "E100") (pin "6") (pinfunction "1A3_6") (pintype "input"))
      (node (ref "E109") (pin "25") (pinfunction "I10_25") (pintype "input"))
      (node (ref "E117") (pin "6") (pinfunction "~{Q2}_6") (pintype "output"))
    )
    (net (code "658") (name "~{SB3}") (class "Default")
      (node (ref "E100") (pin "10") (pinfunction "1A4_10") (pintype "input"))
      (node (ref "E109") (pin "26") (pinfunction "I9_26") (pintype "input"))
      (node (ref "E117") (pin "3") (pinfunction "~{Q1}_3") (pintype "output"))
    )
    (net (code "659") (name "~{SKIP}") (class "Default")
      (node (ref "E42") (pin "4") (pinfunction "O_4") (pintype "open_collector"))
      (node (ref "U$1") (pin "CS1") (pinfunction "1_CS1") (pintype "bidirectional"))
    )
    (net (code "660") (name "~{TS1}") (class "Default")
      (node (ref "E41") (pin "10") (pinfunction "I1_10") (pintype "input"))
      (node (ref "E41") (pin "11") (pinfunction "I0_11") (pintype "input"))
      (node (ref "U$1") (pin "CK2") (pinfunction "1_CK2") (pintype "bidirectional"))
    )
    (net (code "661") (name "~{TS3}") (class "Default")
      (node (ref "E51") (pin "12") (pinfunction "I1_12") (pintype "input"))
      (node (ref "U$1") (pin "CM2") (pinfunction "1_CM2") (pintype "bidirectional"))
    )
    (net (code "662") (name "~{TS4}") (class "Default")
      (node (ref "E51") (pin "4") (pinfunction "I0_4") (pintype "input"))
      (node (ref "U$1") (pin "CP2") (pinfunction "1_CP2") (pintype "bidirectional"))
    )
    (net (code "663") (name "~{USER_MODE}") (class "Default")
      (node (ref "E8") (pin "1") (pinfunction "O_1") (pintype "open_collector"))
      (node (ref "E8") (pin "4") (pinfunction "O_4") (pintype "open_collector"))
      (node (ref "U$1") (pin "DM2") (pinfunction "1_DM2") (pintype "bidirectional"))
    )
  )
)
